# SCH_Scope_1014D_2023-01-06.net
KiCad netlist of a schematic drawn in EasyEDA
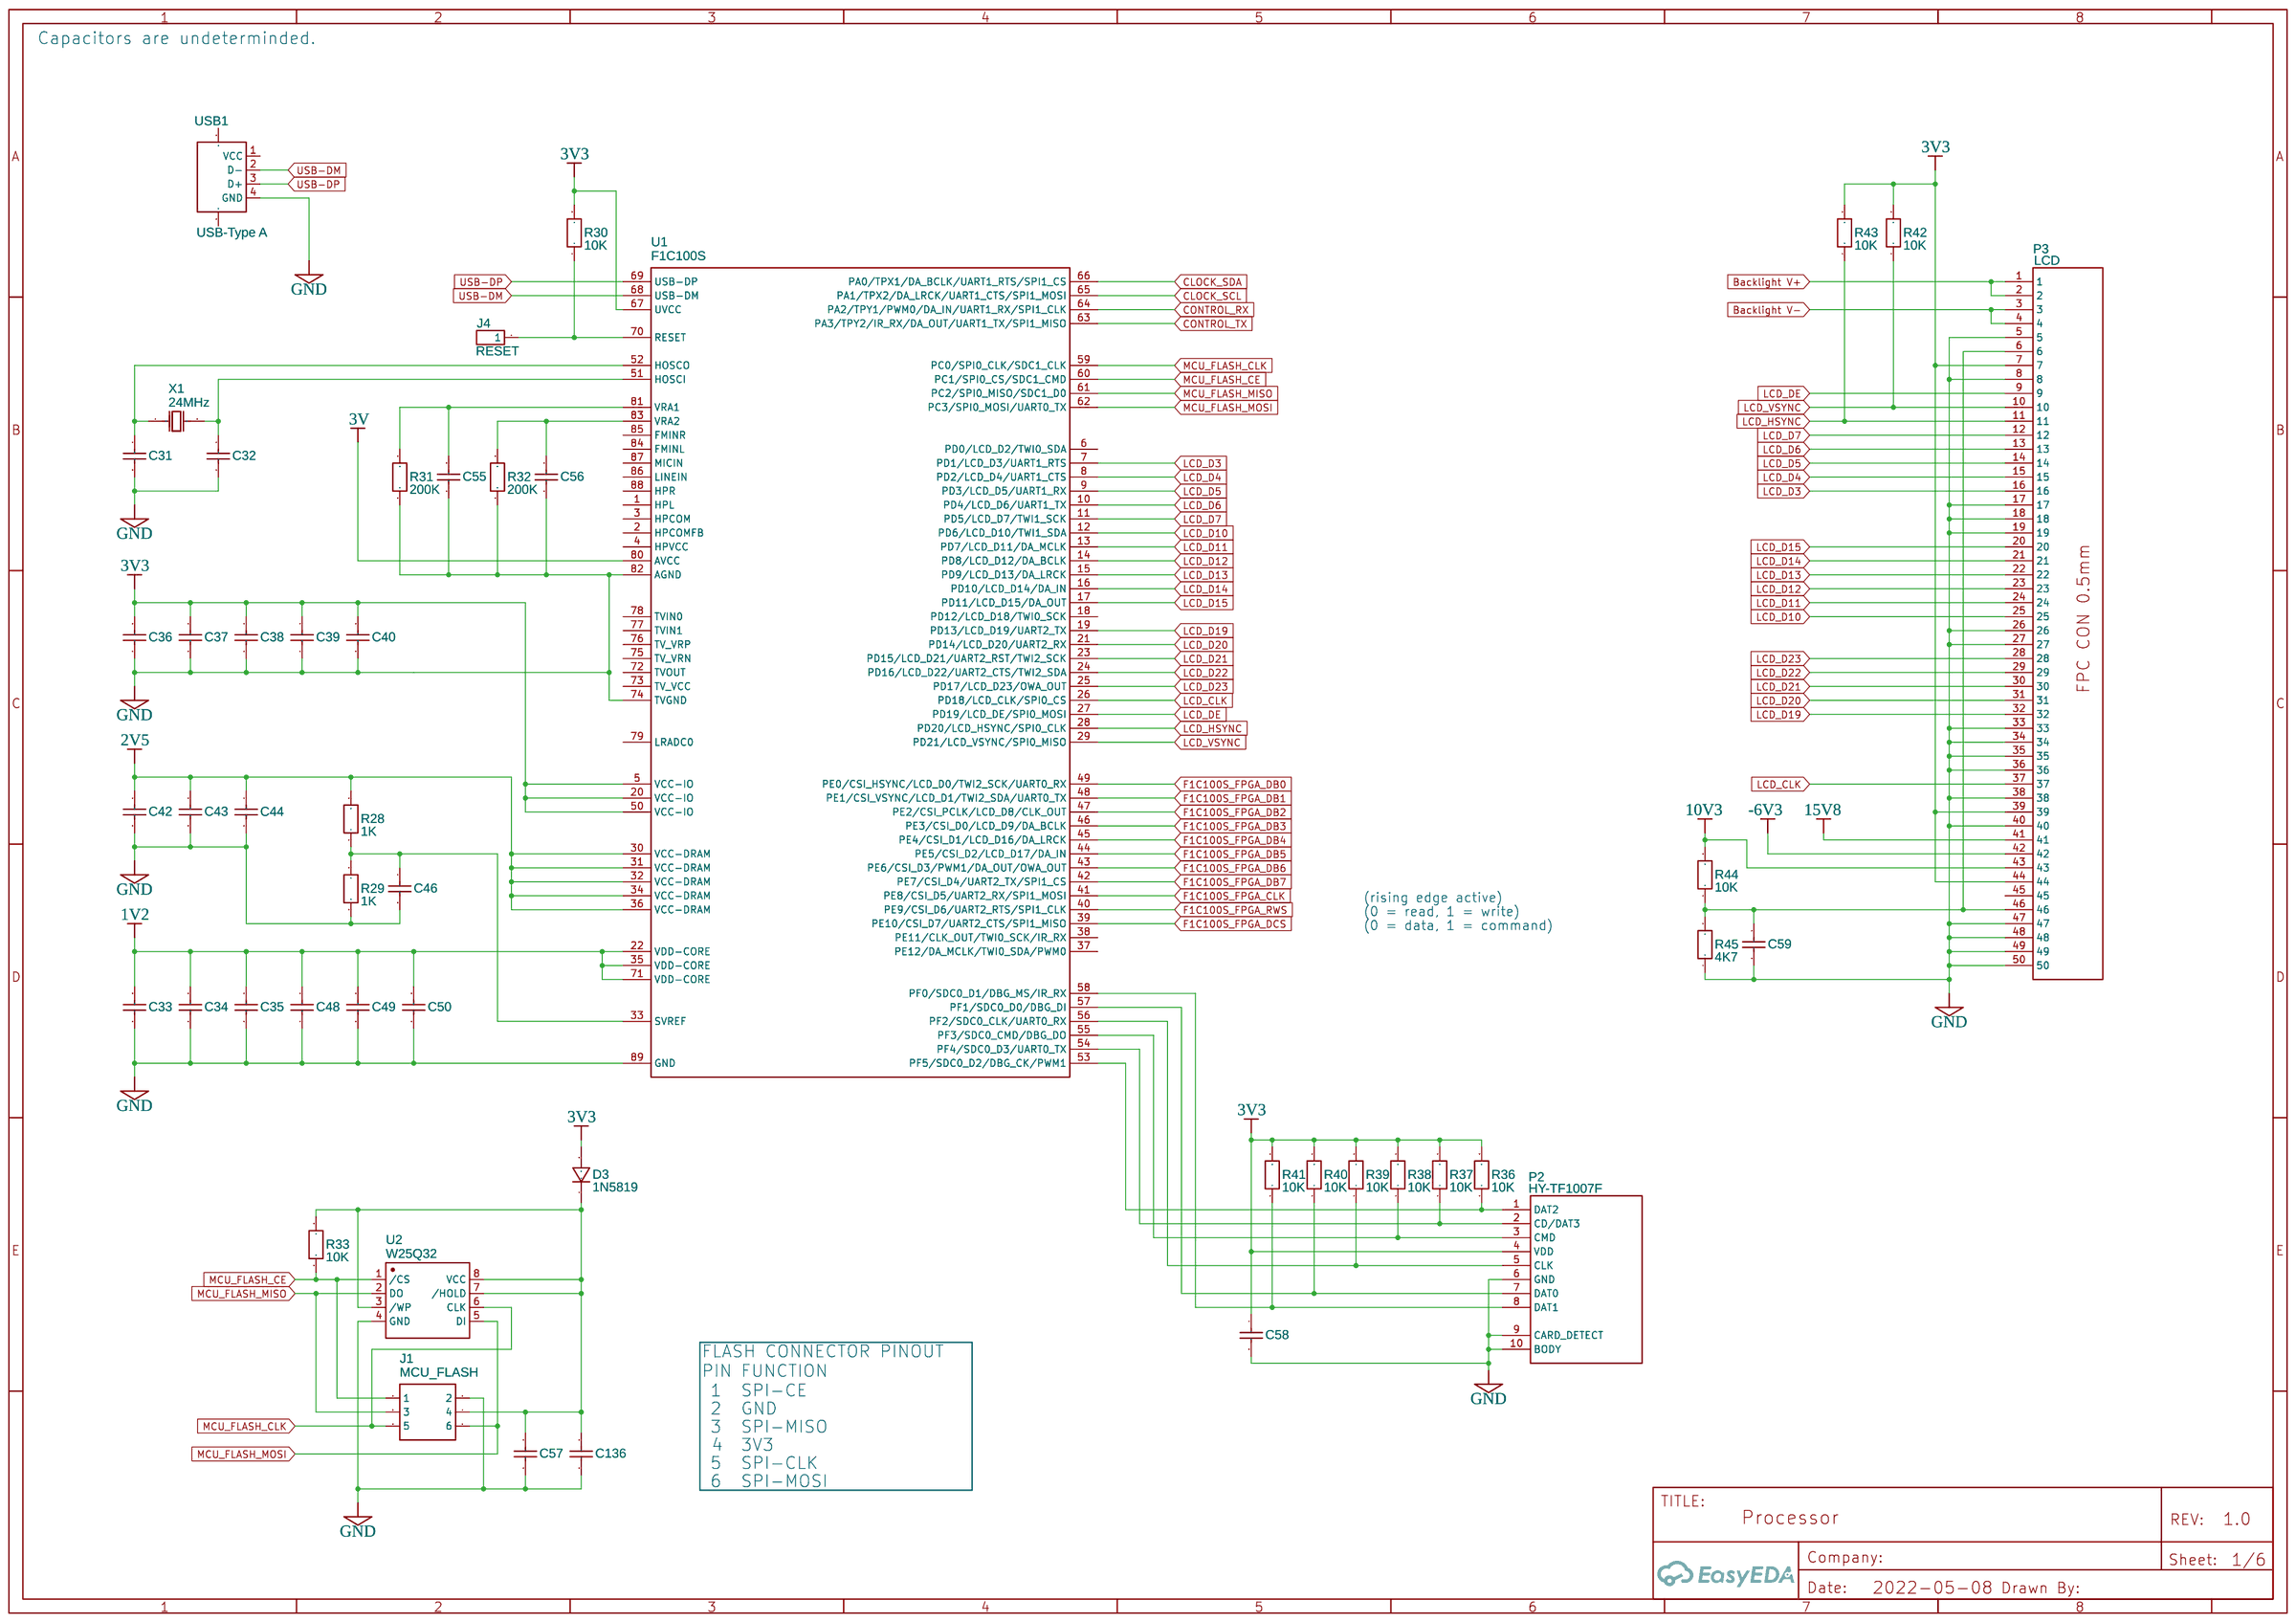
[diagram p0: Scope_1014D_Processor]
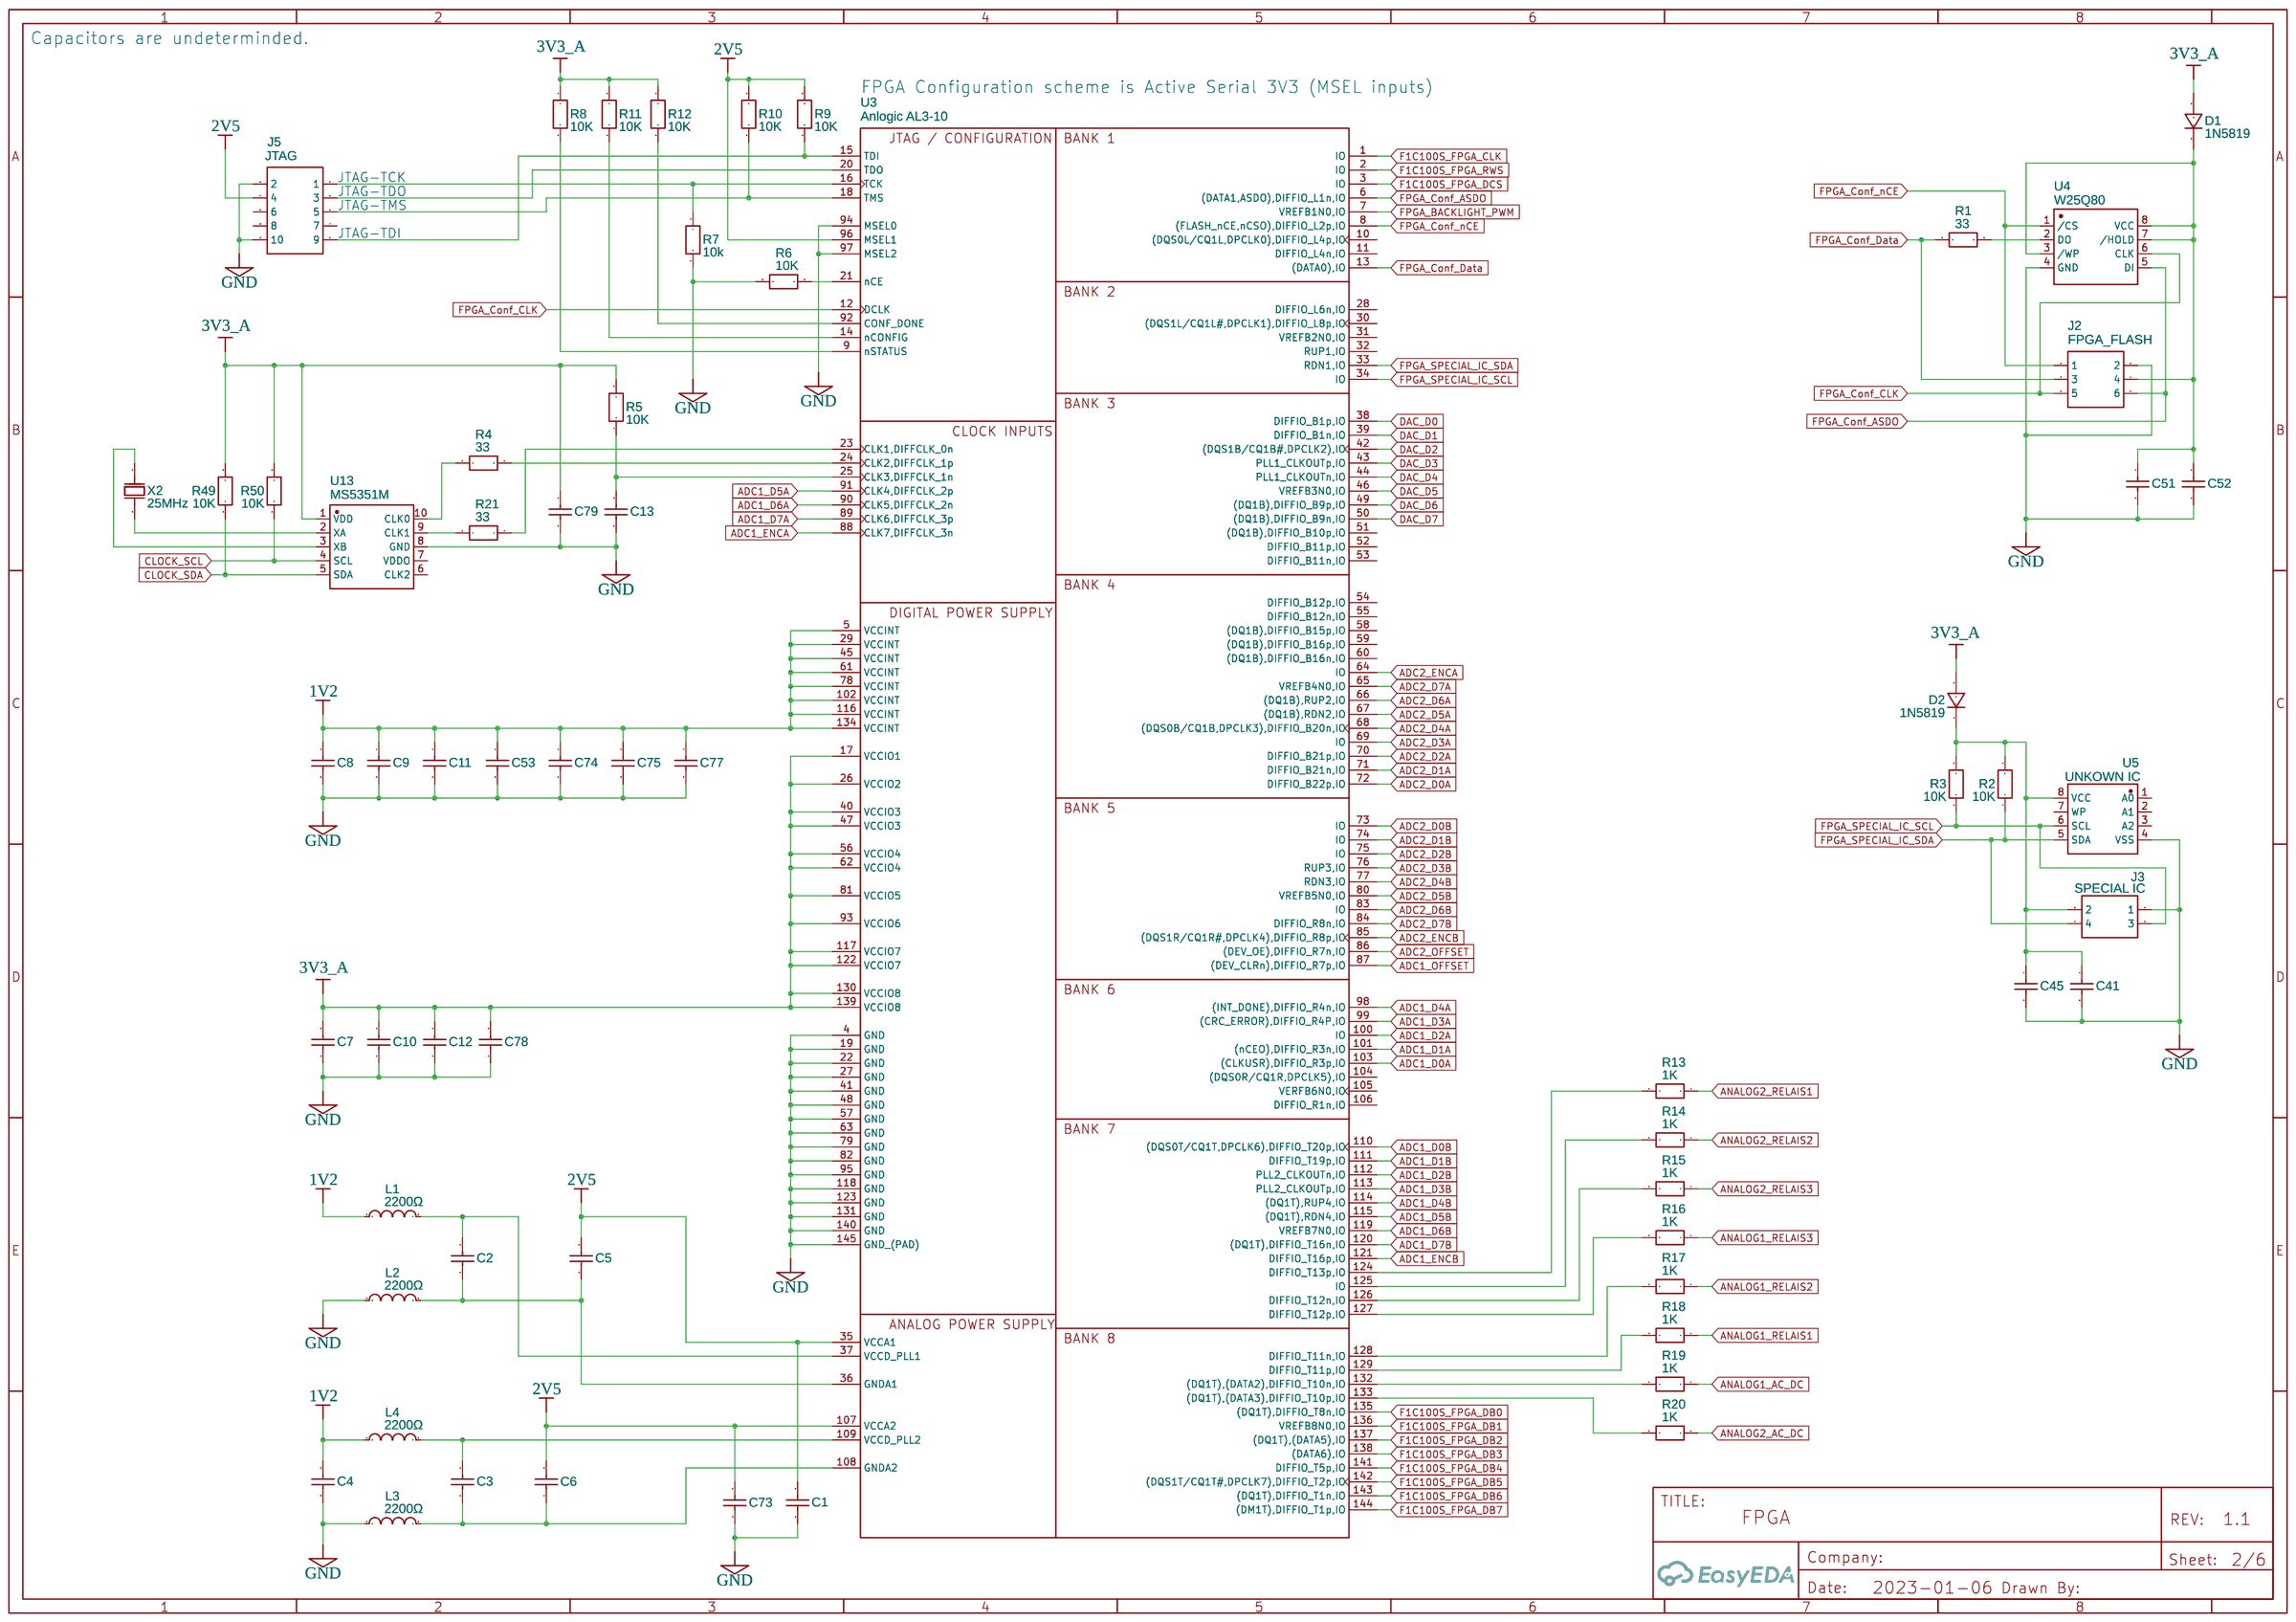
[diagram p1: Scope_1014D_Data_Acquisition]
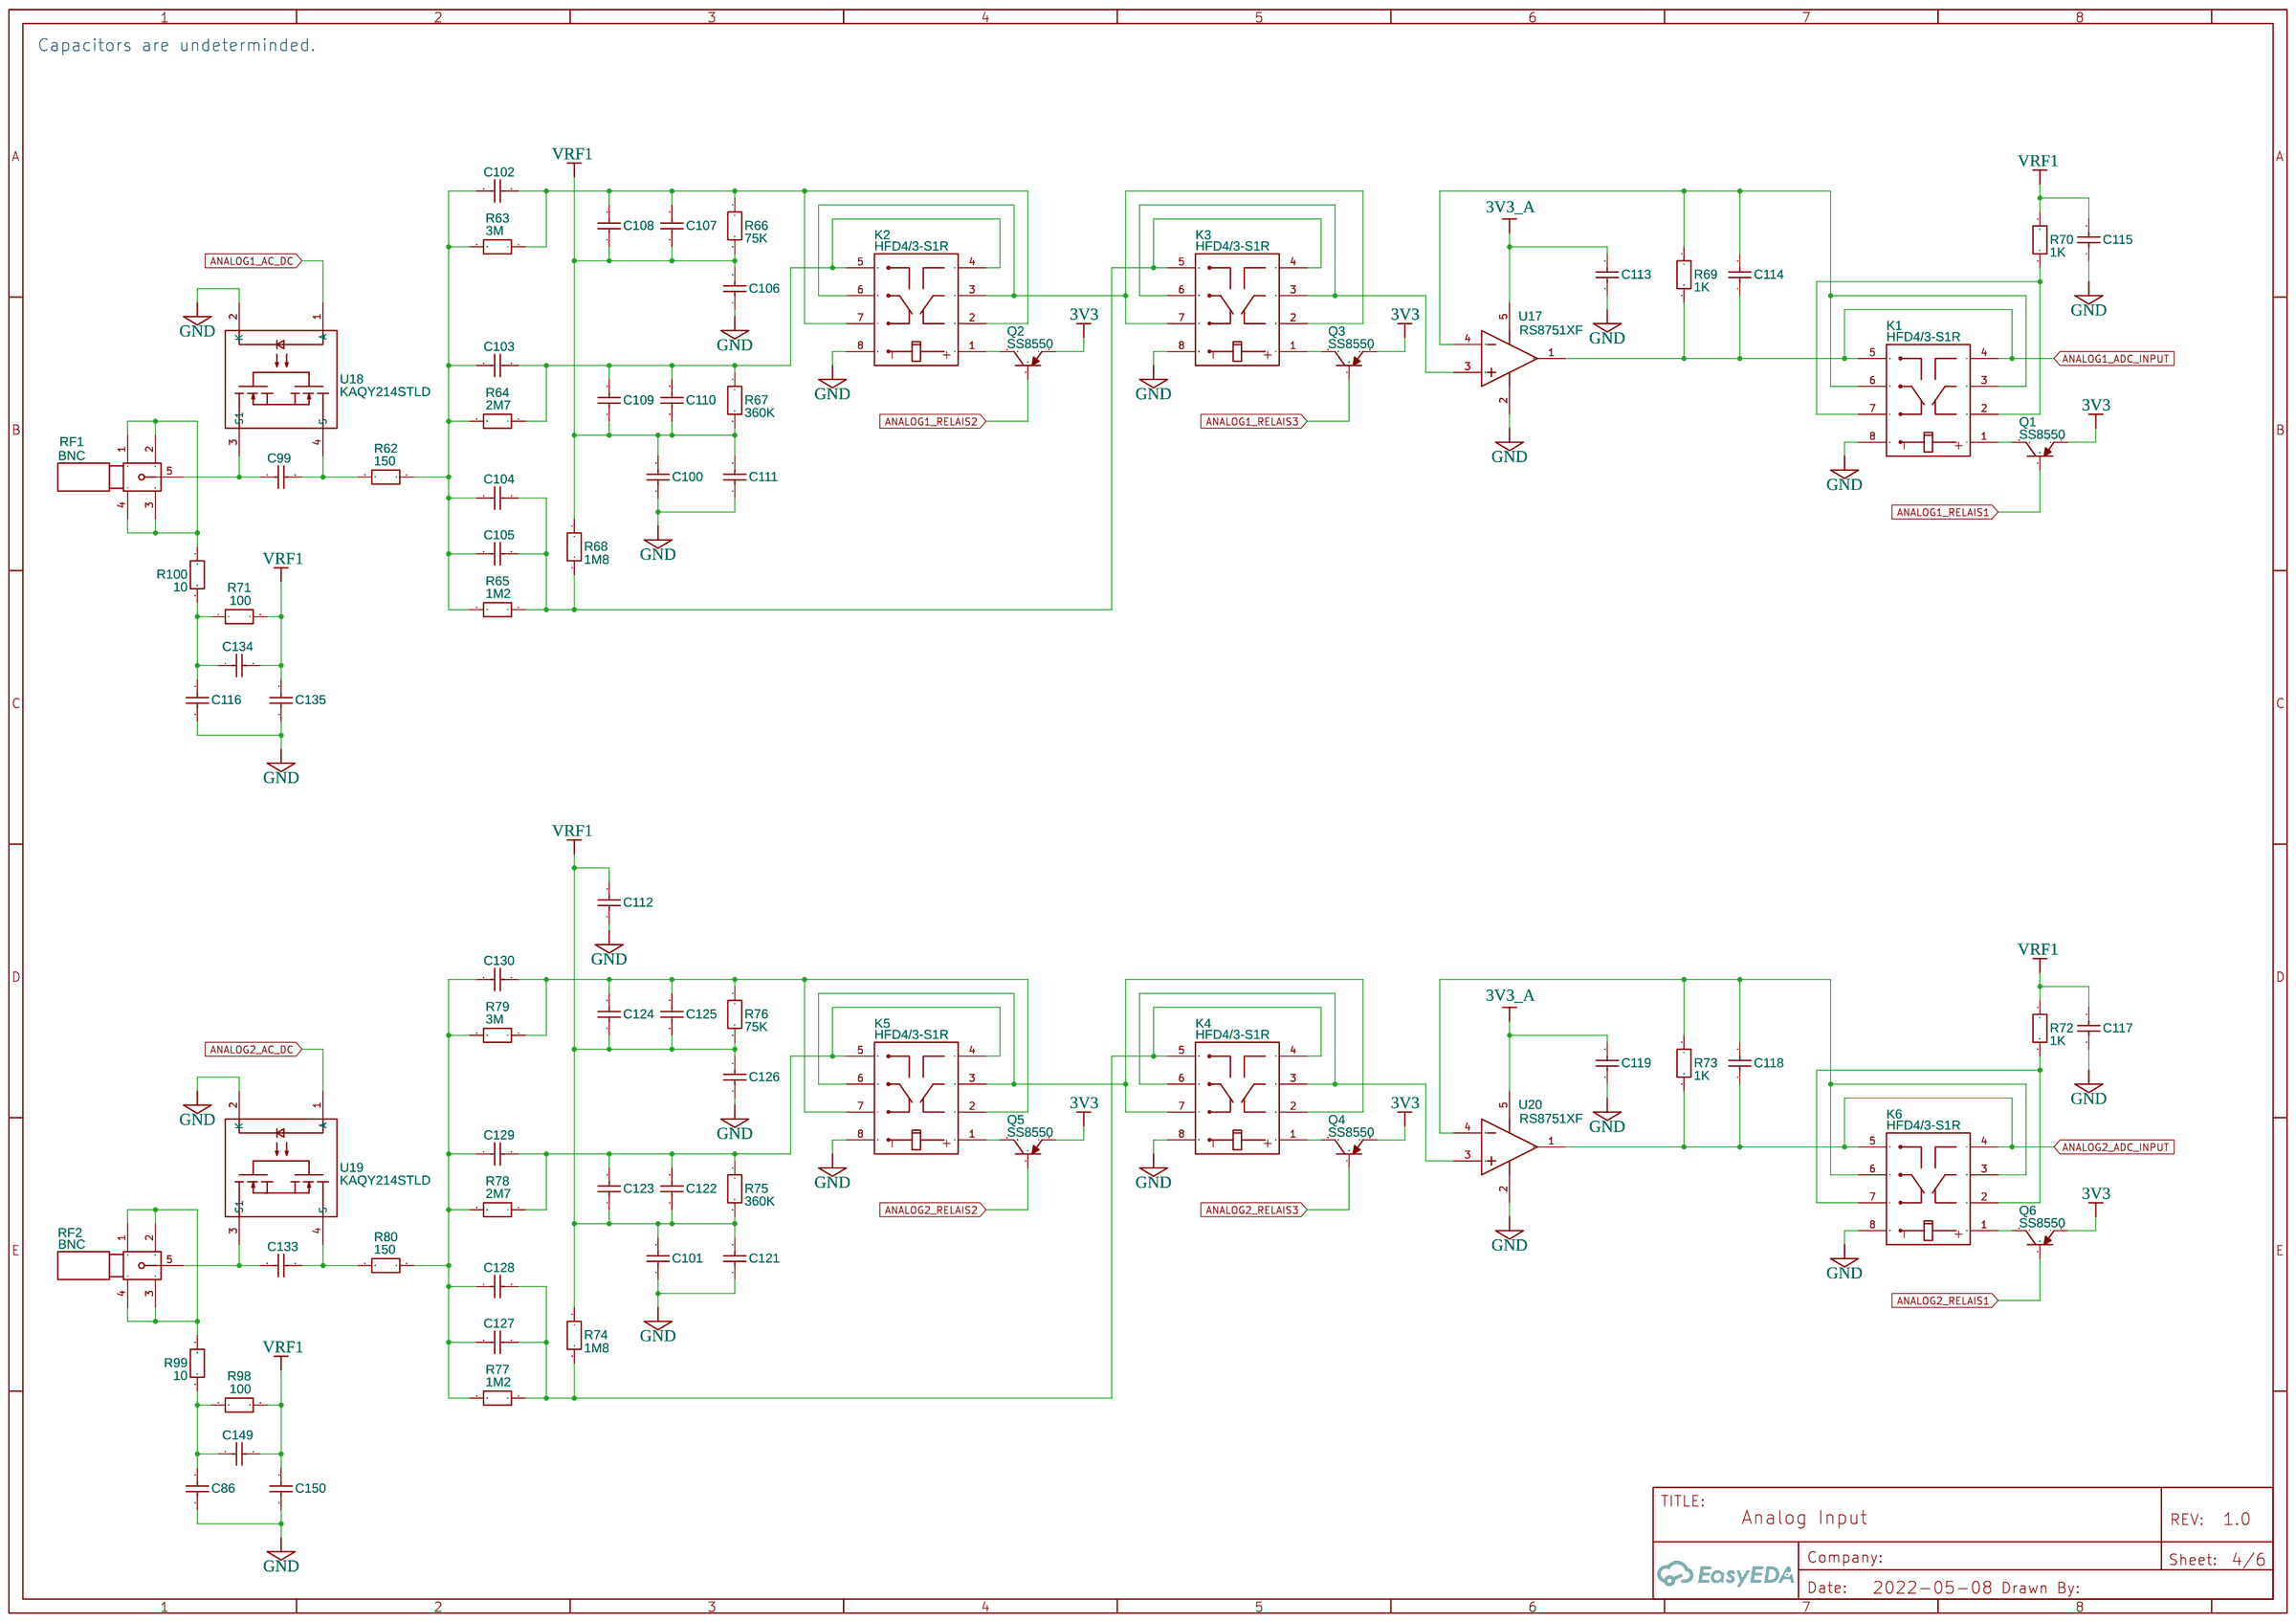
[diagram p2: Scope_1014D_Analog_Input]
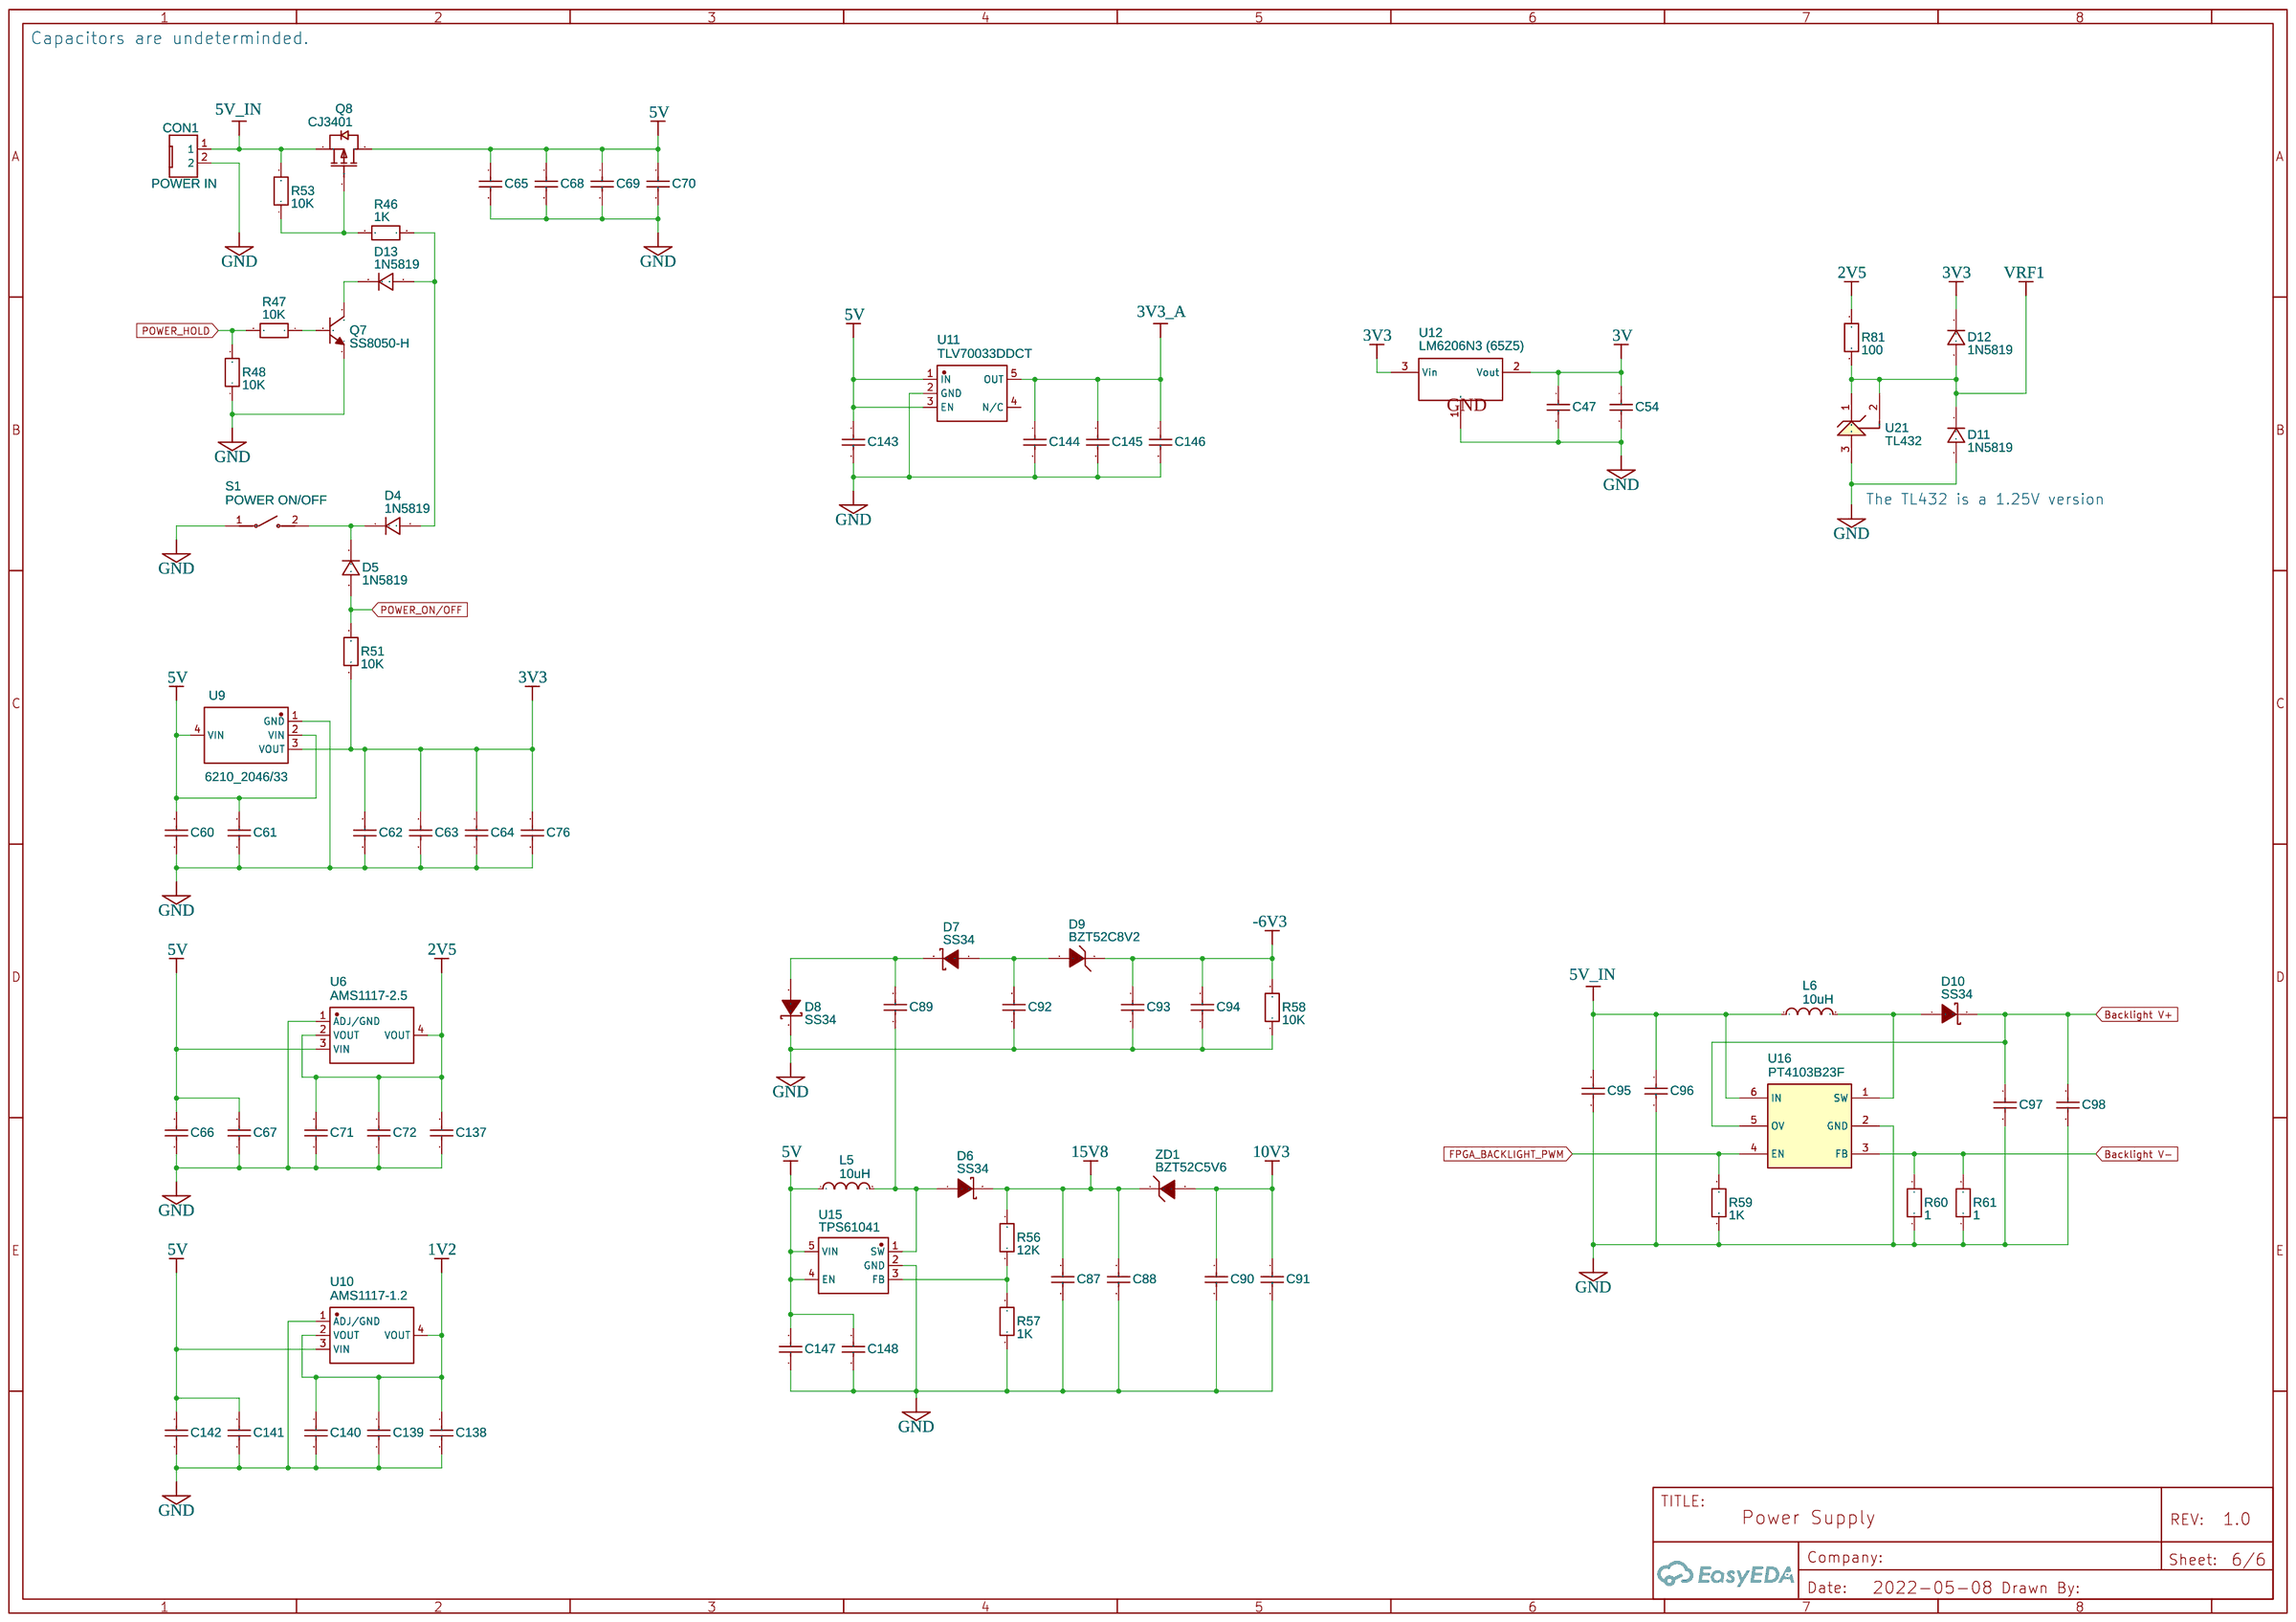
[diagram p3: Scope_1014D_Power_Supply]
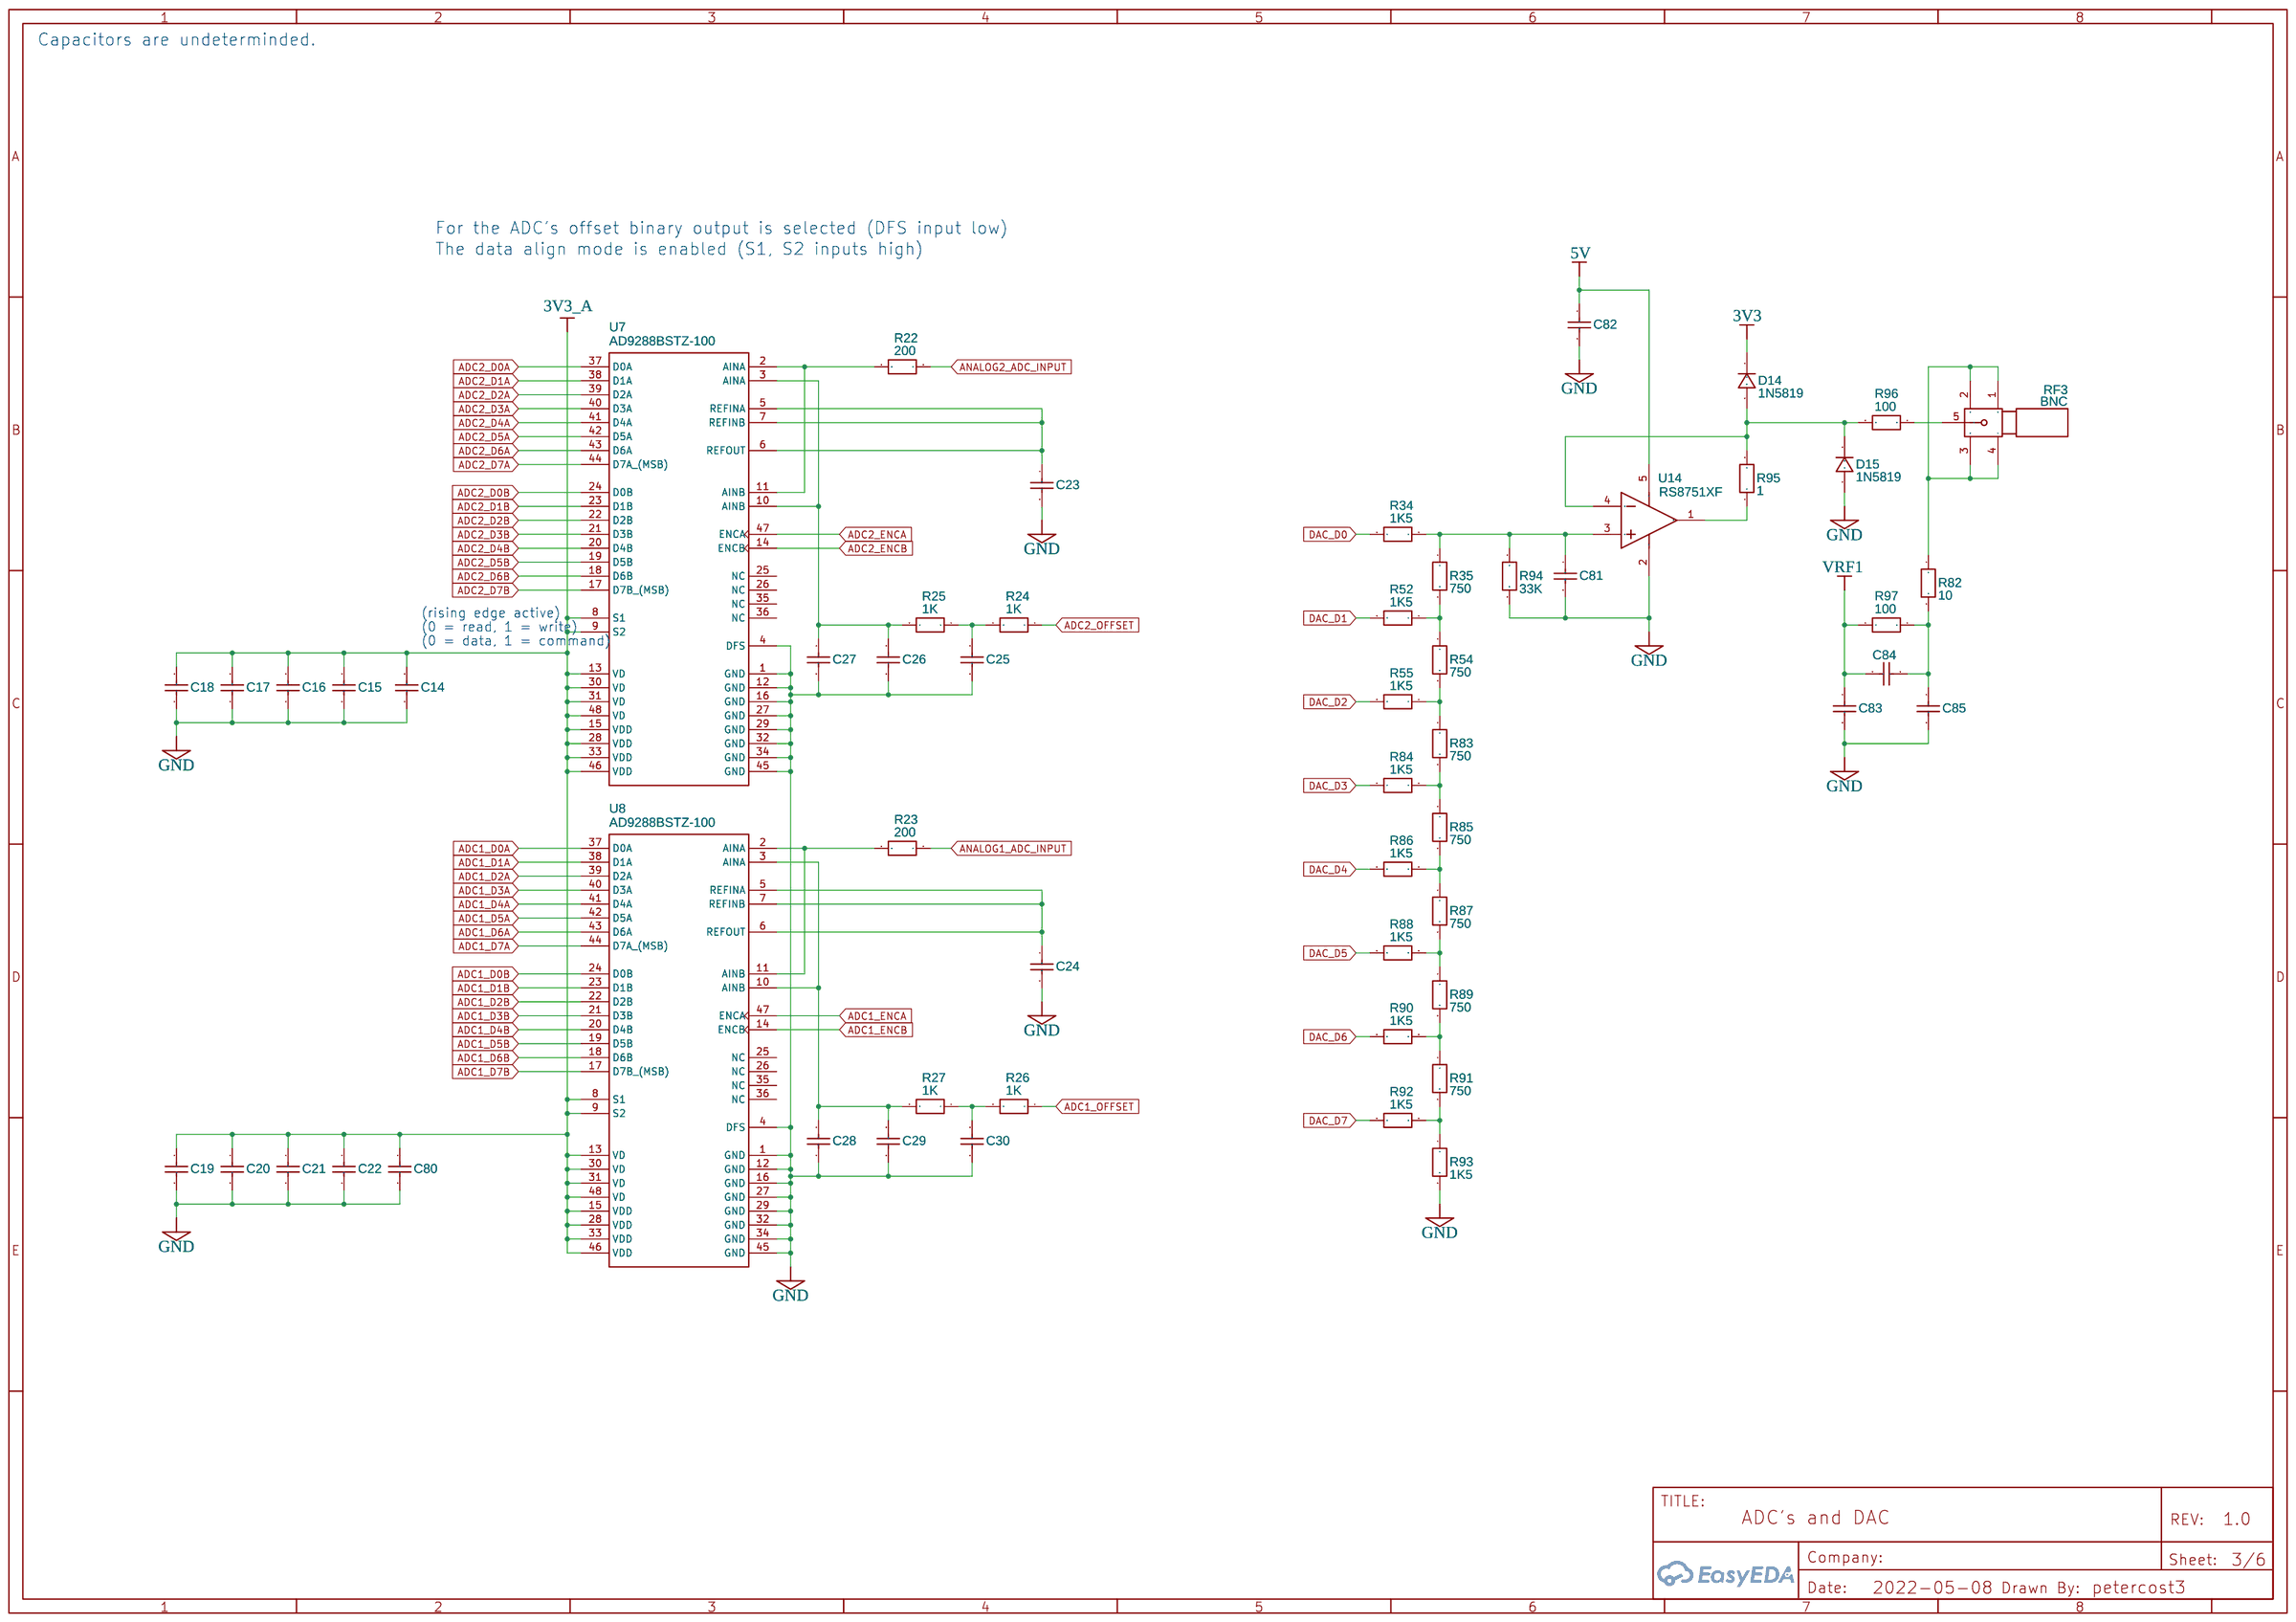
[diagram p4: Scope_1014D_ADC_DAC]
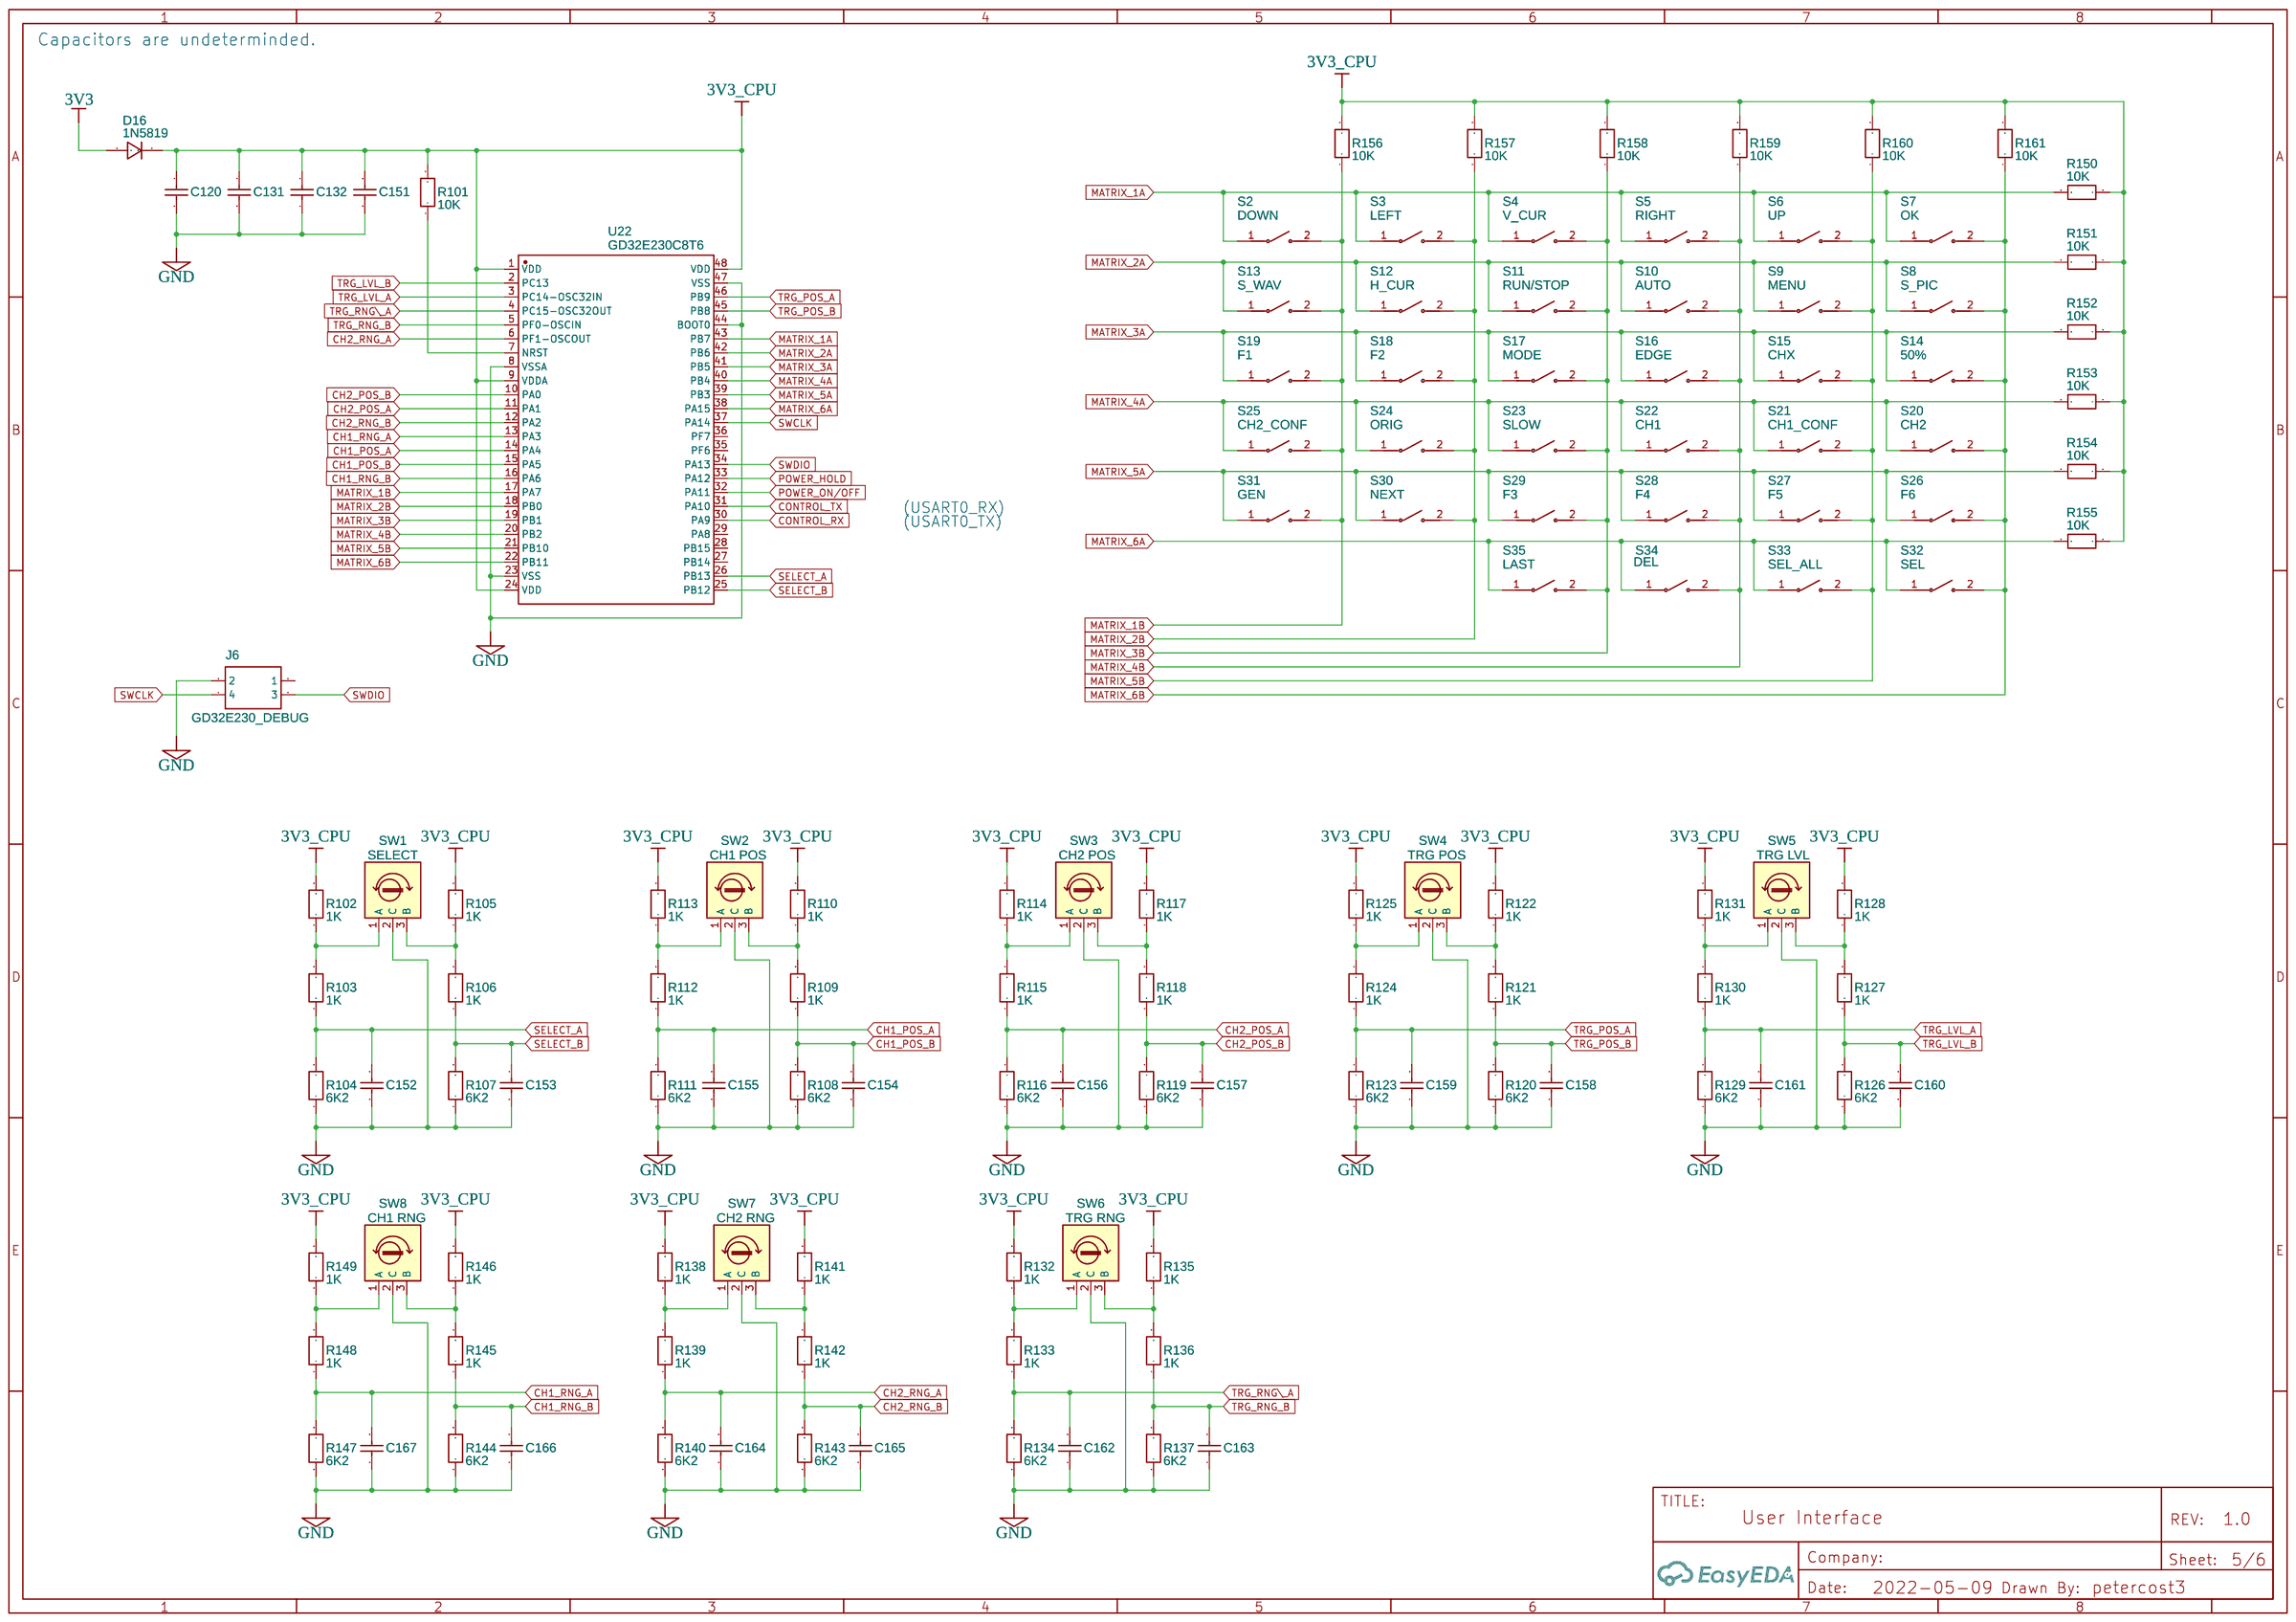
[diagram p5: Scope_1014D_User_Interface]

(export (version "E")
  (design (tool "Eeschema 10.0.6"))
  (components
    (comp (ref "C31")
      (value "1nF")
      (fields
        (field (name "BOM_Manufacturer Part") "GRM31B7U3A471JW31L")
        (field (name "BOM_Supplier Part") "C97936")
      )
      (libsource (lib "") (part "GRM31B7U3A471JW31L"))
    )
    (comp (ref "C32")
      (value "1nF")
      (fields
        (field (name "BOM_Manufacturer Part") "GRM31B7U3A471JW31L")
        (field (name "BOM_Supplier Part") "C97936")
      )
      (libsource (lib "") (part "GRM31B7U3A471JW31L"))
    )
    (comp (ref "C33")
      (value "1nF")
      (fields
        (field (name "BOM_Manufacturer Part") "GRM31B7U3A471JW31L")
        (field (name "BOM_Supplier Part") "C97936")
      )
      (libsource (lib "") (part "GRM31B7U3A471JW31L"))
    )
    (comp (ref "C34")
      (value "1nF")
      (fields
        (field (name "BOM_Manufacturer Part") "GRM31B7U3A471JW31L")
        (field (name "BOM_Supplier Part") "C97936")
      )
      (libsource (lib "") (part "GRM31B7U3A471JW31L"))
    )
    (comp (ref "C35")
      (value "1nF")
      (fields
        (field (name "BOM_Manufacturer Part") "GRM31B7U3A471JW31L")
        (field (name "BOM_Supplier Part") "C97936")
      )
      (libsource (lib "") (part "GRM31B7U3A471JW31L"))
    )
    (comp (ref "C36")
      (value "1nF")
      (fields
        (field (name "BOM_Manufacturer Part") "GRM31B7U3A471JW31L")
        (field (name "BOM_Supplier Part") "C97936")
      )
      (libsource (lib "") (part "GRM31B7U3A471JW31L"))
    )
    (comp (ref "C37")
      (value "1nF")
      (fields
        (field (name "BOM_Manufacturer Part") "GRM31B7U3A471JW31L")
        (field (name "BOM_Supplier Part") "C97936")
      )
      (libsource (lib "") (part "GRM31B7U3A471JW31L"))
    )
    (comp (ref "C38")
      (value "1nF")
      (fields
        (field (name "BOM_Manufacturer Part") "GRM31B7U3A471JW31L")
        (field (name "BOM_Supplier Part") "C97936")
      )
      (libsource (lib "") (part "GRM31B7U3A471JW31L"))
    )
    (comp (ref "C39")
      (value "1nF")
      (fields
        (field (name "BOM_Manufacturer Part") "GRM31B7U3A471JW31L")
        (field (name "BOM_Supplier Part") "C97936")
      )
      (libsource (lib "") (part "GRM31B7U3A471JW31L"))
    )
    (comp (ref "C40")
      (value "1nF")
      (fields
        (field (name "BOM_Manufacturer Part") "GRM31B7U3A471JW31L")
        (field (name "BOM_Supplier Part") "C97936")
      )
      (libsource (lib "") (part "GRM31B7U3A471JW31L"))
    )
    (comp (ref "C42")
      (value "1nF")
      (fields
        (field (name "BOM_Manufacturer Part") "GRM31B7U3A471JW31L")
        (field (name "BOM_Supplier Part") "C97936")
      )
      (libsource (lib "") (part "GRM31B7U3A471JW31L"))
    )
    (comp (ref "C43")
      (value "1nF")
      (fields
        (field (name "BOM_Manufacturer Part") "GRM31B7U3A471JW31L")
        (field (name "BOM_Supplier Part") "C97936")
      )
      (libsource (lib "") (part "GRM31B7U3A471JW31L"))
    )
    (comp (ref "C44")
      (value "1nF")
      (fields
        (field (name "BOM_Manufacturer Part") "GRM31B7U3A471JW31L")
        (field (name "BOM_Supplier Part") "C97936")
      )
      (libsource (lib "") (part "GRM31B7U3A471JW31L"))
    )
    (comp (ref "C46")
      (value "1nF")
      (fields
        (field (name "BOM_Manufacturer Part") "GRM31B7U3A471JW31L")
        (field (name "BOM_Supplier Part") "C97936")
      )
      (libsource (lib "") (part "GRM31B7U3A471JW31L"))
    )
    (comp (ref "C48")
      (value "1nF")
      (fields
        (field (name "BOM_Manufacturer Part") "GRM31B7U3A471JW31L")
        (field (name "BOM_Supplier Part") "C97936")
      )
      (libsource (lib "") (part "GRM31B7U3A471JW31L"))
    )
    (comp (ref "C49")
      (value "1nF")
      (fields
        (field (name "BOM_Manufacturer Part") "GRM31B7U3A471JW31L")
        (field (name "BOM_Supplier Part") "C97936")
      )
      (libsource (lib "") (part "GRM31B7U3A471JW31L"))
    )
    (comp (ref "C50")
      (value "1nF")
      (fields
        (field (name "BOM_Manufacturer Part") "GRM31B7U3A471JW31L")
        (field (name "BOM_Supplier Part") "C97936")
      )
      (libsource (lib "") (part "GRM31B7U3A471JW31L"))
    )
    (comp (ref "C55")
      (value "1nF")
      (fields
        (field (name "BOM_Manufacturer Part") "GRM31B7U3A471JW31L")
        (field (name "BOM_Supplier Part") "C97936")
      )
      (libsource (lib "") (part "GRM31B7U3A471JW31L"))
    )
    (comp (ref "C56")
      (value "1nF")
      (fields
        (field (name "BOM_Manufacturer Part") "GRM31B7U3A471JW31L")
        (field (name "BOM_Supplier Part") "C97936")
      )
      (libsource (lib "") (part "GRM31B7U3A471JW31L"))
    )
    (comp (ref "C57")
      (value "1nF")
      (fields
        (field (name "BOM_Manufacturer Part") "GRM31B7U3A471JW31L")
        (field (name "BOM_Supplier Part") "C97936")
      )
      (libsource (lib "") (part "GRM31B7U3A471JW31L"))
    )
    (comp (ref "C58")
      (value "1nF")
      (fields
        (field (name "BOM_Manufacturer Part") "GRM31B7U3A471JW31L")
        (field (name "BOM_Supplier Part") "C97936")
      )
      (libsource (lib "") (part "GRM31B7U3A471JW31L"))
    )
    (comp (ref "C59")
      (value "1nF")
      (fields
        (field (name "BOM_Manufacturer Part") "GRM31B7U3A471JW31L")
        (field (name "BOM_Supplier Part") "C97936")
      )
      (libsource (lib "") (part "GRM31B7U3A471JW31L"))
    )
    (comp (ref "C136")
      (value "1nF")
      (fields
        (field (name "BOM_Manufacturer Part") "GRM31B7U3A471JW31L")
        (field (name "BOM_Supplier Part") "C97936")
      )
      (libsource (lib "") (part "GRM31B7U3A471JW31L"))
    )
    (comp (ref "D3")
      (value "1N5819")
      (fields (field (name "BOM_Manufacturer Part") "1N4007") (field (name "BOM_Supplier Part") "C106903"))
      (libsource (lib "") (part "1N4007"))
    )
    (comp (ref "J1")
      (value "MCU_FLASH")
      (fields (field (name "BOM_Supplier Part") "C65114"))
      (libsource (lib "") (part "HDR-M-2.54_2x3"))
    )
    (comp (ref "J4")
      (value "RESET")
      (fields (field (name "BOM_Supplier Part") "C81276"))
      (libsource (lib "") (part "HDR-M-2.54_1x1"))
    )
    (comp (ref "P2")
      (value "HY-TF1007F")
      (fields (field (name "BOM_Supplier Part") "undefined"))
      (libsource (lib "") (part "HY-TF1007F"))
    )
    (comp (ref "P3") (value "LCD") (libsource (lib "") (part "FPC CONNECTOR 50P 0.5mm")))
    (comp (ref "R28") (value "1K") (libsource (lib "") (part "R_0805_EU")))
    (comp (ref "R29") (value "1K") (libsource (lib "") (part "R_0805_EU")))
    (comp (ref "R30") (value "10K") (libsource (lib "") (part "R_0805_EU")))
    (comp (ref "R31") (value "200K") (libsource (lib "") (part "R_0805_EU")))
    (comp (ref "R32") (value "200K") (libsource (lib "") (part "R_0805_EU")))
    (comp (ref "R33") (value "10K") (libsource (lib "") (part "R_0805_EU")))
    (comp (ref "R36") (value "10K") (libsource (lib "") (part "R_0805_EU")))
    (comp (ref "R37") (value "10K") (libsource (lib "") (part "R_0805_EU")))
    (comp (ref "R38") (value "10K") (libsource (lib "") (part "R_0805_EU")))
    (comp (ref "R39") (value "10K") (libsource (lib "") (part "R_0805_EU")))
    (comp (ref "R40") (value "10K") (libsource (lib "") (part "R_0805_EU")))
    (comp (ref "R41") (value "10K") (libsource (lib "") (part "R_0805_EU")))
    (comp (ref "R42") (value "10K") (libsource (lib "") (part "R_0805_EU")))
    (comp (ref "R43") (value "10K") (libsource (lib "") (part "R_0805_EU")))
    (comp (ref "R44") (value "10K") (libsource (lib "") (part "R_0805_EU")))
    (comp (ref "R45") (value "4K7") (libsource (lib "") (part "R_0805_EU")))
    (comp (ref "U1") (value "F1C100S") (libsource (lib "") (part "F1C100S")))
    (comp (ref "U2")
      (value "W25Q32")
      (fields
        (field (name "BOM_Manufacturer Part") "W25Q32FVSSIGTR")
        (field (name "BOM_Supplier Part") "C108057")
      )
      (libsource (lib "") (part "W25Q32FVSSIGTR"))
    )
    (comp (ref "USB1")
      (value "USB-Type A")
      (fields (field (name "BOM_Manufacturer Part") "USB-05") (field (name "BOM_Supplier Part") "C112454"))
      (libsource (lib "") (part "USB-Type A_Male"))
    )
    (comp (ref "X1")
      (value "24MHz")
      (fields
        (field (name "BOM_Manufacturer Part") "X503224MSD2GC")
        (field (name "BOM_Supplier Part") "C48304")
      )
      (libsource (lib "") (part "X503224MSD2GC"))
    )
    (comp (ref "C1")
      (value "1nF")
      (fields
        (field (name "BOM_Manufacturer Part") "GRM31B7U3A471JW31L")
        (field (name "BOM_Supplier Part") "C97936")
      )
      (libsource (lib "") (part "GRM31B7U3A471JW31L_1"))
    )
    (comp (ref "C2")
      (value "1nF")
      (fields
        (field (name "BOM_Manufacturer Part") "GRM31B7U3A471JW31L")
        (field (name "BOM_Supplier Part") "C97936")
      )
      (libsource (lib "") (part "GRM31B7U3A471JW31L_1"))
    )
    (comp (ref "C3")
      (value "1nF")
      (fields
        (field (name "BOM_Manufacturer Part") "GRM31B7U3A471JW31L")
        (field (name "BOM_Supplier Part") "C97936")
      )
      (libsource (lib "") (part "GRM31B7U3A471JW31L_1"))
    )
    (comp (ref "C4")
      (value "1nF")
      (fields
        (field (name "BOM_Manufacturer Part") "GRM31B7U3A471JW31L")
        (field (name "BOM_Supplier Part") "C97936")
      )
      (libsource (lib "") (part "GRM31B7U3A471JW31L_1"))
    )
    (comp (ref "C5")
      (value "1nF")
      (fields
        (field (name "BOM_Manufacturer Part") "GRM31B7U3A471JW31L")
        (field (name "BOM_Supplier Part") "C97936")
      )
      (libsource (lib "") (part "GRM31B7U3A471JW31L_1"))
    )
    (comp (ref "C6")
      (value "1nF")
      (fields
        (field (name "BOM_Manufacturer Part") "GRM31B7U3A471JW31L")
        (field (name "BOM_Supplier Part") "C97936")
      )
      (libsource (lib "") (part "GRM31B7U3A471JW31L"))
    )
    (comp (ref "C7")
      (value "1nF")
      (fields
        (field (name "BOM_Manufacturer Part") "GRM31B7U3A471JW31L")
        (field (name "BOM_Supplier Part") "C97936")
      )
      (libsource (lib "") (part "GRM31B7U3A471JW31L_1"))
    )
    (comp (ref "C8")
      (value "1nF")
      (fields
        (field (name "BOM_Manufacturer Part") "GRM31B7U3A471JW31L")
        (field (name "BOM_Supplier Part") "C97936")
      )
      (libsource (lib "") (part "GRM31B7U3A471JW31L_1"))
    )
    (comp (ref "C9")
      (value "1nF")
      (fields
        (field (name "BOM_Manufacturer Part") "GRM31B7U3A471JW31L")
        (field (name "BOM_Supplier Part") "C97936")
      )
      (libsource (lib "") (part "GRM31B7U3A471JW31L_1"))
    )
    (comp (ref "C10")
      (value "1nF")
      (fields
        (field (name "BOM_Manufacturer Part") "GRM31B7U3A471JW31L")
        (field (name "BOM_Supplier Part") "C97936")
      )
      (libsource (lib "") (part "GRM31B7U3A471JW31L_1"))
    )
    (comp (ref "C11")
      (value "1nF")
      (fields
        (field (name "BOM_Manufacturer Part") "GRM31B7U3A471JW31L")
        (field (name "BOM_Supplier Part") "C97936")
      )
      (libsource (lib "") (part "GRM31B7U3A471JW31L_1"))
    )
    (comp (ref "C12")
      (value "1nF")
      (fields
        (field (name "BOM_Manufacturer Part") "GRM31B7U3A471JW31L")
        (field (name "BOM_Supplier Part") "C97936")
      )
      (libsource (lib "") (part "GRM31B7U3A471JW31L_1"))
    )
    (comp (ref "C13")
      (value "1nF")
      (fields
        (field (name "BOM_Manufacturer Part") "GRM31B7U3A471JW31L")
        (field (name "BOM_Supplier Part") "C97936")
      )
      (libsource (lib "") (part "GRM31B7U3A471JW31L_1"))
    )
    (comp (ref "C41")
      (value "1nF")
      (fields
        (field (name "BOM_Manufacturer Part") "GRM31B7U3A471JW31L")
        (field (name "BOM_Supplier Part") "C97936")
      )
      (libsource (lib "") (part "GRM31B7U3A471JW31L_1"))
    )
    (comp (ref "C45")
      (value "1nF")
      (fields
        (field (name "BOM_Manufacturer Part") "GRM31B7U3A471JW31L")
        (field (name "BOM_Supplier Part") "C97936")
      )
      (libsource (lib "") (part "GRM31B7U3A471JW31L_1"))
    )
    (comp (ref "C51")
      (value "1nF")
      (fields
        (field (name "BOM_Manufacturer Part") "GRM31B7U3A471JW31L")
        (field (name "BOM_Supplier Part") "C97936")
      )
      (libsource (lib "") (part "GRM31B7U3A471JW31L_1"))
    )
    (comp (ref "C52")
      (value "1nF")
      (fields
        (field (name "BOM_Manufacturer Part") "GRM31B7U3A471JW31L")
        (field (name "BOM_Supplier Part") "C97936")
      )
      (libsource (lib "") (part "GRM31B7U3A471JW31L_1"))
    )
    (comp (ref "C53")
      (value "1nF")
      (fields
        (field (name "BOM_Manufacturer Part") "GRM31B7U3A471JW31L")
        (field (name "BOM_Supplier Part") "C97936")
      )
      (libsource (lib "") (part "GRM31B7U3A471JW31L_1"))
    )
    (comp (ref "C73")
      (value "1nF")
      (fields
        (field (name "BOM_Manufacturer Part") "GRM31B7U3A471JW31L")
        (field (name "BOM_Supplier Part") "C97936")
      )
      (libsource (lib "") (part "GRM31B7U3A471JW31L"))
    )
    (comp (ref "C74")
      (value "1nF")
      (fields
        (field (name "BOM_Manufacturer Part") "GRM31B7U3A471JW31L")
        (field (name "BOM_Supplier Part") "C97936")
      )
      (libsource (lib "") (part "GRM31B7U3A471JW31L_1"))
    )
    (comp (ref "C75")
      (value "1nF")
      (fields
        (field (name "BOM_Manufacturer Part") "GRM31B7U3A471JW31L")
        (field (name "BOM_Supplier Part") "C97936")
      )
      (libsource (lib "") (part "GRM31B7U3A471JW31L_1"))
    )
    (comp (ref "C77")
      (value "1nF")
      (fields
        (field (name "BOM_Manufacturer Part") "GRM31B7U3A471JW31L")
        (field (name "BOM_Supplier Part") "C97936")
      )
      (libsource (lib "") (part "GRM31B7U3A471JW31L_1"))
    )
    (comp (ref "C78")
      (value "1nF")
      (fields
        (field (name "BOM_Manufacturer Part") "GRM31B7U3A471JW31L")
        (field (name "BOM_Supplier Part") "C97936")
      )
      (libsource (lib "") (part "GRM31B7U3A471JW31L_1"))
    )
    (comp (ref "C79")
      (value "1nF")
      (fields
        (field (name "BOM_Manufacturer Part") "GRM31B7U3A471JW31L")
        (field (name "BOM_Supplier Part") "C97936")
      )
      (libsource (lib "") (part "GRM31B7U3A471JW31L_1"))
    )
    (comp (ref "D1")
      (value "1N5819")
      (fields (field (name "BOM_Manufacturer Part") "1N4007") (field (name "BOM_Supplier Part") "C106903"))
      (libsource (lib "") (part "1N4007_1"))
    )
    (comp (ref "D2")
      (value "1N5819")
      (fields (field (name "BOM_Manufacturer Part") "1N4007") (field (name "BOM_Supplier Part") "C106903"))
      (libsource (lib "") (part "1N4007"))
    )
    (comp (ref "J2")
      (value "FPGA_FLASH")
      (fields (field (name "BOM_Supplier Part") "C65114"))
      (libsource (lib "") (part "HDR-M-2.54_2x3"))
    )
    (comp (ref "J3")
      (value "SPECIAL IC")
      (fields (field (name "BOM_Supplier Part") "C66690"))
      (libsource (lib "") (part "HDR-M-2.54_2x2"))
    )
    (comp (ref "J5")
      (value "JTAG")
      (fields (field (name "BOM_Supplier Part") "C178292"))
      (libsource (lib "") (part "HDR-M-2.54_2x5"))
    )
    (comp (ref "L1")
      (value "2200Ω")
      (fields
        (field (name "BOM_Manufacturer Part") "BLM21PG221SN1D")
        (field (name "BOM_Supplier Part") "C85840")
      )
      (libsource (lib "") (part "BLM21PG221SN1D"))
    )
    (comp (ref "L2")
      (value "2200Ω")
      (fields
        (field (name "BOM_Manufacturer Part") "BLM21PG221SN1D")
        (field (name "BOM_Supplier Part") "C85840")
      )
      (libsource (lib "") (part "BLM21PG221SN1D"))
    )
    (comp (ref "L3")
      (value "2200Ω")
      (fields
        (field (name "BOM_Manufacturer Part") "BLM21PG221SN1D")
        (field (name "BOM_Supplier Part") "C85840")
      )
      (libsource (lib "") (part "BLM21PG221SN1D"))
    )
    (comp (ref "L4")
      (value "2200Ω")
      (fields
        (field (name "BOM_Manufacturer Part") "BLM21PG221SN1D")
        (field (name "BOM_Supplier Part") "C85840")
      )
      (libsource (lib "") (part "BLM21PG221SN1D"))
    )
    (comp (ref "R1") (value "33") (libsource (lib "") (part "R_0805_EU_3")))
    (comp (ref "R2") (value "10K") (libsource (lib "") (part "R_0805_EU_1")))
    (comp (ref "R3") (value "10K") (libsource (lib "") (part "R_0805_EU_1")))
    (comp (ref "R4") (value "33") (libsource (lib "") (part "R_0805_EU")))
    (comp (ref "R5") (value "10K") (libsource (lib "") (part "R_0805_EU_1")))
    (comp (ref "R6") (value "10K") (libsource (lib "") (part "R_0805_EU")))
    (comp (ref "R7") (value "10k") (libsource (lib "") (part "R_0805_EU_2")))
    (comp (ref "R8") (value "10K") (libsource (lib "") (part "R_0805_EU_2")))
    (comp (ref "R9") (value "10K") (libsource (lib "") (part "R_0805_EU_2")))
    (comp (ref "R10") (value "10K") (libsource (lib "") (part "R_0805_EU_2")))
    (comp (ref "R11") (value "10K") (libsource (lib "") (part "R_0805_EU_2")))
    (comp (ref "R12") (value "10K") (libsource (lib "") (part "R_0805_EU_2")))
    (comp (ref "R13") (value "1K") (libsource (lib "") (part "R_0805_EU")))
    (comp (ref "R14") (value "1K") (libsource (lib "") (part "R_0805_EU")))
    (comp (ref "R15") (value "1K") (libsource (lib "") (part "R_0805_EU")))
    (comp (ref "R16") (value "1K") (libsource (lib "") (part "R_0805_EU")))
    (comp (ref "R17") (value "1K") (libsource (lib "") (part "R_0805_EU")))
    (comp (ref "R18") (value "1K") (libsource (lib "") (part "R_0805_EU")))
    (comp (ref "R19") (value "1K") (libsource (lib "") (part "R_0805_EU")))
    (comp (ref "R20") (value "1K") (libsource (lib "") (part "R_0805_EU")))
    (comp (ref "R21") (value "33") (libsource (lib "") (part "R_0805_EU")))
    (comp (ref "R49") (value "10K") (libsource (lib "") (part "R_0805_EU_1")))
    (comp (ref "R50") (value "10K") (libsource (lib "") (part "R_0805_EU_1")))
    (comp (ref "U3") (value "Anlogic AL3-10") (libsource (lib "") (part "EP4CE6E22C8N")))
    (comp (ref "U4")
      (value "W25Q80")
      (fields
        (field (name "BOM_Manufacturer Part") "W25Q32FVSSIGTR")
        (field (name "BOM_Supplier Part") "C108057")
      )
      (libsource (lib "") (part "W25Q32FVSSIGTR"))
    )
    (comp (ref "U5")
      (value "UNKOWN IC")
      (fields
        (field (name "BOM_Manufacturer Part") "24LC04BT-I/SN")
        (field (name "BOM_Supplier Part") "C511263")
      )
      (libsource (lib "") (part "24LC04BT-I/SN"))
    )
    (comp (ref "U13")
      (value "MS5351M")
      (fields (field (name "BOM_Supplier Part") "C1509083"))
      (libsource (lib "") (part "MS5351M"))
    )
    (comp (ref "X2")
      (value "25MHz")
      (fields
        (field (name "BOM_Manufacturer Part") "X503224MSD2GC")
        (field (name "BOM_Supplier Part") "C48304")
      )
      (libsource (lib "") (part "X503224MSD2GC"))
    )
    (comp (ref "C86")
      (value "1nF")
      (fields
        (field (name "BOM_Manufacturer Part") "GRM31B7U3A471JW31L")
        (field (name "BOM_Supplier Part") "C97936")
      )
      (libsource (lib "") (part "GRM31B7U3A471JW31L_1"))
    )
    (comp (ref "C99")
      (value "1nF")
      (fields
        (field (name "BOM_Manufacturer Part") "GRM31B7U3A471JW31L")
        (field (name "BOM_Supplier Part") "C97936")
      )
      (libsource (lib "") (part "GRM31B7U3A471JW31L"))
    )
    (comp (ref "C100")
      (value "1nF")
      (fields
        (field (name "BOM_Manufacturer Part") "GRM31B7U3A471JW31L")
        (field (name "BOM_Supplier Part") "C97936")
      )
      (libsource (lib "") (part "GRM31B7U3A471JW31L_2"))
    )
    (comp (ref "C101")
      (value "1nF")
      (fields
        (field (name "BOM_Manufacturer Part") "GRM31B7U3A471JW31L")
        (field (name "BOM_Supplier Part") "C97936")
      )
      (libsource (lib "") (part "GRM31B7U3A471JW31L_2"))
    )
    (comp (ref "C102")
      (value "1nF")
      (fields
        (field (name "BOM_Manufacturer Part") "GRM31B7U3A471JW31L")
        (field (name "BOM_Supplier Part") "C97936")
      )
      (libsource (lib "") (part "GRM31B7U3A471JW31L"))
    )
    (comp (ref "C103")
      (value "1nF")
      (fields
        (field (name "BOM_Manufacturer Part") "GRM31B7U3A471JW31L")
        (field (name "BOM_Supplier Part") "C97936")
      )
      (libsource (lib "") (part "GRM31B7U3A471JW31L"))
    )
    (comp (ref "C104")
      (value "1nF")
      (fields
        (field (name "BOM_Manufacturer Part") "GRM31B7U3A471JW31L")
        (field (name "BOM_Supplier Part") "C97936")
      )
      (libsource (lib "") (part "GRM31B7U3A471JW31L"))
    )
    (comp (ref "C105")
      (value "1nF")
      (fields
        (field (name "BOM_Manufacturer Part") "GRM31B7U3A471JW31L")
        (field (name "BOM_Supplier Part") "C97936")
      )
      (libsource (lib "") (part "GRM31B7U3A471JW31L"))
    )
    (comp (ref "C106")
      (value "1nF")
      (fields
        (field (name "BOM_Manufacturer Part") "GRM31B7U3A471JW31L")
        (field (name "BOM_Supplier Part") "C97936")
      )
      (libsource (lib "") (part "GRM31B7U3A471JW31L_2"))
    )
    (comp (ref "C107")
      (value "1nF")
      (fields
        (field (name "BOM_Manufacturer Part") "GRM31B7U3A471JW31L")
        (field (name "BOM_Supplier Part") "C97936")
      )
      (libsource (lib "") (part "GRM31B7U3A471JW31L_2"))
    )
    (comp (ref "C108")
      (value "1nF")
      (fields
        (field (name "BOM_Manufacturer Part") "GRM31B7U3A471JW31L")
        (field (name "BOM_Supplier Part") "C97936")
      )
      (libsource (lib "") (part "GRM31B7U3A471JW31L_2"))
    )
    (comp (ref "C109")
      (value "1nF")
      (fields
        (field (name "BOM_Manufacturer Part") "GRM31B7U3A471JW31L")
        (field (name "BOM_Supplier Part") "C97936")
      )
      (libsource (lib "") (part "GRM31B7U3A471JW31L_2"))
    )
    (comp (ref "C110")
      (value "1nF")
      (fields
        (field (name "BOM_Manufacturer Part") "GRM31B7U3A471JW31L")
        (field (name "BOM_Supplier Part") "C97936")
      )
      (libsource (lib "") (part "GRM31B7U3A471JW31L_2"))
    )
    (comp (ref "C111")
      (value "1nF")
      (fields
        (field (name "BOM_Manufacturer Part") "GRM31B7U3A471JW31L")
        (field (name "BOM_Supplier Part") "C97936")
      )
      (libsource (lib "") (part "GRM31B7U3A471JW31L_2"))
    )
    (comp (ref "C112")
      (value "1nF")
      (fields
        (field (name "BOM_Manufacturer Part") "GRM31B7U3A471JW31L")
        (field (name "BOM_Supplier Part") "C97936")
      )
      (libsource (lib "") (part "GRM31B7U3A471JW31L_2"))
    )
    (comp (ref "C113")
      (value "1nF")
      (fields
        (field (name "BOM_Manufacturer Part") "GRM31B7U3A471JW31L")
        (field (name "BOM_Supplier Part") "C97936")
      )
      (libsource (lib "") (part "GRM31B7U3A471JW31L_2"))
    )
    (comp (ref "C114")
      (value "1nF")
      (fields
        (field (name "BOM_Manufacturer Part") "GRM31B7U3A471JW31L")
        (field (name "BOM_Supplier Part") "C97936")
      )
      (libsource (lib "") (part "GRM31B7U3A471JW31L_2"))
    )
    (comp (ref "C115")
      (value "1nF")
      (fields
        (field (name "BOM_Manufacturer Part") "GRM31B7U3A471JW31L")
        (field (name "BOM_Supplier Part") "C97936")
      )
      (libsource (lib "") (part "GRM31B7U3A471JW31L_2"))
    )
    (comp (ref "C116")
      (value "1nF")
      (fields
        (field (name "BOM_Manufacturer Part") "GRM31B7U3A471JW31L")
        (field (name "BOM_Supplier Part") "C97936")
      )
      (libsource (lib "") (part "GRM31B7U3A471JW31L_1"))
    )
    (comp (ref "C117")
      (value "1nF")
      (fields
        (field (name "BOM_Manufacturer Part") "GRM31B7U3A471JW31L")
        (field (name "BOM_Supplier Part") "C97936")
      )
      (libsource (lib "") (part "GRM31B7U3A471JW31L_2"))
    )
    (comp (ref "C118")
      (value "1nF")
      (fields
        (field (name "BOM_Manufacturer Part") "GRM31B7U3A471JW31L")
        (field (name "BOM_Supplier Part") "C97936")
      )
      (libsource (lib "") (part "GRM31B7U3A471JW31L_2"))
    )
    (comp (ref "C119")
      (value "1nF")
      (fields
        (field (name "BOM_Manufacturer Part") "GRM31B7U3A471JW31L")
        (field (name "BOM_Supplier Part") "C97936")
      )
      (libsource (lib "") (part "GRM31B7U3A471JW31L_2"))
    )
    (comp (ref "C121")
      (value "1nF")
      (fields
        (field (name "BOM_Manufacturer Part") "GRM31B7U3A471JW31L")
        (field (name "BOM_Supplier Part") "C97936")
      )
      (libsource (lib "") (part "GRM31B7U3A471JW31L_2"))
    )
    (comp (ref "C122")
      (value "1nF")
      (fields
        (field (name "BOM_Manufacturer Part") "GRM31B7U3A471JW31L")
        (field (name "BOM_Supplier Part") "C97936")
      )
      (libsource (lib "") (part "GRM31B7U3A471JW31L_2"))
    )
    (comp (ref "C123")
      (value "1nF")
      (fields
        (field (name "BOM_Manufacturer Part") "GRM31B7U3A471JW31L")
        (field (name "BOM_Supplier Part") "C97936")
      )
      (libsource (lib "") (part "GRM31B7U3A471JW31L_2"))
    )
    (comp (ref "C124")
      (value "1nF")
      (fields
        (field (name "BOM_Manufacturer Part") "GRM31B7U3A471JW31L")
        (field (name "BOM_Supplier Part") "C97936")
      )
      (libsource (lib "") (part "GRM31B7U3A471JW31L_2"))
    )
    (comp (ref "C125")
      (value "1nF")
      (fields
        (field (name "BOM_Manufacturer Part") "GRM31B7U3A471JW31L")
        (field (name "BOM_Supplier Part") "C97936")
      )
      (libsource (lib "") (part "GRM31B7U3A471JW31L_2"))
    )
    (comp (ref "C126")
      (value "1nF")
      (fields
        (field (name "BOM_Manufacturer Part") "GRM31B7U3A471JW31L")
        (field (name "BOM_Supplier Part") "C97936")
      )
      (libsource (lib "") (part "GRM31B7U3A471JW31L_2"))
    )
    (comp (ref "C127")
      (value "1nF")
      (fields
        (field (name "BOM_Manufacturer Part") "GRM31B7U3A471JW31L")
        (field (name "BOM_Supplier Part") "C97936")
      )
      (libsource (lib "") (part "GRM31B7U3A471JW31L"))
    )
    (comp (ref "C128")
      (value "1nF")
      (fields
        (field (name "BOM_Manufacturer Part") "GRM31B7U3A471JW31L")
        (field (name "BOM_Supplier Part") "C97936")
      )
      (libsource (lib "") (part "GRM31B7U3A471JW31L"))
    )
    (comp (ref "C129")
      (value "1nF")
      (fields
        (field (name "BOM_Manufacturer Part") "GRM31B7U3A471JW31L")
        (field (name "BOM_Supplier Part") "C97936")
      )
      (libsource (lib "") (part "GRM31B7U3A471JW31L"))
    )
    (comp (ref "C130")
      (value "1nF")
      (fields
        (field (name "BOM_Manufacturer Part") "GRM31B7U3A471JW31L")
        (field (name "BOM_Supplier Part") "C97936")
      )
      (libsource (lib "") (part "GRM31B7U3A471JW31L"))
    )
    (comp (ref "C133")
      (value "1nF")
      (fields
        (field (name "BOM_Manufacturer Part") "GRM31B7U3A471JW31L")
        (field (name "BOM_Supplier Part") "C97936")
      )
      (libsource (lib "") (part "GRM31B7U3A471JW31L"))
    )
    (comp (ref "C134")
      (value "1nF")
      (fields
        (field (name "BOM_Manufacturer Part") "GRM31B7U3A471JW31L")
        (field (name "BOM_Supplier Part") "C97936")
      )
      (libsource (lib "") (part "GRM31B7U3A471JW31L_3"))
    )
    (comp (ref "C135")
      (value "1nF")
      (fields
        (field (name "BOM_Manufacturer Part") "GRM31B7U3A471JW31L")
        (field (name "BOM_Supplier Part") "C97936")
      )
      (libsource (lib "") (part "GRM31B7U3A471JW31L_1"))
    )
    (comp (ref "C149")
      (value "1nF")
      (fields
        (field (name "BOM_Manufacturer Part") "GRM31B7U3A471JW31L")
        (field (name "BOM_Supplier Part") "C97936")
      )
      (libsource (lib "") (part "GRM31B7U3A471JW31L_3"))
    )
    (comp (ref "C150")
      (value "1nF")
      (fields
        (field (name "BOM_Manufacturer Part") "GRM31B7U3A471JW31L")
        (field (name "BOM_Supplier Part") "C97936")
      )
      (libsource (lib "") (part "GRM31B7U3A471JW31L_1"))
    )
    (comp (ref "K1")
      (value "HFD4/3-S1R")
      (fields (field (name "BOM_Supplier Part") "C143232"))
      (libsource (lib "") (part "HFD4/3-S1R"))
    )
    (comp (ref "K2")
      (value "HFD4/3-S1R")
      (fields (field (name "BOM_Supplier Part") "C143232"))
      (libsource (lib "") (part "HFD4/3-S1R"))
    )
    (comp (ref "K3")
      (value "HFD4/3-S1R")
      (fields (field (name "BOM_Supplier Part") "C143232"))
      (libsource (lib "") (part "HFD4/3-S1R"))
    )
    (comp (ref "K4")
      (value "HFD4/3-S1R")
      (fields (field (name "BOM_Supplier Part") "C143232"))
      (libsource (lib "") (part "HFD4/3-S1R"))
    )
    (comp (ref "K5")
      (value "HFD4/3-S1R")
      (fields (field (name "BOM_Supplier Part") "C143232"))
      (libsource (lib "") (part "HFD4/3-S1R"))
    )
    (comp (ref "K6")
      (value "HFD4/3-S1R")
      (fields (field (name "BOM_Supplier Part") "C143232"))
      (libsource (lib "") (part "HFD4/3-S1R"))
    )
    (comp (ref "Q1")
      (value "SS8550")
      (fields (field (name "BOM_Supplier Part") "C909745"))
      (libsource (lib "") (part "SS8550"))
    )
    (comp (ref "Q2")
      (value "SS8550")
      (fields (field (name "BOM_Supplier Part") "C909745"))
      (libsource (lib "") (part "SS8550"))
    )
    (comp (ref "Q3")
      (value "SS8550")
      (fields (field (name "BOM_Supplier Part") "C909745"))
      (libsource (lib "") (part "SS8550"))
    )
    (comp (ref "Q4")
      (value "SS8550")
      (fields (field (name "BOM_Supplier Part") "C909745"))
      (libsource (lib "") (part "SS8550"))
    )
    (comp (ref "Q5")
      (value "SS8550")
      (fields (field (name "BOM_Supplier Part") "C909745"))
      (libsource (lib "") (part "SS8550"))
    )
    (comp (ref "Q6")
      (value "SS8550")
      (fields (field (name "BOM_Supplier Part") "C909745"))
      (libsource (lib "") (part "SS8550"))
    )
    (comp (ref "R62") (value "150") (libsource (lib "") (part "R_0805_EU_1")))
    (comp (ref "R63") (value "3M") (libsource (lib "") (part "R_0805_EU_1")))
    (comp (ref "R64") (value "2M7") (libsource (lib "") (part "R_0805_EU_1")))
    (comp (ref "R65") (value "1M2") (libsource (lib "") (part "R_0805_EU_1")))
    (comp (ref "R66") (value "75K") (libsource (lib "") (part "R_0805_EU")))
    (comp (ref "R67") (value "360K") (libsource (lib "") (part "R_0805_EU")))
    (comp (ref "R68") (value "1M8") (libsource (lib "") (part "R_0805_EU")))
    (comp (ref "R69") (value "1K") (libsource (lib "") (part "R_0805_EU")))
    (comp (ref "R70") (value "1K") (libsource (lib "") (part "R_0805_EU")))
    (comp (ref "R71") (value "100") (libsource (lib "") (part "R_0805_EU_2")))
    (comp (ref "R72") (value "1K") (libsource (lib "") (part "R_0805_EU")))
    (comp (ref "R73") (value "1K") (libsource (lib "") (part "R_0805_EU")))
    (comp (ref "R74") (value "1M8") (libsource (lib "") (part "R_0805_EU")))
    (comp (ref "R75") (value "360K") (libsource (lib "") (part "R_0805_EU")))
    (comp (ref "R76") (value "75K") (libsource (lib "") (part "R_0805_EU")))
    (comp (ref "R77") (value "1M2") (libsource (lib "") (part "R_0805_EU_1")))
    (comp (ref "R78") (value "2M7") (libsource (lib "") (part "R_0805_EU_1")))
    (comp (ref "R79") (value "3M") (libsource (lib "") (part "R_0805_EU_1")))
    (comp (ref "R80") (value "150") (libsource (lib "") (part "R_0805_EU_1")))
    (comp (ref "R98") (value "100") (libsource (lib "") (part "R_0805_EU_2")))
    (comp (ref "R99") (value "10") (libsource (lib "") (part "R_0805_EU")))
    (comp (ref "R100") (value "10") (libsource (lib "") (part "R_0805_EU")))
    (comp (ref "RF1")
      (value "BNC")
      (fields
        (field (name "BOM_Manufacturer Part") "DOSIN-801-0080")
        (field (name "BOM_Supplier Part") "C521219")
      )
      (libsource (lib "") (part "DOSIN-801-0080"))
    )
    (comp (ref "RF2")
      (value "BNC")
      (fields
        (field (name "BOM_Manufacturer Part") "DOSIN-801-0080")
        (field (name "BOM_Supplier Part") "C521219")
      )
      (libsource (lib "") (part "DOSIN-801-0080"))
    )
    (comp (ref "U17")
      (value "RS8751XF")
      (fields (field (name "BOM_Supplier Part") "C236995"))
      (libsource (lib "") (part "RS8751XF"))
    )
    (comp (ref "U18")
      (value "KAQY214STLD")
      (fields (field (name "BOM_Supplier Part") "C113331"))
      (libsource (lib "") (part "KAQY214STLD"))
    )
    (comp (ref "U19")
      (value "KAQY214STLD")
      (fields (field (name "BOM_Supplier Part") "C113331"))
      (libsource (lib "") (part "KAQY214STLD"))
    )
    (comp (ref "U20")
      (value "RS8751XF")
      (fields (field (name "BOM_Supplier Part") "C236995"))
      (libsource (lib "") (part "RS8751XF"))
    )
    (comp (ref "C47")
      (value "1nF")
      (fields
        (field (name "BOM_Manufacturer Part") "GRM31B7U3A471JW31L")
        (field (name "BOM_Supplier Part") "C97936")
      )
      (libsource (lib "") (part "GRM31B7U3A471JW31L"))
    )
    (comp (ref "C54")
      (value "1nF")
      (fields
        (field (name "BOM_Manufacturer Part") "GRM31B7U3A471JW31L")
        (field (name "BOM_Supplier Part") "C97936")
      )
      (libsource (lib "") (part "GRM31B7U3A471JW31L"))
    )
    (comp (ref "C60")
      (value "1nF")
      (fields
        (field (name "BOM_Manufacturer Part") "GRM31B7U3A471JW31L")
        (field (name "BOM_Supplier Part") "C97936")
      )
      (libsource (lib "") (part "GRM31B7U3A471JW31L"))
    )
    (comp (ref "C61")
      (value "1nF")
      (fields
        (field (name "BOM_Manufacturer Part") "GRM31B7U3A471JW31L")
        (field (name "BOM_Supplier Part") "C97936")
      )
      (libsource (lib "") (part "GRM31B7U3A471JW31L"))
    )
    (comp (ref "C62")
      (value "1nF")
      (fields
        (field (name "BOM_Manufacturer Part") "GRM31B7U3A471JW31L")
        (field (name "BOM_Supplier Part") "C97936")
      )
      (libsource (lib "") (part "GRM31B7U3A471JW31L"))
    )
    (comp (ref "C63")
      (value "1nF")
      (fields
        (field (name "BOM_Manufacturer Part") "GRM31B7U3A471JW31L")
        (field (name "BOM_Supplier Part") "C97936")
      )
      (libsource (lib "") (part "GRM31B7U3A471JW31L"))
    )
    (comp (ref "C64")
      (value "1nF")
      (fields
        (field (name "BOM_Manufacturer Part") "GRM31B7U3A471JW31L")
        (field (name "BOM_Supplier Part") "C97936")
      )
      (libsource (lib "") (part "GRM31B7U3A471JW31L"))
    )
    (comp (ref "C65")
      (value "1nF")
      (fields
        (field (name "BOM_Manufacturer Part") "GRM31B7U3A471JW31L")
        (field (name "BOM_Supplier Part") "C97936")
      )
      (libsource (lib "") (part "GRM31B7U3A471JW31L"))
    )
    (comp (ref "C66")
      (value "1nF")
      (fields
        (field (name "BOM_Manufacturer Part") "GRM31B7U3A471JW31L")
        (field (name "BOM_Supplier Part") "C97936")
      )
      (libsource (lib "") (part "GRM31B7U3A471JW31L"))
    )
    (comp (ref "C67")
      (value "1nF")
      (fields
        (field (name "BOM_Manufacturer Part") "GRM31B7U3A471JW31L")
        (field (name "BOM_Supplier Part") "C97936")
      )
      (libsource (lib "") (part "GRM31B7U3A471JW31L"))
    )
    (comp (ref "C68")
      (value "1nF")
      (fields
        (field (name "BOM_Manufacturer Part") "GRM31B7U3A471JW31L")
        (field (name "BOM_Supplier Part") "C97936")
      )
      (libsource (lib "") (part "GRM31B7U3A471JW31L"))
    )
    (comp (ref "C69")
      (value "1nF")
      (fields
        (field (name "BOM_Manufacturer Part") "GRM31B7U3A471JW31L")
        (field (name "BOM_Supplier Part") "C97936")
      )
      (libsource (lib "") (part "GRM31B7U3A471JW31L"))
    )
    (comp (ref "C70")
      (value "1nF")
      (fields
        (field (name "BOM_Manufacturer Part") "GRM31B7U3A471JW31L")
        (field (name "BOM_Supplier Part") "C97936")
      )
      (libsource (lib "") (part "GRM31B7U3A471JW31L"))
    )
    (comp (ref "C71")
      (value "1nF")
      (fields
        (field (name "BOM_Manufacturer Part") "GRM31B7U3A471JW31L")
        (field (name "BOM_Supplier Part") "C97936")
      )
      (libsource (lib "") (part "GRM31B7U3A471JW31L"))
    )
    (comp (ref "C72")
      (value "1nF")
      (fields
        (field (name "BOM_Manufacturer Part") "GRM31B7U3A471JW31L")
        (field (name "BOM_Supplier Part") "C97936")
      )
      (libsource (lib "") (part "GRM31B7U3A471JW31L"))
    )
    (comp (ref "C76")
      (value "1nF")
      (fields
        (field (name "BOM_Manufacturer Part") "GRM31B7U3A471JW31L")
        (field (name "BOM_Supplier Part") "C97936")
      )
      (libsource (lib "") (part "GRM31B7U3A471JW31L"))
    )
    (comp (ref "C87")
      (value "1nF")
      (fields
        (field (name "BOM_Manufacturer Part") "GRM31B7U3A471JW31L")
        (field (name "BOM_Supplier Part") "C97936")
      )
      (libsource (lib "") (part "GRM31B7U3A471JW31L"))
    )
    (comp (ref "C88")
      (value "1nF")
      (fields
        (field (name "BOM_Manufacturer Part") "GRM31B7U3A471JW31L")
        (field (name "BOM_Supplier Part") "C97936")
      )
      (libsource (lib "") (part "GRM31B7U3A471JW31L"))
    )
    (comp (ref "C89")
      (value "1nF")
      (fields
        (field (name "BOM_Manufacturer Part") "GRM31B7U3A471JW31L")
        (field (name "BOM_Supplier Part") "C97936")
      )
      (libsource (lib "") (part "GRM31B7U3A471JW31L"))
    )
    (comp (ref "C90")
      (value "1nF")
      (fields
        (field (name "BOM_Manufacturer Part") "GRM31B7U3A471JW31L")
        (field (name "BOM_Supplier Part") "C97936")
      )
      (libsource (lib "") (part "GRM31B7U3A471JW31L"))
    )
    (comp (ref "C91")
      (value "1nF")
      (fields
        (field (name "BOM_Manufacturer Part") "GRM31B7U3A471JW31L")
        (field (name "BOM_Supplier Part") "C97936")
      )
      (libsource (lib "") (part "GRM31B7U3A471JW31L"))
    )
    (comp (ref "C92")
      (value "1nF")
      (fields
        (field (name "BOM_Manufacturer Part") "GRM31B7U3A471JW31L")
        (field (name "BOM_Supplier Part") "C97936")
      )
      (libsource (lib "") (part "GRM31B7U3A471JW31L"))
    )
    (comp (ref "C93")
      (value "1nF")
      (fields
        (field (name "BOM_Manufacturer Part") "GRM31B7U3A471JW31L")
        (field (name "BOM_Supplier Part") "C97936")
      )
      (libsource (lib "") (part "GRM31B7U3A471JW31L"))
    )
    (comp (ref "C94")
      (value "1nF")
      (fields
        (field (name "BOM_Manufacturer Part") "GRM31B7U3A471JW31L")
        (field (name "BOM_Supplier Part") "C97936")
      )
      (libsource (lib "") (part "GRM31B7U3A471JW31L"))
    )
    (comp (ref "C95")
      (value "1nF")
      (fields
        (field (name "BOM_Manufacturer Part") "GRM31B7U3A471JW31L")
        (field (name "BOM_Supplier Part") "C97936")
      )
      (libsource (lib "") (part "GRM31B7U3A471JW31L"))
    )
    (comp (ref "C96")
      (value "1nF")
      (fields
        (field (name "BOM_Manufacturer Part") "GRM31B7U3A471JW31L")
        (field (name "BOM_Supplier Part") "C97936")
      )
      (libsource (lib "") (part "GRM31B7U3A471JW31L"))
    )
    (comp (ref "C97")
      (value "1nF")
      (fields
        (field (name "BOM_Manufacturer Part") "GRM31B7U3A471JW31L")
        (field (name "BOM_Supplier Part") "C97936")
      )
      (libsource (lib "") (part "GRM31B7U3A471JW31L"))
    )
    (comp (ref "C98")
      (value "1nF")
      (fields
        (field (name "BOM_Manufacturer Part") "GRM31B7U3A471JW31L")
        (field (name "BOM_Supplier Part") "C97936")
      )
      (libsource (lib "") (part "GRM31B7U3A471JW31L"))
    )
    (comp (ref "C137")
      (value "1nF")
      (fields
        (field (name "BOM_Manufacturer Part") "GRM31B7U3A471JW31L")
        (field (name "BOM_Supplier Part") "C97936")
      )
      (libsource (lib "") (part "GRM31B7U3A471JW31L"))
    )
    (comp (ref "C138")
      (value "1nF")
      (fields
        (field (name "BOM_Manufacturer Part") "GRM31B7U3A471JW31L")
        (field (name "BOM_Supplier Part") "C97936")
      )
      (libsource (lib "") (part "GRM31B7U3A471JW31L"))
    )
    (comp (ref "C139")
      (value "1nF")
      (fields
        (field (name "BOM_Manufacturer Part") "GRM31B7U3A471JW31L")
        (field (name "BOM_Supplier Part") "C97936")
      )
      (libsource (lib "") (part "GRM31B7U3A471JW31L"))
    )
    (comp (ref "C140")
      (value "1nF")
      (fields
        (field (name "BOM_Manufacturer Part") "GRM31B7U3A471JW31L")
        (field (name "BOM_Supplier Part") "C97936")
      )
      (libsource (lib "") (part "GRM31B7U3A471JW31L"))
    )
    (comp (ref "C141")
      (value "1nF")
      (fields
        (field (name "BOM_Manufacturer Part") "GRM31B7U3A471JW31L")
        (field (name "BOM_Supplier Part") "C97936")
      )
      (libsource (lib "") (part "GRM31B7U3A471JW31L"))
    )
    (comp (ref "C142")
      (value "1nF")
      (fields
        (field (name "BOM_Manufacturer Part") "GRM31B7U3A471JW31L")
        (field (name "BOM_Supplier Part") "C97936")
      )
      (libsource (lib "") (part "GRM31B7U3A471JW31L"))
    )
    (comp (ref "C143")
      (value "1nF")
      (fields
        (field (name "BOM_Manufacturer Part") "GRM31B7U3A471JW31L")
        (field (name "BOM_Supplier Part") "C97936")
      )
      (libsource (lib "") (part "GRM31B7U3A471JW31L"))
    )
    (comp (ref "C144")
      (value "1nF")
      (fields
        (field (name "BOM_Manufacturer Part") "GRM31B7U3A471JW31L")
        (field (name "BOM_Supplier Part") "C97936")
      )
      (libsource (lib "") (part "GRM31B7U3A471JW31L"))
    )
    (comp (ref "C145")
      (value "1nF")
      (fields
        (field (name "BOM_Manufacturer Part") "GRM31B7U3A471JW31L")
        (field (name "BOM_Supplier Part") "C97936")
      )
      (libsource (lib "") (part "GRM31B7U3A471JW31L"))
    )
    (comp (ref "C146")
      (value "1nF")
      (fields
        (field (name "BOM_Manufacturer Part") "GRM31B7U3A471JW31L")
        (field (name "BOM_Supplier Part") "C97936")
      )
      (libsource (lib "") (part "GRM31B7U3A471JW31L"))
    )
    (comp (ref "C147")
      (value "1nF")
      (fields
        (field (name "BOM_Manufacturer Part") "GRM31B7U3A471JW31L")
        (field (name "BOM_Supplier Part") "C97936")
      )
      (libsource (lib "") (part "GRM31B7U3A471JW31L"))
    )
    (comp (ref "C148")
      (value "1nF")
      (fields
        (field (name "BOM_Manufacturer Part") "GRM31B7U3A471JW31L")
        (field (name "BOM_Supplier Part") "C97936")
      )
      (libsource (lib "") (part "GRM31B7U3A471JW31L"))
    )
    (comp (ref "CON1") (value "POWER IN") (libsource (lib "") (part "XH2.54-2P")))
    (comp (ref "D4")
      (value "1N5819")
      (fields (field (name "BOM_Manufacturer Part") "1N4007") (field (name "BOM_Supplier Part") "C106903"))
      (libsource (lib "") (part "1N4007_1"))
    )
    (comp (ref "D5")
      (value "1N5819")
      (fields (field (name "BOM_Manufacturer Part") "1N4007") (field (name "BOM_Supplier Part") "C106903"))
      (libsource (lib "") (part "1N4007"))
    )
    (comp (ref "D6")
      (value "SS34")
      (fields (field (name "BOM_Supplier Part") "C13763"))
      (libsource (lib "") (part "SS34_1"))
    )
    (comp (ref "D7")
      (value "SS34")
      (fields (field (name "BOM_Supplier Part") "C13763"))
      (libsource (lib "") (part "SS34"))
    )
    (comp (ref "D8")
      (value "SS34")
      (fields (field (name "BOM_Supplier Part") "C13763"))
      (libsource (lib "") (part "SS34_2"))
    )
    (comp (ref "D9")
      (value "BZT52C8V2")
      (fields (field (name "BOM_Supplier Part") "C2122"))
      (libsource (lib "") (part "BZT52C8V2"))
    )
    (comp (ref "D10")
      (value "SS34")
      (fields (field (name "BOM_Supplier Part") "C13763"))
      (libsource (lib "") (part "SS34_1"))
    )
    (comp (ref "D11")
      (value "1N5819")
      (fields (field (name "BOM_Manufacturer Part") "1N4007") (field (name "BOM_Supplier Part") "C106903"))
      (libsource (lib "") (part "1N4007"))
    )
    (comp (ref "D12")
      (value "1N5819")
      (fields (field (name "BOM_Manufacturer Part") "1N4007") (field (name "BOM_Supplier Part") "C106903"))
      (libsource (lib "") (part "1N4007"))
    )
    (comp (ref "D13")
      (value "1N5819")
      (fields (field (name "BOM_Manufacturer Part") "1N4007") (field (name "BOM_Supplier Part") "C106903"))
      (libsource (lib "") (part "1N4007_1"))
    )
    (comp (ref "L5")
      (value "10uH")
      (fields
        (field (name "BOM_Manufacturer Part") "SMDRI74-101MT")
        (field (name "BOM_Supplier Part") "C36970")
      )
      (libsource (lib "") (part "SMDRI74-101MT"))
    )
    (comp (ref "L6")
      (value "10uH")
      (fields
        (field (name "BOM_Manufacturer Part") "SMDRI74-101MT")
        (field (name "BOM_Supplier Part") "C36970")
      )
      (libsource (lib "") (part "SMDRI74-101MT_1"))
    )
    (comp (ref "Q7")
      (value "SS8050-H")
      (fields (field (name "BOM_Supplier Part") "C699255"))
      (libsource (lib "") (part "SS8050-H"))
    )
    (comp (ref "Q8")
      (value "CJ3401")
      (fields (field (name "BOM_Supplier Part") "C13799"))
      (libsource (lib "") (part "CJ3401"))
    )
    (comp (ref "R46") (value "1K") (libsource (lib "") (part "R_0805_EU_3")))
    (comp (ref "R47") (value "10K") (libsource (lib "") (part "R_0805_EU_1")))
    (comp (ref "R48") (value "10K") (libsource (lib "") (part "R_0805_EU")))
    (comp (ref "R51") (value "10K") (libsource (lib "") (part "R_0805_EU")))
    (comp (ref "R53") (value "10K") (libsource (lib "") (part "R_0805_EU")))
    (comp (ref "R56") (value "12K") (libsource (lib "") (part "R_0805_EU")))
    (comp (ref "R57") (value "1K") (libsource (lib "") (part "R_0805_EU")))
    (comp (ref "R58") (value "10K") (libsource (lib "") (part "R_0805_EU")))
    (comp (ref "R59") (value "1K") (libsource (lib "") (part "R_0805_EU")))
    (comp (ref "R60") (value "1") (libsource (lib "") (part "R_0805_EU")))
    (comp (ref "R61") (value "1") (libsource (lib "") (part "R_0805_EU")))
    (comp (ref "R81") (value "100") (libsource (lib "") (part "R_0805_EU_2")))
    (comp (ref "S1")
      (value "POWER ON/OFF")
      (fields
        (field (name "BOM_Manufacturer Part") "BUTTON")
        (field (name "BOM_Supplier Part") "C9900015607")
      )
      (libsource (lib "") (part "BUTTON"))
    )
    (comp (ref "U6")
      (value "AMS1117-2.5")
      (fields (field (name "BOM_Supplier Part") "C963405"))
      (libsource (lib "") (part "AMS1117-2.5_C963405"))
    )
    (comp (ref "U9")
      (value "6210_2046/33")
      (fields
        (field (name "BOM_Manufacturer Part") "TC1108-3.3VDBTR")
        (field (name "BOM_Supplier Part") "C622711")
      )
      (libsource (lib "") (part "6210_2046/33"))
    )
    (comp (ref "U10")
      (value "AMS1117-1.2")
      (fields
        (field (name "BOM_Manufacturer Part") "AMS1117-2.5")
        (field (name "BOM_Supplier Part") "C963405")
      )
      (libsource (lib "") (part "AMS1117-2.5_C963405"))
    )
    (comp (ref "U11")
      (value "TLV70033DDCT")
      (fields (field (name "BOM_Supplier Part") "C2877582"))
      (libsource (lib "") (part "TLV70033DDCT"))
    )
    (comp (ref "U12")
      (value "LM6206N3 (65Z5)")
      (fields
        (field (name "BOM_Manufacturer Part") "LM6206N3")
        (field (name "BOM_Supplier Part") "LM6206N3 (662K)")
      )
      (libsource (lib "") (part "LM6206N3"))
    )
    (comp (ref "U15")
      (value "TPS61041")
      (fields
        (field (name "BOM_Manufacturer Part") "TPS61040DBVR")
        (field (name "BOM_Supplier Part") "C7722")
      )
      (libsource (lib "") (part "TPS61040DBVR"))
    )
    (comp (ref "U16")
      (value "PT4103B23F")
      (fields (field (name "BOM_Supplier Part") "C19861"))
      (libsource (lib "") (part "PT4103B23F"))
    )
    (comp (ref "U21") (value "TL432") (libsource (lib "") (part "TL431AIDBZTG4")))
    (comp (ref "ZD1")
      (value "BZT52C5V6")
      (fields (field (name "BOM_Supplier Part") "C2119"))
      (libsource (lib "") (part "BZT52C5V6"))
    )
    (comp (ref "C14")
      (value "1nF")
      (fields
        (field (name "BOM_Manufacturer Part") "GRM31B7U3A471JW31L")
        (field (name "BOM_Supplier Part") "C97936")
      )
      (libsource (lib "") (part "GRM31B7U3A471JW31L"))
    )
    (comp (ref "C15")
      (value "1nF")
      (fields
        (field (name "BOM_Manufacturer Part") "GRM31B7U3A471JW31L")
        (field (name "BOM_Supplier Part") "C97936")
      )
      (libsource (lib "") (part "GRM31B7U3A471JW31L"))
    )
    (comp (ref "C16")
      (value "1nF")
      (fields
        (field (name "BOM_Manufacturer Part") "GRM31B7U3A471JW31L")
        (field (name "BOM_Supplier Part") "C97936")
      )
      (libsource (lib "") (part "GRM31B7U3A471JW31L"))
    )
    (comp (ref "C17")
      (value "1nF")
      (fields
        (field (name "BOM_Manufacturer Part") "GRM31B7U3A471JW31L")
        (field (name "BOM_Supplier Part") "C97936")
      )
      (libsource (lib "") (part "GRM31B7U3A471JW31L"))
    )
    (comp (ref "C18")
      (value "1nF")
      (fields
        (field (name "BOM_Manufacturer Part") "GRM31B7U3A471JW31L")
        (field (name "BOM_Supplier Part") "C97936")
      )
      (libsource (lib "") (part "GRM31B7U3A471JW31L"))
    )
    (comp (ref "C19")
      (value "1nF")
      (fields
        (field (name "BOM_Manufacturer Part") "GRM31B7U3A471JW31L")
        (field (name "BOM_Supplier Part") "C97936")
      )
      (libsource (lib "") (part "GRM31B7U3A471JW31L"))
    )
    (comp (ref "C20")
      (value "1nF")
      (fields
        (field (name "BOM_Manufacturer Part") "GRM31B7U3A471JW31L")
        (field (name "BOM_Supplier Part") "C97936")
      )
      (libsource (lib "") (part "GRM31B7U3A471JW31L"))
    )
    (comp (ref "C21")
      (value "1nF")
      (fields
        (field (name "BOM_Manufacturer Part") "GRM31B7U3A471JW31L")
        (field (name "BOM_Supplier Part") "C97936")
      )
      (libsource (lib "") (part "GRM31B7U3A471JW31L"))
    )
    (comp (ref "C22")
      (value "1nF")
      (fields
        (field (name "BOM_Manufacturer Part") "GRM31B7U3A471JW31L")
        (field (name "BOM_Supplier Part") "C97936")
      )
      (libsource (lib "") (part "GRM31B7U3A471JW31L"))
    )
    (comp (ref "C23")
      (value "1nF")
      (fields
        (field (name "BOM_Manufacturer Part") "GRM31B7U3A471JW31L")
        (field (name "BOM_Supplier Part") "C97936")
      )
      (libsource (lib "") (part "GRM31B7U3A471JW31L"))
    )
    (comp (ref "C24")
      (value "1nF")
      (fields
        (field (name "BOM_Manufacturer Part") "GRM31B7U3A471JW31L")
        (field (name "BOM_Supplier Part") "C97936")
      )
      (libsource (lib "") (part "GRM31B7U3A471JW31L"))
    )
    (comp (ref "C25")
      (value "1nF")
      (fields
        (field (name "BOM_Manufacturer Part") "GRM31B7U3A471JW31L")
        (field (name "BOM_Supplier Part") "C97936")
      )
      (libsource (lib "") (part "GRM31B7U3A471JW31L"))
    )
    (comp (ref "C26")
      (value "1nF")
      (fields
        (field (name "BOM_Manufacturer Part") "GRM31B7U3A471JW31L")
        (field (name "BOM_Supplier Part") "C97936")
      )
      (libsource (lib "") (part "GRM31B7U3A471JW31L"))
    )
    (comp (ref "C27")
      (value "1nF")
      (fields
        (field (name "BOM_Manufacturer Part") "GRM31B7U3A471JW31L")
        (field (name "BOM_Supplier Part") "C97936")
      )
      (libsource (lib "") (part "GRM31B7U3A471JW31L"))
    )
    (comp (ref "C28")
      (value "1nF")
      (fields
        (field (name "BOM_Manufacturer Part") "GRM31B7U3A471JW31L")
        (field (name "BOM_Supplier Part") "C97936")
      )
      (libsource (lib "") (part "GRM31B7U3A471JW31L"))
    )
    (comp (ref "C29")
      (value "1nF")
      (fields
        (field (name "BOM_Manufacturer Part") "GRM31B7U3A471JW31L")
        (field (name "BOM_Supplier Part") "C97936")
      )
      (libsource (lib "") (part "GRM31B7U3A471JW31L"))
    )
    (comp (ref "C30")
      (value "1nF")
      (fields
        (field (name "BOM_Manufacturer Part") "GRM31B7U3A471JW31L")
        (field (name "BOM_Supplier Part") "C97936")
      )
      (libsource (lib "") (part "GRM31B7U3A471JW31L"))
    )
    (comp (ref "C80")
      (value "1nF")
      (fields
        (field (name "BOM_Manufacturer Part") "GRM31B7U3A471JW31L")
        (field (name "BOM_Supplier Part") "C97936")
      )
      (libsource (lib "") (part "GRM31B7U3A471JW31L"))
    )
    (comp (ref "C81")
      (value "1nF")
      (fields
        (field (name "BOM_Manufacturer Part") "GRM31B7U3A471JW31L")
        (field (name "BOM_Supplier Part") "C97936")
      )
      (libsource (lib "") (part "GRM31B7U3A471JW31L"))
    )
    (comp (ref "C82")
      (value "1nF")
      (fields
        (field (name "BOM_Manufacturer Part") "GRM31B7U3A471JW31L")
        (field (name "BOM_Supplier Part") "C97936")
      )
      (libsource (lib "") (part "GRM31B7U3A471JW31L"))
    )
    (comp (ref "C83")
      (value "1nF")
      (fields
        (field (name "BOM_Manufacturer Part") "GRM31B7U3A471JW31L")
        (field (name "BOM_Supplier Part") "C97936")
      )
      (libsource (lib "") (part "GRM31B7U3A471JW31L"))
    )
    (comp (ref "C84")
      (value "1nF")
      (fields
        (field (name "BOM_Manufacturer Part") "GRM31B7U3A471JW31L")
        (field (name "BOM_Supplier Part") "C97936")
      )
      (libsource (lib "") (part "GRM31B7U3A471JW31L_1"))
    )
    (comp (ref "C85")
      (value "1nF")
      (fields
        (field (name "BOM_Manufacturer Part") "GRM31B7U3A471JW31L")
        (field (name "BOM_Supplier Part") "C97936")
      )
      (libsource (lib "") (part "GRM31B7U3A471JW31L"))
    )
    (comp (ref "D14")
      (value "1N5819")
      (fields (field (name "BOM_Manufacturer Part") "1N4007") (field (name "BOM_Supplier Part") "C106903"))
      (libsource (lib "") (part "1N4007"))
    )
    (comp (ref "D15")
      (value "1N5819")
      (fields (field (name "BOM_Manufacturer Part") "1N4007") (field (name "BOM_Supplier Part") "C106903"))
      (libsource (lib "") (part "1N4007"))
    )
    (comp (ref "R22") (value "200") (libsource (lib "") (part "R_0805_EU_1")))
    (comp (ref "R23") (value "200") (libsource (lib "") (part "R_0805_EU_1")))
    (comp (ref "R24") (value "1K") (libsource (lib "") (part "R_0805_EU_1")))
    (comp (ref "R25") (value "1K") (libsource (lib "") (part "R_0805_EU_1")))
    (comp (ref "R26") (value "1K") (libsource (lib "") (part "R_0805_EU_1")))
    (comp (ref "R27") (value "1K") (libsource (lib "") (part "R_0805_EU_1")))
    (comp (ref "R34") (value "1K5") (libsource (lib "") (part "R_0805_EU_1")))
    (comp (ref "R35") (value "750") (libsource (lib "") (part "R_0805_EU")))
    (comp (ref "R52") (value "1K5") (libsource (lib "") (part "R_0805_EU_1")))
    (comp (ref "R54") (value "750") (libsource (lib "") (part "R_0805_EU")))
    (comp (ref "R55") (value "1K5") (libsource (lib "") (part "R_0805_EU_1")))
    (comp (ref "R82") (value "10") (libsource (lib "") (part "R_0805_EU")))
    (comp (ref "R83") (value "750") (libsource (lib "") (part "R_0805_EU")))
    (comp (ref "R84") (value "1K5") (libsource (lib "") (part "R_0805_EU_1")))
    (comp (ref "R85") (value "750") (libsource (lib "") (part "R_0805_EU")))
    (comp (ref "R86") (value "1K5") (libsource (lib "") (part "R_0805_EU_1")))
    (comp (ref "R87") (value "750") (libsource (lib "") (part "R_0805_EU")))
    (comp (ref "R88") (value "1K5") (libsource (lib "") (part "R_0805_EU_1")))
    (comp (ref "R89") (value "750") (libsource (lib "") (part "R_0805_EU")))
    (comp (ref "R90") (value "1K5") (libsource (lib "") (part "R_0805_EU_1")))
    (comp (ref "R91") (value "750") (libsource (lib "") (part "R_0805_EU")))
    (comp (ref "R92") (value "1K5") (libsource (lib "") (part "R_0805_EU_1")))
    (comp (ref "R93") (value "1K5") (libsource (lib "") (part "R_0805_EU")))
    (comp (ref "R94") (value "33K") (libsource (lib "") (part "R_0805_EU")))
    (comp (ref "R95") (value "1") (libsource (lib "") (part "R_0805_EU_2")))
    (comp (ref "R96") (value "100") (libsource (lib "") (part "R_0805_EU_1")))
    (comp (ref "R97") (value "100") (libsource (lib "") (part "R_0805_EU_1")))
    (comp (ref "RF3")
      (value "BNC")
      (fields
        (field (name "BOM_Manufacturer Part") "DOSIN-801-0080")
        (field (name "BOM_Supplier Part") "C521219")
      )
      (libsource (lib "") (part "DOSIN-801-0080"))
    )
    (comp (ref "U7") (value "AD9288BSTZ-100") (libsource (lib "") (part "AD9288BSTZ-100")))
    (comp (ref "U8") (value "AD9288BSTZ-100") (libsource (lib "") (part "AD9288BSTZ-100")))
    (comp (ref "U14")
      (value "RS8751XF")
      (fields (field (name "BOM_Supplier Part") "C236995"))
      (libsource (lib "") (part "RS8751XF"))
    )
    (comp (ref "C120")
      (value "1nF")
      (fields
        (field (name "BOM_Manufacturer Part") "GRM31B7U3A471JW31L")
        (field (name "BOM_Supplier Part") "C97936")
      )
      (libsource (lib "") (part "GRM31B7U3A471JW31L"))
    )
    (comp (ref "C131")
      (value "1nF")
      (fields
        (field (name "BOM_Manufacturer Part") "GRM31B7U3A471JW31L")
        (field (name "BOM_Supplier Part") "C97936")
      )
      (libsource (lib "") (part "GRM31B7U3A471JW31L"))
    )
    (comp (ref "C132")
      (value "1nF")
      (fields
        (field (name "BOM_Manufacturer Part") "GRM31B7U3A471JW31L")
        (field (name "BOM_Supplier Part") "C97936")
      )
      (libsource (lib "") (part "GRM31B7U3A471JW31L"))
    )
    (comp (ref "C151")
      (value "1nF")
      (fields
        (field (name "BOM_Manufacturer Part") "GRM31B7U3A471JW31L")
        (field (name "BOM_Supplier Part") "C97936")
      )
      (libsource (lib "") (part "GRM31B7U3A471JW31L"))
    )
    (comp (ref "C152")
      (value "1nF")
      (fields
        (field (name "BOM_Manufacturer Part") "GRM31B7U3A471JW31L")
        (field (name "BOM_Supplier Part") "C97936")
      )
      (libsource (lib "") (part "GRM31B7U3A471JW31L"))
    )
    (comp (ref "C153")
      (value "1nF")
      (fields
        (field (name "BOM_Manufacturer Part") "GRM31B7U3A471JW31L")
        (field (name "BOM_Supplier Part") "C97936")
      )
      (libsource (lib "") (part "GRM31B7U3A471JW31L"))
    )
    (comp (ref "C154")
      (value "1nF")
      (fields
        (field (name "BOM_Manufacturer Part") "GRM31B7U3A471JW31L")
        (field (name "BOM_Supplier Part") "C97936")
      )
      (libsource (lib "") (part "GRM31B7U3A471JW31L"))
    )
    (comp (ref "C155")
      (value "1nF")
      (fields
        (field (name "BOM_Manufacturer Part") "GRM31B7U3A471JW31L")
        (field (name "BOM_Supplier Part") "C97936")
      )
      (libsource (lib "") (part "GRM31B7U3A471JW31L"))
    )
    (comp (ref "C156")
      (value "1nF")
      (fields
        (field (name "BOM_Manufacturer Part") "GRM31B7U3A471JW31L")
        (field (name "BOM_Supplier Part") "C97936")
      )
      (libsource (lib "") (part "GRM31B7U3A471JW31L"))
    )
    (comp (ref "C157")
      (value "1nF")
      (fields
        (field (name "BOM_Manufacturer Part") "GRM31B7U3A471JW31L")
        (field (name "BOM_Supplier Part") "C97936")
      )
      (libsource (lib "") (part "GRM31B7U3A471JW31L"))
    )
    (comp (ref "C158")
      (value "1nF")
      (fields
        (field (name "BOM_Manufacturer Part") "GRM31B7U3A471JW31L")
        (field (name "BOM_Supplier Part") "C97936")
      )
      (libsource (lib "") (part "GRM31B7U3A471JW31L"))
    )
    (comp (ref "C159")
      (value "1nF")
      (fields
        (field (name "BOM_Manufacturer Part") "GRM31B7U3A471JW31L")
        (field (name "BOM_Supplier Part") "C97936")
      )
      (libsource (lib "") (part "GRM31B7U3A471JW31L"))
    )
    (comp (ref "C160")
      (value "1nF")
      (fields
        (field (name "BOM_Manufacturer Part") "GRM31B7U3A471JW31L")
        (field (name "BOM_Supplier Part") "C97936")
      )
      (libsource (lib "") (part "GRM31B7U3A471JW31L"))
    )
    (comp (ref "C161")
      (value "1nF")
      (fields
        (field (name "BOM_Manufacturer Part") "GRM31B7U3A471JW31L")
        (field (name "BOM_Supplier Part") "C97936")
      )
      (libsource (lib "") (part "GRM31B7U3A471JW31L"))
    )
    (comp (ref "C162")
      (value "1nF")
      (fields
        (field (name "BOM_Manufacturer Part") "GRM31B7U3A471JW31L")
        (field (name "BOM_Supplier Part") "C97936")
      )
      (libsource (lib "") (part "GRM31B7U3A471JW31L"))
    )
    (comp (ref "C163")
      (value "1nF")
      (fields
        (field (name "BOM_Manufacturer Part") "GRM31B7U3A471JW31L")
        (field (name "BOM_Supplier Part") "C97936")
      )
      (libsource (lib "") (part "GRM31B7U3A471JW31L"))
    )
    (comp (ref "C164")
      (value "1nF")
      (fields
        (field (name "BOM_Manufacturer Part") "GRM31B7U3A471JW31L")
        (field (name "BOM_Supplier Part") "C97936")
      )
      (libsource (lib "") (part "GRM31B7U3A471JW31L"))
    )
    (comp (ref "C165")
      (value "1nF")
      (fields
        (field (name "BOM_Manufacturer Part") "GRM31B7U3A471JW31L")
        (field (name "BOM_Supplier Part") "C97936")
      )
      (libsource (lib "") (part "GRM31B7U3A471JW31L"))
    )
    (comp (ref "C166")
      (value "1nF")
      (fields
        (field (name "BOM_Manufacturer Part") "GRM31B7U3A471JW31L")
        (field (name "BOM_Supplier Part") "C97936")
      )
      (libsource (lib "") (part "GRM31B7U3A471JW31L"))
    )
    (comp (ref "C167")
      (value "1nF")
      (fields
        (field (name "BOM_Manufacturer Part") "GRM31B7U3A471JW31L")
        (field (name "BOM_Supplier Part") "C97936")
      )
      (libsource (lib "") (part "GRM31B7U3A471JW31L"))
    )
    (comp (ref "D16")
      (value "1N5819")
      (fields (field (name "BOM_Manufacturer Part") "1N4007") (field (name "BOM_Supplier Part") "C106903"))
      (libsource (lib "") (part "1N4007"))
    )
    (comp (ref "J6")
      (value "GD32E230_DEBUG")
      (fields (field (name "BOM_Supplier Part") "C66690"))
      (libsource (lib "") (part "HDR-M-2.54_2x2"))
    )
    (comp (ref "R101") (value "10K") (libsource (lib "") (part "R_0805_EU")))
    (comp (ref "R102") (value "1K") (libsource (lib "") (part "R_0805_EU")))
    (comp (ref "R103") (value "1K") (libsource (lib "") (part "R_0805_EU")))
    (comp (ref "R104") (value "6K2") (libsource (lib "") (part "R_0805_EU")))
    (comp (ref "R105") (value "1K") (libsource (lib "") (part "R_0805_EU")))
    (comp (ref "R106") (value "1K") (libsource (lib "") (part "R_0805_EU")))
    (comp (ref "R107") (value "6K2") (libsource (lib "") (part "R_0805_EU")))
    (comp (ref "R108") (value "6K2") (libsource (lib "") (part "R_0805_EU")))
    (comp (ref "R109") (value "1K") (libsource (lib "") (part "R_0805_EU")))
    (comp (ref "R110") (value "1K") (libsource (lib "") (part "R_0805_EU")))
    (comp (ref "R111") (value "6K2") (libsource (lib "") (part "R_0805_EU")))
    (comp (ref "R112") (value "1K") (libsource (lib "") (part "R_0805_EU")))
    (comp (ref "R113") (value "1K") (libsource (lib "") (part "R_0805_EU")))
    (comp (ref "R114") (value "1K") (libsource (lib "") (part "R_0805_EU")))
    (comp (ref "R115") (value "1K") (libsource (lib "") (part "R_0805_EU")))
    (comp (ref "R116") (value "6K2") (libsource (lib "") (part "R_0805_EU")))
    (comp (ref "R117") (value "1K") (libsource (lib "") (part "R_0805_EU")))
    (comp (ref "R118") (value "1K") (libsource (lib "") (part "R_0805_EU")))
    (comp (ref "R119") (value "6K2") (libsource (lib "") (part "R_0805_EU")))
    (comp (ref "R120") (value "6K2") (libsource (lib "") (part "R_0805_EU")))
    (comp (ref "R121") (value "1K") (libsource (lib "") (part "R_0805_EU")))
    (comp (ref "R122") (value "1K") (libsource (lib "") (part "R_0805_EU")))
    (comp (ref "R123") (value "6K2") (libsource (lib "") (part "R_0805_EU")))
    (comp (ref "R124") (value "1K") (libsource (lib "") (part "R_0805_EU")))
    (comp (ref "R125") (value "1K") (libsource (lib "") (part "R_0805_EU")))
    (comp (ref "R126") (value "6K2") (libsource (lib "") (part "R_0805_EU")))
    (comp (ref "R127") (value "1K") (libsource (lib "") (part "R_0805_EU")))
    (comp (ref "R128") (value "1K") (libsource (lib "") (part "R_0805_EU")))
    (comp (ref "R129") (value "6K2") (libsource (lib "") (part "R_0805_EU")))
    (comp (ref "R130") (value "1K") (libsource (lib "") (part "R_0805_EU")))
    (comp (ref "R131") (value "1K") (libsource (lib "") (part "R_0805_EU")))
    (comp (ref "R132") (value "1K") (libsource (lib "") (part "R_0805_EU")))
    (comp (ref "R133") (value "1K") (libsource (lib "") (part "R_0805_EU")))
    (comp (ref "R134") (value "6K2") (libsource (lib "") (part "R_0805_EU")))
    (comp (ref "R135") (value "1K") (libsource (lib "") (part "R_0805_EU")))
    (comp (ref "R136") (value "1K") (libsource (lib "") (part "R_0805_EU")))
    (comp (ref "R137") (value "6K2") (libsource (lib "") (part "R_0805_EU")))
    (comp (ref "R138") (value "1K") (libsource (lib "") (part "R_0805_EU")))
    (comp (ref "R139") (value "1K") (libsource (lib "") (part "R_0805_EU")))
    (comp (ref "R140") (value "6K2") (libsource (lib "") (part "R_0805_EU")))
    (comp (ref "R141") (value "1K") (libsource (lib "") (part "R_0805_EU")))
    (comp (ref "R142") (value "1K") (libsource (lib "") (part "R_0805_EU")))
    (comp (ref "R143") (value "6K2") (libsource (lib "") (part "R_0805_EU")))
    (comp (ref "R144") (value "6K2") (libsource (lib "") (part "R_0805_EU")))
    (comp (ref "R145") (value "1K") (libsource (lib "") (part "R_0805_EU")))
    (comp (ref "R146") (value "1K") (libsource (lib "") (part "R_0805_EU")))
    (comp (ref "R147") (value "6K2") (libsource (lib "") (part "R_0805_EU")))
    (comp (ref "R148") (value "1K") (libsource (lib "") (part "R_0805_EU")))
    (comp (ref "R149") (value "1K") (libsource (lib "") (part "R_0805_EU")))
    (comp (ref "R150") (value "10K") (libsource (lib "") (part "R_0805_EU_1")))
    (comp (ref "R151") (value "10K") (libsource (lib "") (part "R_0805_EU_1")))
    (comp (ref "R152") (value "10K") (libsource (lib "") (part "R_0805_EU_1")))
    (comp (ref "R153") (value "10K") (libsource (lib "") (part "R_0805_EU_1")))
    (comp (ref "R154") (value "10K") (libsource (lib "") (part "R_0805_EU_1")))
    (comp (ref "R155") (value "10K") (libsource (lib "") (part "R_0805_EU_1")))
    (comp (ref "R156") (value "10K") (libsource (lib "") (part "R_0805_EU")))
    (comp (ref "R157") (value "10K") (libsource (lib "") (part "R_0805_EU")))
    (comp (ref "R158") (value "10K") (libsource (lib "") (part "R_0805_EU")))
    (comp (ref "R159") (value "10K") (libsource (lib "") (part "R_0805_EU")))
    (comp (ref "R160") (value "10K") (libsource (lib "") (part "R_0805_EU")))
    (comp (ref "R161") (value "10K") (libsource (lib "") (part "R_0805_EU")))
    (comp (ref "S2")
      (value "DOWN")
      (fields
        (field (name "BOM_Manufacturer Part") "BUTTON")
        (field (name "BOM_Supplier Part") "C9900015607")
      )
      (libsource (lib "") (part "BUTTON"))
    )
    (comp (ref "S3")
      (value "LEFT")
      (fields
        (field (name "BOM_Manufacturer Part") "BUTTON")
        (field (name "BOM_Supplier Part") "C9900015607")
      )
      (libsource (lib "") (part "BUTTON"))
    )
    (comp (ref "S4")
      (value "V_CUR")
      (fields
        (field (name "BOM_Manufacturer Part") "BUTTON")
        (field (name "BOM_Supplier Part") "C9900015607")
      )
      (libsource (lib "") (part "BUTTON"))
    )
    (comp (ref "S5")
      (value "RIGHT")
      (fields
        (field (name "BOM_Manufacturer Part") "BUTTON")
        (field (name "BOM_Supplier Part") "C9900015607")
      )
      (libsource (lib "") (part "BUTTON"))
    )
    (comp (ref "S6")
      (value "UP")
      (fields
        (field (name "BOM_Manufacturer Part") "BUTTON")
        (field (name "BOM_Supplier Part") "C9900015607")
      )
      (libsource (lib "") (part "BUTTON"))
    )
    (comp (ref "S7")
      (value "OK")
      (fields
        (field (name "BOM_Manufacturer Part") "BUTTON")
        (field (name "BOM_Supplier Part") "C9900015607")
      )
      (libsource (lib "") (part "BUTTON"))
    )
    (comp (ref "S8")
      (value "S_PIC")
      (fields
        (field (name "BOM_Manufacturer Part") "BUTTON")
        (field (name "BOM_Supplier Part") "C9900015607")
      )
      (libsource (lib "") (part "BUTTON"))
    )
    (comp (ref "S9")
      (value "MENU")
      (fields
        (field (name "BOM_Manufacturer Part") "BUTTON")
        (field (name "BOM_Supplier Part") "C9900015607")
      )
      (libsource (lib "") (part "BUTTON"))
    )
    (comp (ref "S10")
      (value "AUTO")
      (fields
        (field (name "BOM_Manufacturer Part") "BUTTON")
        (field (name "BOM_Supplier Part") "C9900015607")
      )
      (libsource (lib "") (part "BUTTON"))
    )
    (comp (ref "S11")
      (value "RUN/STOP")
      (fields
        (field (name "BOM_Manufacturer Part") "BUTTON")
        (field (name "BOM_Supplier Part") "C9900015607")
      )
      (libsource (lib "") (part "BUTTON"))
    )
    (comp (ref "S12")
      (value "H_CUR")
      (fields
        (field (name "BOM_Manufacturer Part") "BUTTON")
        (field (name "BOM_Supplier Part") "C9900015607")
      )
      (libsource (lib "") (part "BUTTON"))
    )
    (comp (ref "S13")
      (value "S_WAV")
      (fields
        (field (name "BOM_Manufacturer Part") "BUTTON")
        (field (name "BOM_Supplier Part") "C9900015607")
      )
      (libsource (lib "") (part "BUTTON"))
    )
    (comp (ref "S14")
      (value "50%")
      (fields
        (field (name "BOM_Manufacturer Part") "BUTTON")
        (field (name "BOM_Supplier Part") "C9900015607")
      )
      (libsource (lib "") (part "BUTTON"))
    )
    (comp (ref "S15")
      (value "CHX")
      (fields
        (field (name "BOM_Manufacturer Part") "BUTTON")
        (field (name "BOM_Supplier Part") "C9900015607")
      )
      (libsource (lib "") (part "BUTTON"))
    )
    (comp (ref "S16")
      (value "EDGE")
      (fields
        (field (name "BOM_Manufacturer Part") "BUTTON")
        (field (name "BOM_Supplier Part") "C9900015607")
      )
      (libsource (lib "") (part "BUTTON"))
    )
    (comp (ref "S17")
      (value "MODE")
      (fields
        (field (name "BOM_Manufacturer Part") "BUTTON")
        (field (name "BOM_Supplier Part") "C9900015607")
      )
      (libsource (lib "") (part "BUTTON"))
    )
    (comp (ref "S18")
      (value "F2")
      (fields
        (field (name "BOM_Manufacturer Part") "BUTTON")
        (field (name "BOM_Supplier Part") "C9900015607")
      )
      (libsource (lib "") (part "BUTTON"))
    )
    (comp (ref "S19")
      (value "F1")
      (fields
        (field (name "BOM_Manufacturer Part") "BUTTON")
        (field (name "BOM_Supplier Part") "C9900015607")
      )
      (libsource (lib "") (part "BUTTON"))
    )
    (comp (ref "S20")
      (value "CH2")
      (fields
        (field (name "BOM_Manufacturer Part") "BUTTON")
        (field (name "BOM_Supplier Part") "C9900015607")
      )
      (libsource (lib "") (part "BUTTON"))
    )
    (comp (ref "S21")
      (value "CH1_CONF")
      (fields
        (field (name "BOM_Manufacturer Part") "BUTTON")
        (field (name "BOM_Supplier Part") "C9900015607")
      )
      (libsource (lib "") (part "BUTTON"))
    )
    (comp (ref "S22")
      (value "CH1")
      (fields
        (field (name "BOM_Manufacturer Part") "BUTTON")
        (field (name "BOM_Supplier Part") "C9900015607")
      )
      (libsource (lib "") (part "BUTTON"))
    )
    (comp (ref "S23")
      (value "SLOW")
      (fields
        (field (name "BOM_Manufacturer Part") "BUTTON")
        (field (name "BOM_Supplier Part") "C9900015607")
      )
      (libsource (lib "") (part "BUTTON"))
    )
    (comp (ref "S24")
      (value "ORIG")
      (fields
        (field (name "BOM_Manufacturer Part") "BUTTON")
        (field (name "BOM_Supplier Part") "C9900015607")
      )
      (libsource (lib "") (part "BUTTON"))
    )
    (comp (ref "S25")
      (value "CH2_CONF")
      (fields
        (field (name "BOM_Manufacturer Part") "BUTTON")
        (field (name "BOM_Supplier Part") "C9900015607")
      )
      (libsource (lib "") (part "BUTTON"))
    )
    (comp (ref "S26")
      (value "F6")
      (fields
        (field (name "BOM_Manufacturer Part") "BUTTON")
        (field (name "BOM_Supplier Part") "C9900015607")
      )
      (libsource (lib "") (part "BUTTON"))
    )
    (comp (ref "S27")
      (value "F5")
      (fields
        (field (name "BOM_Manufacturer Part") "BUTTON")
        (field (name "BOM_Supplier Part") "C9900015607")
      )
      (libsource (lib "") (part "BUTTON"))
    )
    (comp (ref "S28")
      (value "F4")
      (fields
        (field (name "BOM_Manufacturer Part") "BUTTON")
        (field (name "BOM_Supplier Part") "C9900015607")
      )
      (libsource (lib "") (part "BUTTON"))
    )
    (comp (ref "S29")
      (value "F3")
      (fields
        (field (name "BOM_Manufacturer Part") "BUTTON")
        (field (name "BOM_Supplier Part") "C9900015607")
      )
      (libsource (lib "") (part "BUTTON"))
    )
    (comp (ref "S30")
      (value "NEXT")
      (fields
        (field (name "BOM_Manufacturer Part") "BUTTON")
        (field (name "BOM_Supplier Part") "C9900015607")
      )
      (libsource (lib "") (part "BUTTON"))
    )
    (comp (ref "S31")
      (value "GEN")
      (fields
        (field (name "BOM_Manufacturer Part") "BUTTON")
        (field (name "BOM_Supplier Part") "C9900015607")
      )
      (libsource (lib "") (part "BUTTON"))
    )
    (comp (ref "S32")
      (value "SEL")
      (fields
        (field (name "BOM_Manufacturer Part") "BUTTON")
        (field (name "BOM_Supplier Part") "C9900015607")
      )
      (libsource (lib "") (part "BUTTON"))
    )
    (comp (ref "S33")
      (value "SEL_ALL")
      (fields
        (field (name "BOM_Manufacturer Part") "BUTTON")
        (field (name "BOM_Supplier Part") "C9900015607")
      )
      (libsource (lib "") (part "BUTTON"))
    )
    (comp (ref "S34")
      (value "DEL")
      (fields
        (field (name "BOM_Manufacturer Part") "BUTTON")
        (field (name "BOM_Supplier Part") "C9900015607")
      )
      (libsource (lib "") (part "BUTTON"))
    )
    (comp (ref "S35")
      (value "LAST")
      (fields
        (field (name "BOM_Manufacturer Part") "BUTTON")
        (field (name "BOM_Supplier Part") "C9900015607")
      )
      (libsource (lib "") (part "BUTTON"))
    )
    (comp (ref "SW1") (value "SELECT") (libsource (lib "") (part "Rotary_Encoder")))
    (comp (ref "SW2") (value "CH1 POS") (libsource (lib "") (part "Rotary_Encoder")))
    (comp (ref "SW3") (value "CH2 POS") (libsource (lib "") (part "Rotary_Encoder")))
    (comp (ref "SW4") (value "TRG POS") (libsource (lib "") (part "Rotary_Encoder")))
    (comp (ref "SW5") (value "TRG LVL") (libsource (lib "") (part "Rotary_Encoder")))
    (comp (ref "SW6") (value "TRG RNG") (libsource (lib "") (part "Rotary_Encoder")))
    (comp (ref "SW7") (value "CH2 RNG") (libsource (lib "") (part "Rotary_Encoder")))
    (comp (ref "SW8") (value "CH1 RNG") (libsource (lib "") (part "Rotary_Encoder")))
    (comp (ref "U22")
      (value "GD32E230C8T6")
      (fields (field (name "BOM_Supplier Part") "C380535"))
      (libsource (lib "") (part "GD32E230C8T6"))
    )
  )
  (nets
    (net (code "1") (name "-6V3") (class "Default")
      (node (ref "C93") (pin "1") (pinfunction "1_1") (pintype "input"))
      (node (ref "C94") (pin "1") (pinfunction "1_1") (pintype "input"))
      (node (ref "D9") (pin "1") (pinfunction "K_1") (pintype "unspecified"))
      (node (ref "P3") (pin "42") (pinfunction "42_42") (pintype "unspecified"))
      (node (ref "R58") (pin "2") (pinfunction "2_2") (pintype "unspecified"))
    )
    (net (code "2") (name "1V2") (class "Default")
      (node (ref "C11") (pin "1") (pinfunction "1_1") (pintype "input"))
      (node (ref "C138") (pin "1") (pinfunction "1_1") (pintype "input"))
      (node (ref "C139") (pin "1") (pinfunction "1_1") (pintype "input"))
      (node (ref "C140") (pin "1") (pinfunction "1_1") (pintype "input"))
      (node (ref "C33") (pin "1") (pinfunction "1_1") (pintype "input"))
      (node (ref "C34") (pin "1") (pinfunction "1_1") (pintype "input"))
      (node (ref "C35") (pin "1") (pinfunction "1_1") (pintype "input"))
      (node (ref "C4") (pin "1") (pinfunction "1_1") (pintype "input"))
      (node (ref "C48") (pin "1") (pinfunction "1_1") (pintype "input"))
      (node (ref "C49") (pin "1") (pinfunction "1_1") (pintype "input"))
      (node (ref "C50") (pin "1") (pinfunction "1_1") (pintype "input"))
      (node (ref "C53") (pin "1") (pinfunction "1_1") (pintype "input"))
      (node (ref "C74") (pin "1") (pinfunction "1_1") (pintype "input"))
      (node (ref "C75") (pin "1") (pinfunction "1_1") (pintype "input"))
      (node (ref "C77") (pin "1") (pinfunction "1_1") (pintype "input"))
      (node (ref "C8") (pin "1") (pinfunction "1_1") (pintype "input"))
      (node (ref "C9") (pin "1") (pinfunction "1_1") (pintype "input"))
      (node (ref "L1") (pin "1") (pinfunction "1_1") (pintype "unspecified"))
      (node (ref "L4") (pin "1") (pinfunction "1_1") (pintype "unspecified"))
      (node (ref "U1") (pin "22") (pinfunction "VDD-CORE_22") (pintype "unspecified"))
      (node (ref "U1") (pin "35") (pinfunction "VDD-CORE_35") (pintype "unspecified"))
      (node (ref "U1") (pin "71") (pinfunction "VDD-CORE_71") (pintype "unspecified"))
      (node (ref "U10") (pin "2") (pinfunction "VOUT_2") (pintype "unspecified"))
      (node (ref "U10") (pin "4") (pinfunction "VOUT_4") (pintype "unspecified"))
      (node (ref "U3") (pin "102") (pinfunction "VCCINT_102") (pintype "input"))
      (node (ref "U3") (pin "116") (pinfunction "VCCINT_116") (pintype "input"))
      (node (ref "U3") (pin "134") (pinfunction "VCCINT_134") (pintype "input"))
      (node (ref "U3") (pin "29") (pinfunction "VCCINT_29") (pintype "input"))
      (node (ref "U3") (pin "45") (pinfunction "VCCINT_45") (pintype "input"))
      (node (ref "U3") (pin "5") (pinfunction "VCCINT_5") (pintype "input"))
      (node (ref "U3") (pin "61") (pinfunction "VCCINT_61") (pintype "input"))
      (node (ref "U3") (pin "78") (pinfunction "VCCINT_78") (pintype "input"))
    )
    (net (code "3") (name "2V5") (class "Default")
      (node (ref "C1") (pin "1") (pinfunction "1_1") (pintype "input"))
      (node (ref "C137") (pin "1") (pinfunction "1_1") (pintype "input"))
      (node (ref "C42") (pin "1") (pinfunction "1_1") (pintype "input"))
      (node (ref "C43") (pin "1") (pinfunction "1_1") (pintype "input"))
      (node (ref "C44") (pin "1") (pinfunction "1_1") (pintype "input"))
      (node (ref "C5") (pin "1") (pinfunction "1_1") (pintype "input"))
      (node (ref "C6") (pin "2") (pinfunction "2_2") (pintype "input"))
      (node (ref "C71") (pin "1") (pinfunction "1_1") (pintype "input"))
      (node (ref "C72") (pin "1") (pinfunction "1_1") (pintype "input"))
      (node (ref "C73") (pin "2") (pinfunction "2_2") (pintype "input"))
      (node (ref "J5") (pin "4") (pinfunction "4_4") (pintype "unspecified"))
      (node (ref "R10") (pin "1") (pinfunction "1_1") (pintype "unspecified"))
      (node (ref "R28") (pin "2") (pinfunction "2_2") (pintype "unspecified"))
      (node (ref "R81") (pin "1") (pinfunction "1_1") (pintype "unspecified"))
      (node (ref "R9") (pin "1") (pinfunction "1_1") (pintype "unspecified"))
      (node (ref "U1") (pin "30") (pinfunction "VCC-DRAM_30") (pintype "unspecified"))
      (node (ref "U1") (pin "31") (pinfunction "VCC-DRAM_31") (pintype "unspecified"))
      (node (ref "U1") (pin "32") (pinfunction "VCC-DRAM_32") (pintype "unspecified"))
      (node (ref "U1") (pin "34") (pinfunction "VCC-DRAM_34") (pintype "unspecified"))
      (node (ref "U1") (pin "36") (pinfunction "VCC-DRAM_36") (pintype "unspecified"))
      (node (ref "U3") (pin "107") (pinfunction "VCCA2_107") (pintype "input"))
      (node (ref "U3") (pin "35") (pinfunction "VCCA1_35") (pintype "input"))
      (node (ref "U3") (pin "96") (pinfunction "MSEL1_96") (pintype "input"))
      (node (ref "U6") (pin "2") (pinfunction "VOUT_2") (pintype "unspecified"))
      (node (ref "U6") (pin "4") (pinfunction "VOUT_4") (pintype "unspecified"))
    )
    (net (code "4") (name "3V") (class "Default")
      (node (ref "C47") (pin "1") (pinfunction "1_1") (pintype "input"))
      (node (ref "C54") (pin "1") (pinfunction "1_1") (pintype "input"))
      (node (ref "U1") (pin "80") (pinfunction "AVCC_80") (pintype "unspecified"))
      (node (ref "U12") (pin "2") (pinfunction "Vout_2") (pintype "output"))
    )
    (net (code "5") (name "3V3") (class "Default")
      (node (ref "C36") (pin "1") (pinfunction "1_1") (pintype "input"))
      (node (ref "C37") (pin "1") (pinfunction "1_1") (pintype "input"))
      (node (ref "C38") (pin "1") (pinfunction "1_1") (pintype "input"))
      (node (ref "C39") (pin "1") (pinfunction "1_1") (pintype "input"))
      (node (ref "C40") (pin "1") (pinfunction "1_1") (pintype "input"))
      (node (ref "C58") (pin "1") (pinfunction "1_1") (pintype "input"))
      (node (ref "C62") (pin "1") (pinfunction "1_1") (pintype "input"))
      (node (ref "C63") (pin "1") (pinfunction "1_1") (pintype "input"))
      (node (ref "C64") (pin "1") (pinfunction "1_1") (pintype "input"))
      (node (ref "C76") (pin "1") (pinfunction "1_1") (pintype "input"))
      (node (ref "D12") (pin "1") (pinfunction "1_1") (pintype "unspecified"))
      (node (ref "D14") (pin "1") (pinfunction "1_1") (pintype "unspecified"))
      (node (ref "D16") (pin "2") (pinfunction "2_2") (pintype "unspecified"))
      (node (ref "D3") (pin "2") (pinfunction "2_2") (pintype "unspecified"))
      (node (ref "P2") (pin "4") (pinfunction "VDD_4") (pintype "unspecified"))
      (node (ref "P3") (pin "39") (pinfunction "39_39") (pintype "unspecified"))
      (node (ref "P3") (pin "44") (pinfunction "44_44") (pintype "unspecified"))
      (node (ref "P3") (pin "7") (pinfunction "7_7") (pintype "unspecified"))
      (node (ref "Q1") (pin "2") (pinfunction "E_2") (pintype "input"))
      (node (ref "Q2") (pin "2") (pinfunction "E_2") (pintype "input"))
      (node (ref "Q3") (pin "2") (pinfunction "E_2") (pintype "input"))
      (node (ref "Q4") (pin "2") (pinfunction "E_2") (pintype "input"))
      (node (ref "Q5") (pin "2") (pinfunction "E_2") (pintype "input"))
      (node (ref "Q6") (pin "2") (pinfunction "E_2") (pintype "input"))
      (node (ref "R30") (pin "2") (pinfunction "2_2") (pintype "unspecified"))
      (node (ref "R36") (pin "2") (pinfunction "2_2") (pintype "unspecified"))
      (node (ref "R37") (pin "2") (pinfunction "2_2") (pintype "unspecified"))
      (node (ref "R38") (pin "2") (pinfunction "2_2") (pintype "unspecified"))
      (node (ref "R39") (pin "2") (pinfunction "2_2") (pintype "unspecified"))
      (node (ref "R40") (pin "2") (pinfunction "2_2") (pintype "unspecified"))
      (node (ref "R41") (pin "2") (pinfunction "2_2") (pintype "unspecified"))
      (node (ref "R42") (pin "2") (pinfunction "2_2") (pintype "unspecified"))
      (node (ref "R43") (pin "2") (pinfunction "2_2") (pintype "unspecified"))
      (node (ref "R51") (pin "1") (pinfunction "1_1") (pintype "unspecified"))
      (node (ref "U1") (pin "20") (pinfunction "VCC-IO_20") (pintype "unspecified"))
      (node (ref "U1") (pin "5") (pinfunction "VCC-IO_5") (pintype "unspecified"))
      (node (ref "U1") (pin "50") (pinfunction "VCC-IO_50") (pintype "unspecified"))
      (node (ref "U1") (pin "67") (pinfunction "UVCC_67") (pintype "unspecified"))
      (node (ref "U12") (pin "3") (pinfunction "Vin_3") (pintype "unspecified"))
      (node (ref "U9") (pin "3") (pinfunction "VOUT_3") (pintype "unspecified"))
    )
    (net (code "6") (name "3V3_A") (class "Default")
      (node (ref "C10") (pin "1") (pinfunction "1_1") (pintype "input"))
      (node (ref "C113") (pin "2") (pinfunction "2_2") (pintype "input"))
      (node (ref "C119") (pin "2") (pinfunction "2_2") (pintype "input"))
      (node (ref "C12") (pin "1") (pinfunction "1_1") (pintype "input"))
      (node (ref "C14") (pin "1") (pinfunction "1_1") (pintype "input"))
      (node (ref "C144") (pin "1") (pinfunction "1_1") (pintype "input"))
      (node (ref "C145") (pin "1") (pinfunction "1_1") (pintype "input"))
      (node (ref "C146") (pin "1") (pinfunction "1_1") (pintype "input"))
      (node (ref "C15") (pin "1") (pinfunction "1_1") (pintype "input"))
      (node (ref "C16") (pin "1") (pinfunction "1_1") (pintype "input"))
      (node (ref "C17") (pin "1") (pinfunction "1_1") (pintype "input"))
      (node (ref "C18") (pin "1") (pinfunction "1_1") (pintype "input"))
      (node (ref "C19") (pin "1") (pinfunction "1_1") (pintype "input"))
      (node (ref "C20") (pin "1") (pinfunction "1_1") (pintype "input"))
      (node (ref "C21") (pin "1") (pinfunction "1_1") (pintype "input"))
      (node (ref "C22") (pin "1") (pinfunction "1_1") (pintype "input"))
      (node (ref "C7") (pin "1") (pinfunction "1_1") (pintype "input"))
      (node (ref "C78") (pin "1") (pinfunction "1_1") (pintype "input"))
      (node (ref "C79") (pin "1") (pinfunction "1_1") (pintype "input"))
      (node (ref "C80") (pin "1") (pinfunction "1_1") (pintype "input"))
      (node (ref "D1") (pin "2") (pinfunction "2_2") (pintype "unspecified"))
      (node (ref "D2") (pin "2") (pinfunction "2_2") (pintype "unspecified"))
      (node (ref "R11") (pin "1") (pinfunction "1_1") (pintype "unspecified"))
      (node (ref "R12") (pin "1") (pinfunction "1_1") (pintype "unspecified"))
      (node (ref "R49") (pin "2") (pinfunction "2_2") (pintype "unspecified"))
      (node (ref "R5") (pin "2") (pinfunction "2_2") (pintype "unspecified"))
      (node (ref "R50") (pin "2") (pinfunction "2_2") (pintype "unspecified"))
      (node (ref "R8") (pin "1") (pinfunction "1_1") (pintype "unspecified"))
      (node (ref "U11") (pin "5") (pinfunction "OUT_5") (pintype "unspecified"))
      (node (ref "U13") (pin "1") (pinfunction "VDD_1") (pintype "unspecified"))
      (node (ref "U17") (pin "5") (pinfunction "+V_5") (pintype "passive"))
      (node (ref "U20") (pin "5") (pinfunction "+V_5") (pintype "passive"))
      (node (ref "U3") (pin "117") (pinfunction "VCCIO7_117") (pintype "input"))
      (node (ref "U3") (pin "122") (pinfunction "VCCIO7_122") (pintype "input"))
      (node (ref "U3") (pin "130") (pinfunction "VCCIO8_130") (pintype "input"))
      (node (ref "U3") (pin "139") (pinfunction "VCCIO8_139") (pintype "input"))
      (node (ref "U3") (pin "17") (pinfunction "VCCIO1_17") (pintype "input"))
      (node (ref "U3") (pin "26") (pinfunction "VCCIO2_26") (pintype "input"))
      (node (ref "U3") (pin "40") (pinfunction "VCCIO3_40") (pintype "input"))
      (node (ref "U3") (pin "47") (pinfunction "VCCIO3_47") (pintype "input"))
      (node (ref "U3") (pin "56") (pinfunction "VCCIO4_56") (pintype "input"))
      (node (ref "U3") (pin "62") (pinfunction "VCCIO4_62") (pintype "input"))
      (node (ref "U3") (pin "81") (pinfunction "VCCIO5_81") (pintype "input"))
      (node (ref "U3") (pin "93") (pinfunction "VCCIO6_93") (pintype "input"))
      (node (ref "U7") (pin "13") (pinfunction "VD_13") (pintype "passive"))
      (node (ref "U7") (pin "15") (pinfunction "VDD_15") (pintype "passive"))
      (node (ref "U7") (pin "28") (pinfunction "VDD_28") (pintype "passive"))
      (node (ref "U7") (pin "30") (pinfunction "VD_30") (pintype "passive"))
      (node (ref "U7") (pin "31") (pinfunction "VD_31") (pintype "passive"))
      (node (ref "U7") (pin "33") (pinfunction "VDD_33") (pintype "passive"))
      (node (ref "U7") (pin "46") (pinfunction "VDD_46") (pintype "passive"))
      (node (ref "U7") (pin "48") (pinfunction "VD_48") (pintype "passive"))
      (node (ref "U7") (pin "8") (pinfunction "S1_8") (pintype "unspecified"))
      (node (ref "U7") (pin "9") (pinfunction "S2_9") (pintype "unspecified"))
      (node (ref "U8") (pin "13") (pinfunction "VD_13") (pintype "passive"))
      (node (ref "U8") (pin "15") (pinfunction "VDD_15") (pintype "passive"))
      (node (ref "U8") (pin "28") (pinfunction "VDD_28") (pintype "passive"))
      (node (ref "U8") (pin "30") (pinfunction "VD_30") (pintype "passive"))
      (node (ref "U8") (pin "31") (pinfunction "VD_31") (pintype "passive"))
      (node (ref "U8") (pin "33") (pinfunction "VDD_33") (pintype "passive"))
      (node (ref "U8") (pin "46") (pinfunction "VDD_46") (pintype "passive"))
      (node (ref "U8") (pin "48") (pinfunction "VD_48") (pintype "passive"))
      (node (ref "U8") (pin "8") (pinfunction "S1_8") (pintype "unspecified"))
      (node (ref "U8") (pin "9") (pinfunction "S2_9") (pintype "unspecified"))
    )
    (net (code "7") (name "3V3_CPU") (class "Default")
      (node (ref "C120") (pin "1") (pinfunction "1_1") (pintype "input"))
      (node (ref "C131") (pin "1") (pinfunction "1_1") (pintype "input"))
      (node (ref "C132") (pin "1") (pinfunction "1_1") (pintype "input"))
      (node (ref "C151") (pin "1") (pinfunction "1_1") (pintype "input"))
      (node (ref "D16") (pin "1") (pinfunction "1_1") (pintype "unspecified"))
      (node (ref "R101") (pin "2") (pinfunction "2_2") (pintype "unspecified"))
      (node (ref "R102") (pin "2") (pinfunction "2_2") (pintype "unspecified"))
      (node (ref "R105") (pin "2") (pinfunction "2_2") (pintype "unspecified"))
      (node (ref "R110") (pin "2") (pinfunction "2_2") (pintype "unspecified"))
      (node (ref "R113") (pin "2") (pinfunction "2_2") (pintype "unspecified"))
      (node (ref "R114") (pin "2") (pinfunction "2_2") (pintype "unspecified"))
      (node (ref "R117") (pin "2") (pinfunction "2_2") (pintype "unspecified"))
      (node (ref "R122") (pin "2") (pinfunction "2_2") (pintype "unspecified"))
      (node (ref "R125") (pin "2") (pinfunction "2_2") (pintype "unspecified"))
      (node (ref "R128") (pin "2") (pinfunction "2_2") (pintype "unspecified"))
      (node (ref "R131") (pin "2") (pinfunction "2_2") (pintype "unspecified"))
      (node (ref "R132") (pin "2") (pinfunction "2_2") (pintype "unspecified"))
      (node (ref "R135") (pin "2") (pinfunction "2_2") (pintype "unspecified"))
      (node (ref "R138") (pin "2") (pinfunction "2_2") (pintype "unspecified"))
      (node (ref "R141") (pin "2") (pinfunction "2_2") (pintype "unspecified"))
      (node (ref "R146") (pin "2") (pinfunction "2_2") (pintype "unspecified"))
      (node (ref "R149") (pin "2") (pinfunction "2_2") (pintype "unspecified"))
      (node (ref "R150") (pin "1") (pinfunction "1_1") (pintype "unspecified"))
      (node (ref "R151") (pin "1") (pinfunction "1_1") (pintype "unspecified"))
      (node (ref "R152") (pin "1") (pinfunction "1_1") (pintype "unspecified"))
      (node (ref "R153") (pin "1") (pinfunction "1_1") (pintype "unspecified"))
      (node (ref "R154") (pin "1") (pinfunction "1_1") (pintype "unspecified"))
      (node (ref "R155") (pin "1") (pinfunction "1_1") (pintype "unspecified"))
      (node (ref "R156") (pin "2") (pinfunction "2_2") (pintype "unspecified"))
      (node (ref "R157") (pin "2") (pinfunction "2_2") (pintype "unspecified"))
      (node (ref "R158") (pin "2") (pinfunction "2_2") (pintype "unspecified"))
      (node (ref "R159") (pin "2") (pinfunction "2_2") (pintype "unspecified"))
      (node (ref "R160") (pin "2") (pinfunction "2_2") (pintype "unspecified"))
      (node (ref "R161") (pin "2") (pinfunction "2_2") (pintype "unspecified"))
      (node (ref "U22") (pin "1") (pinfunction "VDD_1") (pintype "unspecified"))
      (node (ref "U22") (pin "24") (pinfunction "VDD_24") (pintype "unspecified"))
      (node (ref "U22") (pin "48") (pinfunction "VDD_48") (pintype "unspecified"))
      (node (ref "U22") (pin "9") (pinfunction "VDDA_9") (pintype "unspecified"))
    )
    (net (code "8") (name "5V") (class "Default")
      (node (ref "C141") (pin "1") (pinfunction "1_1") (pintype "input"))
      (node (ref "C142") (pin "1") (pinfunction "1_1") (pintype "input"))
      (node (ref "C143") (pin "1") (pinfunction "1_1") (pintype "input"))
      (node (ref "C147") (pin "1") (pinfunction "1_1") (pintype "input"))
      (node (ref "C148") (pin "1") (pinfunction "1_1") (pintype "input"))
      (node (ref "C60") (pin "1") (pinfunction "1_1") (pintype "input"))
      (node (ref "C61") (pin "1") (pinfunction "1_1") (pintype "input"))
      (node (ref "C65") (pin "1") (pinfunction "1_1") (pintype "input"))
      (node (ref "C66") (pin "1") (pinfunction "1_1") (pintype "input"))
      (node (ref "C67") (pin "1") (pinfunction "1_1") (pintype "input"))
      (node (ref "C68") (pin "1") (pinfunction "1_1") (pintype "input"))
      (node (ref "C69") (pin "1") (pinfunction "1_1") (pintype "input"))
      (node (ref "C70") (pin "1") (pinfunction "1_1") (pintype "input"))
      (node (ref "C82") (pin "1") (pinfunction "1_1") (pintype "input"))
      (node (ref "L5") (pin "1") (pinfunction "1_1") (pintype "unspecified"))
      (node (ref "Q8") (pin "3") (pinfunction "D_3") (pintype "unspecified"))
      (node (ref "U10") (pin "3") (pinfunction "VIN_3") (pintype "unspecified"))
      (node (ref "U11") (pin "1") (pinfunction "IN_1") (pintype "unspecified"))
      (node (ref "U11") (pin "3") (pinfunction "EN_3") (pintype "unspecified"))
      (node (ref "U14") (pin "5") (pinfunction "+V_5") (pintype "passive"))
      (node (ref "U15") (pin "4") (pinfunction "EN_4") (pintype "unspecified"))
      (node (ref "U15") (pin "5") (pinfunction "VIN_5") (pintype "unspecified"))
      (node (ref "U6") (pin "3") (pinfunction "VIN_3") (pintype "unspecified"))
      (node (ref "U9") (pin "2") (pinfunction "VIN_2") (pintype "unspecified"))
      (node (ref "U9") (pin "4") (pinfunction "VIN_4") (pintype "unspecified"))
    )
    (net (code "9") (name "5V_IN") (class "Default")
      (node (ref "C95") (pin "1") (pinfunction "1_1") (pintype "input"))
      (node (ref "C96") (pin "1") (pinfunction "1_1") (pintype "input"))
      (node (ref "CON1") (pin "1") (pinfunction "1_1") (pintype "bidirectional"))
      (node (ref "L6") (pin "1") (pinfunction "1_1") (pintype "unspecified"))
      (node (ref "Q8") (pin "2") (pinfunction "S_2") (pintype "unspecified"))
      (node (ref "R53") (pin "2") (pinfunction "2_2") (pintype "unspecified"))
      (node (ref "U16") (pin "6") (pinfunction "IN_6") (pintype "unspecified"))
    )
    (net (code "10") (name "10V3") (class "Default")
      (node (ref "C90") (pin "1") (pinfunction "1_1") (pintype "input"))
      (node (ref "C91") (pin "1") (pinfunction "1_1") (pintype "input"))
      (node (ref "P3") (pin "43") (pinfunction "43_43") (pintype "unspecified"))
      (node (ref "R44") (pin "2") (pinfunction "2_2") (pintype "unspecified"))
      (node (ref "ZD1") (pin "2") (pinfunction "A_2") (pintype "unspecified"))
    )
    (net (code "11") (name "15V8") (class "Default")
      (node (ref "C87") (pin "1") (pinfunction "1_1") (pintype "input"))
      (node (ref "C88") (pin "1") (pinfunction "1_1") (pintype "input"))
      (node (ref "D6") (pin "2") (pinfunction "K_2") (pintype "unspecified"))
      (node (ref "P3") (pin "41") (pinfunction "41_41") (pintype "unspecified"))
      (node (ref "R56") (pin "2") (pinfunction "2_2") (pintype "unspecified"))
      (node (ref "ZD1") (pin "1") (pinfunction "K_1") (pintype "unspecified"))
    )
    (net (code "12") (name "ADC1_D0A") (class "Default")
      (node (ref "U3") (pin "103") (pinfunction "(CLKUSR),DIFFIO_R3p,IO_103") (pintype "input"))
      (node (ref "U8") (pin "37") (pinfunction "D0A_37") (pintype "unspecified"))
    )
    (net (code "13") (name "ADC1_D0B") (class "Default")
      (node (ref "U3") (pin "110") (pinfunction "(DQS0T/CQ1T,DPCLK6),DIFFIO_T20p,IO_110") (pintype "input"))
      (node (ref "U8") (pin "24") (pinfunction "D0B_24") (pintype "unspecified"))
    )
    (net (code "14") (name "ADC1_D1A") (class "Default")
      (node (ref "U3") (pin "101") (pinfunction "(nCEO),DIFFIO_R3n,IO_101") (pintype "input"))
      (node (ref "U8") (pin "38") (pinfunction "D1A_38") (pintype "unspecified"))
    )
    (net (code "15") (name "ADC1_D1B") (class "Default")
      (node (ref "U3") (pin "111") (pinfunction "DIFFIO_T19p,IO_111") (pintype "input"))
      (node (ref "U8") (pin "23") (pinfunction "D1B_23") (pintype "unspecified"))
    )
    (net (code "16") (name "ADC1_D2A") (class "Default")
      (node (ref "U3") (pin "100") (pinfunction "IO_100") (pintype "input"))
      (node (ref "U8") (pin "39") (pinfunction "D2A_39") (pintype "unspecified"))
    )
    (net (code "17") (name "ADC1_D2B") (class "Default")
      (node (ref "U3") (pin "112") (pinfunction "PLL2_CLKOUTn,IO_112") (pintype "input"))
      (node (ref "U8") (pin "22") (pinfunction "D2B_22") (pintype "unspecified"))
    )
    (net (code "18") (name "ADC1_D3A") (class "Default")
      (node (ref "U3") (pin "99") (pinfunction "(CRC_ERROR),DIFFIO_R4P,IO_99") (pintype "input"))
      (node (ref "U8") (pin "40") (pinfunction "D3A_40") (pintype "unspecified"))
    )
    (net (code "19") (name "ADC1_D3B") (class "Default")
      (node (ref "U3") (pin "113") (pinfunction "PLL2_CLKOUTp,IO_113") (pintype "input"))
      (node (ref "U8") (pin "21") (pinfunction "D3B_21") (pintype "unspecified"))
    )
    (net (code "20") (name "ADC1_D4A") (class "Default")
      (node (ref "U3") (pin "98") (pinfunction "(INT_DONE),DIFFIO_R4n,IO_98") (pintype "input"))
      (node (ref "U8") (pin "41") (pinfunction "D4A_41") (pintype "unspecified"))
    )
    (net (code "21") (name "ADC1_D4B") (class "Default")
      (node (ref "U3") (pin "114") (pinfunction "(DQ1T),RUP4,IO_114") (pintype "input"))
      (node (ref "U8") (pin "20") (pinfunction "D4B_20") (pintype "unspecified"))
    )
    (net (code "22") (name "ADC1_D5A") (class "Default")
      (node (ref "U3") (pin "91") (pinfunction "CLK4,DIFFCLK_2p_91") (pintype "input"))
      (node (ref "U8") (pin "42") (pinfunction "D5A_42") (pintype "unspecified"))
    )
    (net (code "23") (name "ADC1_D5B") (class "Default")
      (node (ref "U3") (pin "115") (pinfunction "(DQ1T),RDN4,IO_115") (pintype "input"))
      (node (ref "U8") (pin "19") (pinfunction "D5B_19") (pintype "unspecified"))
    )
    (net (code "24") (name "ADC1_D6A") (class "Default")
      (node (ref "U3") (pin "90") (pinfunction "CLK5,DIFFCLK_2n_90") (pintype "input"))
      (node (ref "U8") (pin "43") (pinfunction "D6A_43") (pintype "unspecified"))
    )
    (net (code "25") (name "ADC1_D6B") (class "Default")
      (node (ref "U3") (pin "119") (pinfunction "VREFB7N0,IO_119") (pintype "input"))
      (node (ref "U8") (pin "18") (pinfunction "D6B_18") (pintype "unspecified"))
    )
    (net (code "26") (name "ADC1_D7A") (class "Default")
      (node (ref "U3") (pin "89") (pinfunction "CLK6,DIFFCLK_3p_89") (pintype "input"))
      (node (ref "U8") (pin "44") (pinfunction "D7A_(MSB)_44") (pintype "unspecified"))
    )
    (net (code "27") (name "ADC1_D7B") (class "Default")
      (node (ref "U3") (pin "120") (pinfunction "(DQ1T),DIFFIO_T16n,IO_120") (pintype "input"))
      (node (ref "U8") (pin "17") (pinfunction "D7B_(MSB)_17") (pintype "unspecified"))
    )
    (net (code "28") (name "ADC1_ENCA") (class "Default")
      (node (ref "U3") (pin "88") (pinfunction "CLK7,DIFFCLK_3n_88") (pintype "input"))
      (node (ref "U8") (pin "47") (pinfunction "ENCA_47") (pintype "unspecified"))
    )
    (net (code "29") (name "ADC1_ENCB") (class "Default")
      (node (ref "U3") (pin "121") (pinfunction "DIFFIO_T16p,IO_121") (pintype "input"))
      (node (ref "U8") (pin "14") (pinfunction "ENCB_14") (pintype "unspecified"))
    )
    (net (code "30") (name "ADC1_OFFSET") (class "Default")
      (node (ref "R26") (pin "1") (pinfunction "1_1") (pintype "unspecified"))
      (node (ref "U3") (pin "87") (pinfunction "(DEV_CLRn),DIFFIO_R7p,IO_87") (pintype "input"))
    )
    (net (code "31") (name "ADC2_D0A") (class "Default")
      (node (ref "U3") (pin "72") (pinfunction "DIFFIO_B22p,IO_72") (pintype "input"))
      (node (ref "U7") (pin "37") (pinfunction "D0A_37") (pintype "unspecified"))
    )
    (net (code "32") (name "ADC2_D0B") (class "Default")
      (node (ref "U3") (pin "73") (pinfunction "IO_73") (pintype "input"))
      (node (ref "U7") (pin "24") (pinfunction "D0B_24") (pintype "unspecified"))
    )
    (net (code "33") (name "ADC2_D1A") (class "Default")
      (node (ref "U3") (pin "71") (pinfunction "DIFFIO_B21n,IO_71") (pintype "input"))
      (node (ref "U7") (pin "38") (pinfunction "D1A_38") (pintype "unspecified"))
    )
    (net (code "34") (name "ADC2_D1B") (class "Default")
      (node (ref "U3") (pin "74") (pinfunction "IO_74") (pintype "input"))
      (node (ref "U7") (pin "23") (pinfunction "D1B_23") (pintype "unspecified"))
    )
    (net (code "35") (name "ADC2_D2A") (class "Default")
      (node (ref "U3") (pin "70") (pinfunction "DIFFIO_B21p,IO_70") (pintype "input"))
      (node (ref "U7") (pin "39") (pinfunction "D2A_39") (pintype "unspecified"))
    )
    (net (code "36") (name "ADC2_D2B") (class "Default")
      (node (ref "U3") (pin "75") (pinfunction "IO_75") (pintype "input"))
      (node (ref "U7") (pin "22") (pinfunction "D2B_22") (pintype "unspecified"))
    )
    (net (code "37") (name "ADC2_D3A") (class "Default")
      (node (ref "U3") (pin "69") (pinfunction "IO_69") (pintype "input"))
      (node (ref "U7") (pin "40") (pinfunction "D3A_40") (pintype "unspecified"))
    )
    (net (code "38") (name "ADC2_D3B") (class "Default")
      (node (ref "U3") (pin "76") (pinfunction "RUP3,IO_76") (pintype "input"))
      (node (ref "U7") (pin "21") (pinfunction "D3B_21") (pintype "unspecified"))
    )
    (net (code "39") (name "ADC2_D4A") (class "Default")
      (node (ref "U3") (pin "68") (pinfunction "(DQS0B/CQ1B,DPCLK3),DIFFIO_B20n,IO_68") (pintype "input"))
      (node (ref "U7") (pin "41") (pinfunction "D4A_41") (pintype "unspecified"))
    )
    (net (code "40") (name "ADC2_D4B") (class "Default")
      (node (ref "U3") (pin "77") (pinfunction "RDN3,IO_77") (pintype "input"))
      (node (ref "U7") (pin "20") (pinfunction "D4B_20") (pintype "unspecified"))
    )
    (net (code "41") (name "ADC2_D5A") (class "Default")
      (node (ref "U3") (pin "67") (pinfunction "(DQ1B),RDN2,IO_67") (pintype "input"))
      (node (ref "U7") (pin "42") (pinfunction "D5A_42") (pintype "unspecified"))
    )
    (net (code "42") (name "ADC2_D5B") (class "Default")
      (node (ref "U3") (pin "80") (pinfunction "VREFB5N0,IO_80") (pintype "input"))
      (node (ref "U7") (pin "19") (pinfunction "D5B_19") (pintype "unspecified"))
    )
    (net (code "43") (name "ADC2_D6A") (class "Default")
      (node (ref "U3") (pin "66") (pinfunction "(DQ1B),RUP2,IO_66") (pintype "input"))
      (node (ref "U7") (pin "43") (pinfunction "D6A_43") (pintype "unspecified"))
    )
    (net (code "44") (name "ADC2_D6B") (class "Default")
      (node (ref "U3") (pin "83") (pinfunction "IO_83") (pintype "input"))
      (node (ref "U7") (pin "18") (pinfunction "D6B_18") (pintype "unspecified"))
    )
    (net (code "45") (name "ADC2_D7A") (class "Default")
      (node (ref "U3") (pin "65") (pinfunction "VREFB4N0,IO_65") (pintype "input"))
      (node (ref "U7") (pin "44") (pinfunction "D7A_(MSB)_44") (pintype "unspecified"))
    )
    (net (code "46") (name "ADC2_D7B") (class "Default")
      (node (ref "U3") (pin "84") (pinfunction "DIFFIO_R8n,IO_84") (pintype "input"))
      (node (ref "U7") (pin "17") (pinfunction "D7B_(MSB)_17") (pintype "unspecified"))
    )
    (net (code "47") (name "ADC2_ENCA") (class "Default")
      (node (ref "U3") (pin "64") (pinfunction "IO_64") (pintype "input"))
      (node (ref "U7") (pin "47") (pinfunction "ENCA_47") (pintype "unspecified"))
    )
    (net (code "48") (name "ADC2_ENCB") (class "Default")
      (node (ref "U3") (pin "85") (pinfunction "(DQS1R/CQ1R#,DPCLK4),DIFFIO_R8p,IO_85") (pintype "input"))
      (node (ref "U7") (pin "14") (pinfunction "ENCB_14") (pintype "unspecified"))
    )
    (net (code "49") (name "ADC2_OFFSET") (class "Default")
      (node (ref "R24") (pin "1") (pinfunction "1_1") (pintype "unspecified"))
      (node (ref "U3") (pin "86") (pinfunction "(DEV_OE),DIFFIO_R7n,IO_86") (pintype "input"))
    )
    (net (code "50") (name "ANALOG1_AC_DC") (class "Default")
      (node (ref "R19") (pin "1") (pinfunction "1_1") (pintype "unspecified"))
      (node (ref "U18") (pin "1") (pinfunction "A_1") (pintype "unspecified"))
    )
    (net (code "51") (name "ANALOG1_ADC_INPUT") (class "Default")
      (node (ref "C114") (pin "1") (pinfunction "1_1") (pintype "input"))
      (node (ref "K1") (pin "4") (pinfunction "4_4") (pintype "input"))
      (node (ref "K1") (pin "5") (pinfunction "5_5") (pintype "input"))
      (node (ref "R23") (pin "1") (pinfunction "1_1") (pintype "unspecified"))
      (node (ref "R69") (pin "2") (pinfunction "2_2") (pintype "unspecified"))
      (node (ref "U17") (pin "1") (pinfunction "OUT_1") (pintype "output"))
    )
    (net (code "52") (name "ANALOG1_RELAIS1") (class "Default")
      (node (ref "Q1") (pin "1") (pinfunction "B_1") (pintype "input"))
      (node (ref "R18") (pin "1") (pinfunction "1_1") (pintype "unspecified"))
    )
    (net (code "53") (name "ANALOG1_RELAIS2") (class "Default")
      (node (ref "Q2") (pin "1") (pinfunction "B_1") (pintype "input"))
      (node (ref "R17") (pin "1") (pinfunction "1_1") (pintype "unspecified"))
    )
    (net (code "54") (name "ANALOG1_RELAIS3") (class "Default")
      (node (ref "Q3") (pin "1") (pinfunction "B_1") (pintype "input"))
      (node (ref "R16") (pin "1") (pinfunction "1_1") (pintype "unspecified"))
    )
    (net (code "55") (name "ANALOG2_AC_DC") (class "Default")
      (node (ref "R20") (pin "1") (pinfunction "1_1") (pintype "unspecified"))
      (node (ref "U19") (pin "1") (pinfunction "A_1") (pintype "unspecified"))
    )
    (net (code "56") (name "ANALOG2_ADC_INPUT") (class "Default")
      (node (ref "C118") (pin "1") (pinfunction "1_1") (pintype "input"))
      (node (ref "K6") (pin "4") (pinfunction "4_4") (pintype "input"))
      (node (ref "K6") (pin "5") (pinfunction "5_5") (pintype "input"))
      (node (ref "R22") (pin "1") (pinfunction "1_1") (pintype "unspecified"))
      (node (ref "R73") (pin "2") (pinfunction "2_2") (pintype "unspecified"))
      (node (ref "U20") (pin "1") (pinfunction "OUT_1") (pintype "output"))
    )
    (net (code "57") (name "ANALOG2_RELAIS1") (class "Default")
      (node (ref "Q6") (pin "1") (pinfunction "B_1") (pintype "input"))
      (node (ref "R13") (pin "1") (pinfunction "1_1") (pintype "unspecified"))
    )
    (net (code "58") (name "ANALOG2_RELAIS2") (class "Default")
      (node (ref "Q5") (pin "1") (pinfunction "B_1") (pintype "input"))
      (node (ref "R14") (pin "1") (pinfunction "1_1") (pintype "unspecified"))
    )
    (net (code "59") (name "ANALOG2_RELAIS3") (class "Default")
      (node (ref "Q4") (pin "1") (pinfunction "B_1") (pintype "input"))
      (node (ref "R15") (pin "1") (pinfunction "1_1") (pintype "unspecified"))
    )
    (net (code "60") (name "Backlight V+") (class "Default")
      (node (ref "C97") (pin "1") (pinfunction "1_1") (pintype "input"))
      (node (ref "C98") (pin "1") (pinfunction "1_1") (pintype "input"))
      (node (ref "D10") (pin "2") (pinfunction "K_2") (pintype "unspecified"))
      (node (ref "P3") (pin "1") (pinfunction "1_1") (pintype "unspecified"))
      (node (ref "P3") (pin "2") (pinfunction "2_2") (pintype "unspecified"))
      (node (ref "U16") (pin "5") (pinfunction "OV_5") (pintype "unspecified"))
    )
    (net (code "61") (name "Backlight V-") (class "Default")
      (node (ref "P3") (pin "3") (pinfunction "3_3") (pintype "unspecified"))
      (node (ref "P3") (pin "4") (pinfunction "4_4") (pintype "unspecified"))
      (node (ref "R60") (pin "2") (pinfunction "2_2") (pintype "unspecified"))
      (node (ref "R61") (pin "2") (pinfunction "2_2") (pintype "unspecified"))
      (node (ref "U16") (pin "3") (pinfunction "FB_3") (pintype "unspecified"))
    )
    (net (code "62") (name "CH1_POS_A") (class "Default")
      (node (ref "C155") (pin "1") (pinfunction "1_1") (pintype "input"))
      (node (ref "R111") (pin "2") (pinfunction "2_2") (pintype "unspecified"))
      (node (ref "R112") (pin "1") (pinfunction "1_1") (pintype "unspecified"))
      (node (ref "U22") (pin "14") (pinfunction "PA4_14") (pintype "unspecified"))
    )
    (net (code "63") (name "CH1_POS_B") (class "Default")
      (node (ref "C154") (pin "1") (pinfunction "1_1") (pintype "input"))
      (node (ref "R108") (pin "2") (pinfunction "2_2") (pintype "unspecified"))
      (node (ref "R109") (pin "1") (pinfunction "1_1") (pintype "unspecified"))
      (node (ref "U22") (pin "15") (pinfunction "PA5_15") (pintype "unspecified"))
    )
    (net (code "64") (name "CH1_RNG_A") (class "Default")
      (node (ref "C167") (pin "1") (pinfunction "1_1") (pintype "input"))
      (node (ref "R147") (pin "2") (pinfunction "2_2") (pintype "unspecified"))
      (node (ref "R148") (pin "1") (pinfunction "1_1") (pintype "unspecified"))
      (node (ref "U22") (pin "13") (pinfunction "PA3_13") (pintype "unspecified"))
    )
    (net (code "65") (name "CH1_RNG_B") (class "Default")
      (node (ref "C166") (pin "1") (pinfunction "1_1") (pintype "input"))
      (node (ref "R144") (pin "2") (pinfunction "2_2") (pintype "unspecified"))
      (node (ref "R145") (pin "1") (pinfunction "1_1") (pintype "unspecified"))
      (node (ref "U22") (pin "16") (pinfunction "PA6_16") (pintype "unspecified"))
    )
    (net (code "66") (name "CH2_POS_A") (class "Default")
      (node (ref "C156") (pin "1") (pinfunction "1_1") (pintype "input"))
      (node (ref "R115") (pin "1") (pinfunction "1_1") (pintype "unspecified"))
      (node (ref "R116") (pin "2") (pinfunction "2_2") (pintype "unspecified"))
      (node (ref "U22") (pin "11") (pinfunction "PA1_11") (pintype "unspecified"))
    )
    (net (code "67") (name "CH2_POS_B") (class "Default")
      (node (ref "C157") (pin "1") (pinfunction "1_1") (pintype "input"))
      (node (ref "R118") (pin "1") (pinfunction "1_1") (pintype "unspecified"))
      (node (ref "R119") (pin "2") (pinfunction "2_2") (pintype "unspecified"))
      (node (ref "U22") (pin "10") (pinfunction "PA0_10") (pintype "unspecified"))
    )
    (net (code "68") (name "CH2_RNG_A") (class "Default")
      (node (ref "C164") (pin "1") (pinfunction "1_1") (pintype "input"))
      (node (ref "R139") (pin "1") (pinfunction "1_1") (pintype "unspecified"))
      (node (ref "R140") (pin "2") (pinfunction "2_2") (pintype "unspecified"))
      (node (ref "U22") (pin "6") (pinfunction "PF1-OSCOUT_6") (pintype "unspecified"))
    )
    (net (code "69") (name "CH2_RNG_B") (class "Default")
      (node (ref "C165") (pin "1") (pinfunction "1_1") (pintype "input"))
      (node (ref "R142") (pin "1") (pinfunction "1_1") (pintype "unspecified"))
      (node (ref "R143") (pin "2") (pinfunction "2_2") (pintype "unspecified"))
      (node (ref "U22") (pin "12") (pinfunction "PA2_12") (pintype "unspecified"))
    )
    (net (code "70") (name "CLOCK_SCL") (class "Default")
      (node (ref "R50") (pin "1") (pinfunction "1_1") (pintype "unspecified"))
      (node (ref "U1") (pin "65") (pinfunction "PA1/TPX2/DA_LRCK/UART1_CTS/SPI1_MOSI_65") (pintype "unspecified"))
      (node (ref "U13") (pin "4") (pinfunction "SCL_4") (pintype "unspecified"))
    )
    (net (code "71") (name "CLOCK_SDA") (class "Default")
      (node (ref "R49") (pin "1") (pinfunction "1_1") (pintype "unspecified"))
      (node (ref "U1") (pin "66") (pinfunction "PA0/TPX1/DA_BCLK/UART1_RTS/SPI1_CS_66") (pintype "unspecified"))
      (node (ref "U13") (pin "5") (pinfunction "SDA_5") (pintype "unspecified"))
    )
    (net (code "72") (name "CONTROL_RX") (class "Default")
      (node (ref "U1") (pin "64") (pinfunction "PA2/TPY1/PWM0/DA_IN/UART1_RX/SPI1_CLK_64") (pintype "unspecified"))
      (node (ref "U22") (pin "30") (pinfunction "PA9_30") (pintype "unspecified"))
    )
    (net (code "73") (name "CONTROL_TX") (class "Default")
      (node (ref "U1") (pin "63") (pinfunction "PA3/TPY2/IR_RX/DA_OUT/UART1_TX/SPI1_MISO_63") (pintype "unspecified"))
      (node (ref "U22") (pin "31") (pinfunction "PA10_31") (pintype "unspecified"))
    )
    (net (code "74") (name "DAC_D0") (class "Default")
      (node (ref "R34") (pin "2") (pinfunction "2_2") (pintype "unspecified"))
      (node (ref "U3") (pin "38") (pinfunction "DIFFIO_B1p,IO_38") (pintype "input"))
    )
    (net (code "75") (name "DAC_D1") (class "Default")
      (node (ref "R52") (pin "2") (pinfunction "2_2") (pintype "unspecified"))
      (node (ref "U3") (pin "39") (pinfunction "DIFFIO_B1n,IO_39") (pintype "input"))
    )
    (net (code "76") (name "DAC_D2") (class "Default")
      (node (ref "R55") (pin "2") (pinfunction "2_2") (pintype "unspecified"))
      (node (ref "U3") (pin "42") (pinfunction "(DQS1B/CQ1B#,DPCLK2),IO_42") (pintype "input"))
    )
    (net (code "77") (name "DAC_D3") (class "Default")
      (node (ref "R84") (pin "2") (pinfunction "2_2") (pintype "unspecified"))
      (node (ref "U3") (pin "43") (pinfunction "PLL1_CLKOUTp,IO_43") (pintype "input"))
    )
    (net (code "78") (name "DAC_D4") (class "Default")
      (node (ref "R86") (pin "2") (pinfunction "2_2") (pintype "unspecified"))
      (node (ref "U3") (pin "44") (pinfunction "PLL1_CLKOUTn,IO_44") (pintype "input"))
    )
    (net (code "79") (name "DAC_D5") (class "Default")
      (node (ref "R88") (pin "2") (pinfunction "2_2") (pintype "unspecified"))
      (node (ref "U3") (pin "46") (pinfunction "VREFB3N0,IO_46") (pintype "input"))
    )
    (net (code "80") (name "DAC_D6") (class "Default")
      (node (ref "R90") (pin "2") (pinfunction "2_2") (pintype "unspecified"))
      (node (ref "U3") (pin "49") (pinfunction "(DQ1B),DIFFIO_B9p,IO_49") (pintype "input"))
    )
    (net (code "81") (name "DAC_D7") (class "Default")
      (node (ref "R92") (pin "2") (pinfunction "2_2") (pintype "unspecified"))
      (node (ref "U3") (pin "50") (pinfunction "(DQ1B),DIFFIO_B9n,IO_50") (pintype "input"))
    )
    (net (code "82") (name "F1C100S_FPGA_CLK") (class "Default")
      (node (ref "U1") (pin "41") (pinfunction "PE8/CSI_D5/UART2_RX/SPI1_MOSI_41") (pintype "unspecified"))
      (node (ref "U3") (pin "1") (pinfunction "IO_1") (pintype "input"))
    )
    (net (code "83") (name "F1C100S_FPGA_DB0") (class "Default")
      (node (ref "U1") (pin "49") (pinfunction "PE0/CSI_HSYNC/LCD_D0/TWI2_SCK/UART0_RX_49") (pintype "unspecified"))
      (node (ref "U3") (pin "135") (pinfunction "(DQ1T),DIFFIO_T8n,IO_135") (pintype "input"))
    )
    (net (code "84") (name "F1C100S_FPGA_DB1") (class "Default")
      (node (ref "U1") (pin "48") (pinfunction "PE1/CSI_VSYNC/LCD_D1/TWI2_SDA/UART0_TX_48") (pintype "unspecified"))
      (node (ref "U3") (pin "136") (pinfunction "VREFB8N0,IO_136") (pintype "input"))
    )
    (net (code "85") (name "F1C100S_FPGA_DB2") (class "Default")
      (node (ref "U1") (pin "47") (pinfunction "PE2/CSI_PCLK/LCD_D8/CLK_OUT_47") (pintype "unspecified"))
      (node (ref "U3") (pin "137") (pinfunction "(DQ1T),(DATA5),IO_137") (pintype "input"))
    )
    (net (code "86") (name "F1C100S_FPGA_DB3") (class "Default")
      (node (ref "U1") (pin "46") (pinfunction "PE3/CSI_D0/LCD_D9/DA_BCLK_46") (pintype "unspecified"))
      (node (ref "U3") (pin "138") (pinfunction "(DATA6),IO_138") (pintype "input"))
    )
    (net (code "87") (name "F1C100S_FPGA_DB4") (class "Default")
      (node (ref "U1") (pin "45") (pinfunction "PE4/CSI_D1/LCD_D16/DA_LRCK_45") (pintype "unspecified"))
      (node (ref "U3") (pin "141") (pinfunction "DIFFIO_T5p,IO_141") (pintype "input"))
    )
    (net (code "88") (name "F1C100S_FPGA_DB5") (class "Default")
      (node (ref "U1") (pin "44") (pinfunction "PE5/CSI_D2/LCD_D17/DA_IN_44") (pintype "unspecified"))
      (node (ref "U3") (pin "142") (pinfunction "(DQS1T/CQ1T#,DPCLK7),DIFFIO_T2p,IO_142") (pintype "input"))
    )
    (net (code "89") (name "F1C100S_FPGA_DB6") (class "Default")
      (node (ref "U1") (pin "43") (pinfunction "PE6/CSI_D3/PWM1/DA_OUT/OWA_OUT_43") (pintype "unspecified"))
      (node (ref "U3") (pin "143") (pinfunction "(DQ1T),DIFFIO_T1n,IO_143") (pintype "input"))
    )
    (net (code "90") (name "F1C100S_FPGA_DB7") (class "Default")
      (node (ref "U1") (pin "42") (pinfunction "PE7/CSI_D4/UART2_TX/SPI1_CS_42") (pintype "unspecified"))
      (node (ref "U3") (pin "144") (pinfunction "(DM1T),DIFFIO_T1p,IO_144") (pintype "input"))
    )
    (net (code "91") (name "F1C100S_FPGA_DCS") (class "Default")
      (node (ref "U1") (pin "39") (pinfunction "PE10/CSI_D7/UART2_CTS/SPI1_MISO_39") (pintype "unspecified"))
      (node (ref "U3") (pin "3") (pinfunction "IO_3") (pintype "input"))
    )
    (net (code "92") (name "F1C100S_FPGA_RWS") (class "Default")
      (node (ref "U1") (pin "40") (pinfunction "PE9/CSI_D6/UART2_RTS/SPI1_CLK_40") (pintype "unspecified"))
      (node (ref "U3") (pin "2") (pinfunction "IO_2") (pintype "input"))
    )
    (net (code "93") (name "FPGA_BACKLIGHT_PWM") (class "Default")
      (node (ref "R59") (pin "2") (pinfunction "2_2") (pintype "unspecified"))
      (node (ref "U16") (pin "4") (pinfunction "EN_4") (pintype "unspecified"))
      (node (ref "U3") (pin "7") (pinfunction "VREFB1N0,IO_7") (pintype "input"))
    )
    (net (code "94") (name "FPGA_Conf_ASDO") (class "Default")
      (node (ref "J2") (pin "6") (pinfunction "6_6") (pintype "input"))
      (node (ref "U3") (pin "6") (pinfunction "(DATA1,ASDO),DIFFIO_L1n,IO_6") (pintype "input"))
      (node (ref "U4") (pin "5") (pinfunction "DI_5") (pintype "unspecified"))
    )
    (net (code "95") (name "FPGA_Conf_CLK") (class "Default")
      (node (ref "J2") (pin "5") (pinfunction "5_5") (pintype "input"))
      (node (ref "U3") (pin "12") (pinfunction "DCLK_12") (pintype "input"))
      (node (ref "U4") (pin "6") (pinfunction "CLK_6") (pintype "unspecified"))
    )
    (net (code "96") (name "FPGA_Conf_Data") (class "Default")
      (node (ref "J2") (pin "3") (pinfunction "3_3") (pintype "input"))
      (node (ref "R1") (pin "1") (pinfunction "1_1") (pintype "unspecified"))
      (node (ref "U3") (pin "13") (pinfunction "(DATA0),IO_13") (pintype "input"))
    )
    (net (code "97") (name "FPGA_Conf_nCE") (class "Default")
      (node (ref "J2") (pin "1") (pinfunction "1_1") (pintype "input"))
      (node (ref "U3") (pin "8") (pinfunction "(FLASH_nCE,nCSO),DIFFIO_L2p,IO_8") (pintype "input"))
      (node (ref "U4") (pin "1") (pinfunction "/CS_1") (pintype "unspecified"))
    )
    (net (code "98") (name "FPGA_SPECIAL_IC_SCL") (class "Default")
      (node (ref "J3") (pin "3") (pinfunction "3_3") (pintype "input"))
      (node (ref "R3") (pin "1") (pinfunction "1_1") (pintype "unspecified"))
      (node (ref "U3") (pin "34") (pinfunction "IO_34") (pintype "input"))
      (node (ref "U5") (pin "6") (pinfunction "SCL_6") (pintype "unspecified"))
    )
    (net (code "99") (name "FPGA_SPECIAL_IC_SDA") (class "Default")
      (node (ref "J3") (pin "4") (pinfunction "4_4") (pintype "input"))
      (node (ref "R2") (pin "1") (pinfunction "1_1") (pintype "unspecified"))
      (node (ref "U3") (pin "33") (pinfunction "RDN1,IO_33") (pintype "input"))
      (node (ref "U5") (pin "5") (pinfunction "SDA_5") (pintype "unspecified"))
    )
    (net (code "100") (name "GND") (class "Default")
      (node (ref "C1") (pin "2") (pinfunction "2_2") (pintype "input"))
      (node (ref "C10") (pin "2") (pinfunction "2_2") (pintype "input"))
      (node (ref "C100") (pin "1") (pinfunction "1_1") (pintype "input"))
      (node (ref "C101") (pin "1") (pinfunction "1_1") (pintype "input"))
      (node (ref "C106") (pin "1") (pinfunction "1_1") (pintype "input"))
      (node (ref "C11") (pin "2") (pinfunction "2_2") (pintype "input"))
      (node (ref "C111") (pin "1") (pinfunction "1_1") (pintype "input"))
      (node (ref "C112") (pin "1") (pinfunction "1_1") (pintype "input"))
      (node (ref "C113") (pin "1") (pinfunction "1_1") (pintype "input"))
      (node (ref "C115") (pin "1") (pinfunction "1_1") (pintype "input"))
      (node (ref "C116") (pin "2") (pinfunction "2_2") (pintype "input"))
      (node (ref "C117") (pin "1") (pinfunction "1_1") (pintype "input"))
      (node (ref "C119") (pin "1") (pinfunction "1_1") (pintype "input"))
      (node (ref "C12") (pin "2") (pinfunction "2_2") (pintype "input"))
      (node (ref "C120") (pin "2") (pinfunction "2_2") (pintype "input"))
      (node (ref "C121") (pin "1") (pinfunction "1_1") (pintype "input"))
      (node (ref "C126") (pin "1") (pinfunction "1_1") (pintype "input"))
      (node (ref "C13") (pin "2") (pinfunction "2_2") (pintype "input"))
      (node (ref "C131") (pin "2") (pinfunction "2_2") (pintype "input"))
      (node (ref "C132") (pin "2") (pinfunction "2_2") (pintype "input"))
      (node (ref "C135") (pin "2") (pinfunction "2_2") (pintype "input"))
      (node (ref "C136") (pin "2") (pinfunction "2_2") (pintype "input"))
      (node (ref "C137") (pin "2") (pinfunction "2_2") (pintype "input"))
      (node (ref "C138") (pin "2") (pinfunction "2_2") (pintype "input"))
      (node (ref "C139") (pin "2") (pinfunction "2_2") (pintype "input"))
      (node (ref "C14") (pin "2") (pinfunction "2_2") (pintype "input"))
      (node (ref "C140") (pin "2") (pinfunction "2_2") (pintype "input"))
      (node (ref "C141") (pin "2") (pinfunction "2_2") (pintype "input"))
      (node (ref "C142") (pin "2") (pinfunction "2_2") (pintype "input"))
      (node (ref "C143") (pin "2") (pinfunction "2_2") (pintype "input"))
      (node (ref "C144") (pin "2") (pinfunction "2_2") (pintype "input"))
      (node (ref "C145") (pin "2") (pinfunction "2_2") (pintype "input"))
      (node (ref "C146") (pin "2") (pinfunction "2_2") (pintype "input"))
      (node (ref "C147") (pin "2") (pinfunction "2_2") (pintype "input"))
      (node (ref "C148") (pin "2") (pinfunction "2_2") (pintype "input"))
      (node (ref "C15") (pin "2") (pinfunction "2_2") (pintype "input"))
      (node (ref "C150") (pin "2") (pinfunction "2_2") (pintype "input"))
      (node (ref "C151") (pin "2") (pinfunction "2_2") (pintype "input"))
      (node (ref "C152") (pin "2") (pinfunction "2_2") (pintype "input"))
      (node (ref "C153") (pin "2") (pinfunction "2_2") (pintype "input"))
      (node (ref "C154") (pin "2") (pinfunction "2_2") (pintype "input"))
      (node (ref "C155") (pin "2") (pinfunction "2_2") (pintype "input"))
      (node (ref "C156") (pin "2") (pinfunction "2_2") (pintype "input"))
      (node (ref "C157") (pin "2") (pinfunction "2_2") (pintype "input"))
      (node (ref "C158") (pin "2") (pinfunction "2_2") (pintype "input"))
      (node (ref "C159") (pin "2") (pinfunction "2_2") (pintype "input"))
      (node (ref "C16") (pin "2") (pinfunction "2_2") (pintype "input"))
      (node (ref "C160") (pin "2") (pinfunction "2_2") (pintype "input"))
      (node (ref "C161") (pin "2") (pinfunction "2_2") (pintype "input"))
      (node (ref "C162") (pin "2") (pinfunction "2_2") (pintype "input"))
      (node (ref "C163") (pin "2") (pinfunction "2_2") (pintype "input"))
      (node (ref "C164") (pin "2") (pinfunction "2_2") (pintype "input"))
      (node (ref "C165") (pin "2") (pinfunction "2_2") (pintype "input"))
      (node (ref "C166") (pin "2") (pinfunction "2_2") (pintype "input"))
      (node (ref "C167") (pin "2") (pinfunction "2_2") (pintype "input"))
      (node (ref "C17") (pin "2") (pinfunction "2_2") (pintype "input"))
      (node (ref "C18") (pin "2") (pinfunction "2_2") (pintype "input"))
      (node (ref "C19") (pin "2") (pinfunction "2_2") (pintype "input"))
      (node (ref "C20") (pin "2") (pinfunction "2_2") (pintype "input"))
      (node (ref "C21") (pin "2") (pinfunction "2_2") (pintype "input"))
      (node (ref "C22") (pin "2") (pinfunction "2_2") (pintype "input"))
      (node (ref "C23") (pin "2") (pinfunction "2_2") (pintype "input"))
      (node (ref "C24") (pin "2") (pinfunction "2_2") (pintype "input"))
      (node (ref "C25") (pin "2") (pinfunction "2_2") (pintype "input"))
      (node (ref "C26") (pin "2") (pinfunction "2_2") (pintype "input"))
      (node (ref "C27") (pin "2") (pinfunction "2_2") (pintype "input"))
      (node (ref "C28") (pin "2") (pinfunction "2_2") (pintype "input"))
      (node (ref "C29") (pin "2") (pinfunction "2_2") (pintype "input"))
      (node (ref "C30") (pin "2") (pinfunction "2_2") (pintype "input"))
      (node (ref "C31") (pin "2") (pinfunction "2_2") (pintype "input"))
      (node (ref "C32") (pin "2") (pinfunction "2_2") (pintype "input"))
      (node (ref "C33") (pin "2") (pinfunction "2_2") (pintype "input"))
      (node (ref "C34") (pin "2") (pinfunction "2_2") (pintype "input"))
      (node (ref "C35") (pin "2") (pinfunction "2_2") (pintype "input"))
      (node (ref "C36") (pin "2") (pinfunction "2_2") (pintype "input"))
      (node (ref "C37") (pin "2") (pinfunction "2_2") (pintype "input"))
      (node (ref "C38") (pin "2") (pinfunction "2_2") (pintype "input"))
      (node (ref "C39") (pin "2") (pinfunction "2_2") (pintype "input"))
      (node (ref "C4") (pin "2") (pinfunction "2_2") (pintype "input"))
      (node (ref "C40") (pin "2") (pinfunction "2_2") (pintype "input"))
      (node (ref "C41") (pin "2") (pinfunction "2_2") (pintype "input"))
      (node (ref "C42") (pin "2") (pinfunction "2_2") (pintype "input"))
      (node (ref "C43") (pin "2") (pinfunction "2_2") (pintype "input"))
      (node (ref "C44") (pin "2") (pinfunction "2_2") (pintype "input"))
      (node (ref "C45") (pin "2") (pinfunction "2_2") (pintype "input"))
      (node (ref "C46") (pin "2") (pinfunction "2_2") (pintype "input"))
      (node (ref "C47") (pin "2") (pinfunction "2_2") (pintype "input"))
      (node (ref "C48") (pin "2") (pinfunction "2_2") (pintype "input"))
      (node (ref "C49") (pin "2") (pinfunction "2_2") (pintype "input"))
      (node (ref "C50") (pin "2") (pinfunction "2_2") (pintype "input"))
      (node (ref "C51") (pin "2") (pinfunction "2_2") (pintype "input"))
      (node (ref "C52") (pin "2") (pinfunction "2_2") (pintype "input"))
      (node (ref "C53") (pin "2") (pinfunction "2_2") (pintype "input"))
      (node (ref "C54") (pin "2") (pinfunction "2_2") (pintype "input"))
      (node (ref "C55") (pin "2") (pinfunction "2_2") (pintype "input"))
      (node (ref "C56") (pin "2") (pinfunction "2_2") (pintype "input"))
      (node (ref "C57") (pin "2") (pinfunction "2_2") (pintype "input"))
      (node (ref "C58") (pin "2") (pinfunction "2_2") (pintype "input"))
      (node (ref "C59") (pin "2") (pinfunction "2_2") (pintype "input"))
      (node (ref "C60") (pin "2") (pinfunction "2_2") (pintype "input"))
      (node (ref "C61") (pin "2") (pinfunction "2_2") (pintype "input"))
      (node (ref "C62") (pin "2") (pinfunction "2_2") (pintype "input"))
      (node (ref "C63") (pin "2") (pinfunction "2_2") (pintype "input"))
      (node (ref "C64") (pin "2") (pinfunction "2_2") (pintype "input"))
      (node (ref "C65") (pin "2") (pinfunction "2_2") (pintype "input"))
      (node (ref "C66") (pin "2") (pinfunction "2_2") (pintype "input"))
      (node (ref "C67") (pin "2") (pinfunction "2_2") (pintype "input"))
      (node (ref "C68") (pin "2") (pinfunction "2_2") (pintype "input"))
      (node (ref "C69") (pin "2") (pinfunction "2_2") (pintype "input"))
      (node (ref "C7") (pin "2") (pinfunction "2_2") (pintype "input"))
      (node (ref "C70") (pin "2") (pinfunction "2_2") (pintype "input"))
      (node (ref "C71") (pin "2") (pinfunction "2_2") (pintype "input"))
      (node (ref "C72") (pin "2") (pinfunction "2_2") (pintype "input"))
      (node (ref "C73") (pin "1") (pinfunction "1_1") (pintype "input"))
      (node (ref "C74") (pin "2") (pinfunction "2_2") (pintype "input"))
      (node (ref "C75") (pin "2") (pinfunction "2_2") (pintype "input"))
      (node (ref "C76") (pin "2") (pinfunction "2_2") (pintype "input"))
      (node (ref "C77") (pin "2") (pinfunction "2_2") (pintype "input"))
      (node (ref "C78") (pin "2") (pinfunction "2_2") (pintype "input"))
      (node (ref "C79") (pin "2") (pinfunction "2_2") (pintype "input"))
      (node (ref "C8") (pin "2") (pinfunction "2_2") (pintype "input"))
      (node (ref "C80") (pin "2") (pinfunction "2_2") (pintype "input"))
      (node (ref "C81") (pin "2") (pinfunction "2_2") (pintype "input"))
      (node (ref "C82") (pin "2") (pinfunction "2_2") (pintype "input"))
      (node (ref "C83") (pin "2") (pinfunction "2_2") (pintype "input"))
      (node (ref "C85") (pin "2") (pinfunction "2_2") (pintype "input"))
      (node (ref "C86") (pin "2") (pinfunction "2_2") (pintype "input"))
      (node (ref "C87") (pin "2") (pinfunction "2_2") (pintype "input"))
      (node (ref "C88") (pin "2") (pinfunction "2_2") (pintype "input"))
      (node (ref "C9") (pin "2") (pinfunction "2_2") (pintype "input"))
      (node (ref "C90") (pin "2") (pinfunction "2_2") (pintype "input"))
      (node (ref "C91") (pin "2") (pinfunction "2_2") (pintype "input"))
      (node (ref "C92") (pin "2") (pinfunction "2_2") (pintype "input"))
      (node (ref "C93") (pin "2") (pinfunction "2_2") (pintype "input"))
      (node (ref "C94") (pin "2") (pinfunction "2_2") (pintype "input"))
      (node (ref "C95") (pin "2") (pinfunction "2_2") (pintype "input"))
      (node (ref "C96") (pin "2") (pinfunction "2_2") (pintype "input"))
      (node (ref "C97") (pin "2") (pinfunction "2_2") (pintype "input"))
      (node (ref "C98") (pin "2") (pinfunction "2_2") (pintype "input"))
      (node (ref "CON1") (pin "2") (pinfunction "2_2") (pintype "bidirectional"))
      (node (ref "D11") (pin "2") (pinfunction "2_2") (pintype "unspecified"))
      (node (ref "D15") (pin "2") (pinfunction "2_2") (pintype "unspecified"))
      (node (ref "D8") (pin "2") (pinfunction "K_2") (pintype "unspecified"))
      (node (ref "J1") (pin "2") (pinfunction "2_2") (pintype "input"))
      (node (ref "J2") (pin "2") (pinfunction "2_2") (pintype "input"))
      (node (ref "J3") (pin "1") (pinfunction "1_1") (pintype "input"))
      (node (ref "J5") (pin "10") (pinfunction "10_10") (pintype "unspecified"))
      (node (ref "J5") (pin "2") (pinfunction "2_2") (pintype "unspecified"))
      (node (ref "J6") (pin "2") (pinfunction "2_2") (pintype "input"))
      (node (ref "K1") (pin "8") (pinfunction "8_8") (pintype "input"))
      (node (ref "K2") (pin "8") (pinfunction "8_8") (pintype "input"))
      (node (ref "K3") (pin "8") (pinfunction "8_8") (pintype "input"))
      (node (ref "K4") (pin "8") (pinfunction "8_8") (pintype "input"))
      (node (ref "K5") (pin "8") (pinfunction "8_8") (pintype "input"))
      (node (ref "K6") (pin "8") (pinfunction "8_8") (pintype "input"))
      (node (ref "L2") (pin "1") (pinfunction "1_1") (pintype "unspecified"))
      (node (ref "L3") (pin "1") (pinfunction "1_1") (pintype "unspecified"))
      (node (ref "P2") (pin "10") (pinfunction "BODY_10") (pintype "unspecified"))
      (node (ref "P2") (pin "6") (pinfunction "GND_6") (pintype "unspecified"))
      (node (ref "P2") (pin "9") (pinfunction "CARD_DETECT_9") (pintype "unspecified"))
      (node (ref "P3") (pin "17") (pinfunction "17_17") (pintype "unspecified"))
      (node (ref "P3") (pin "18") (pinfunction "18_18") (pintype "unspecified"))
      (node (ref "P3") (pin "19") (pinfunction "19_19") (pintype "unspecified"))
      (node (ref "P3") (pin "26") (pinfunction "26_26") (pintype "unspecified"))
      (node (ref "P3") (pin "27") (pinfunction "27_27") (pintype "unspecified"))
      (node (ref "P3") (pin "33") (pinfunction "33_33") (pintype "unspecified"))
      (node (ref "P3") (pin "34") (pinfunction "34_34") (pintype "unspecified"))
      (node (ref "P3") (pin "35") (pinfunction "35_35") (pintype "unspecified"))
      (node (ref "P3") (pin "36") (pinfunction "36_36") (pintype "unspecified"))
      (node (ref "P3") (pin "38") (pinfunction "38_38") (pintype "unspecified"))
      (node (ref "P3") (pin "40") (pinfunction "40_40") (pintype "unspecified"))
      (node (ref "P3") (pin "47") (pinfunction "47_47") (pintype "unspecified"))
      (node (ref "P3") (pin "48") (pinfunction "48_48") (pintype "unspecified"))
      (node (ref "P3") (pin "49") (pinfunction "49_49") (pintype "unspecified"))
      (node (ref "P3") (pin "5") (pinfunction "5_5") (pintype "unspecified"))
      (node (ref "P3") (pin "50") (pinfunction "50_50") (pintype "unspecified"))
      (node (ref "P3") (pin "8") (pinfunction "8_8") (pintype "unspecified"))
      (node (ref "Q7") (pin "2") (pinfunction "E_2") (pintype "input"))
      (node (ref "R104") (pin "1") (pinfunction "1_1") (pintype "unspecified"))
      (node (ref "R107") (pin "1") (pinfunction "1_1") (pintype "unspecified"))
      (node (ref "R108") (pin "1") (pinfunction "1_1") (pintype "unspecified"))
      (node (ref "R111") (pin "1") (pinfunction "1_1") (pintype "unspecified"))
      (node (ref "R116") (pin "1") (pinfunction "1_1") (pintype "unspecified"))
      (node (ref "R119") (pin "1") (pinfunction "1_1") (pintype "unspecified"))
      (node (ref "R120") (pin "1") (pinfunction "1_1") (pintype "unspecified"))
      (node (ref "R123") (pin "1") (pinfunction "1_1") (pintype "unspecified"))
      (node (ref "R126") (pin "1") (pinfunction "1_1") (pintype "unspecified"))
      (node (ref "R129") (pin "1") (pinfunction "1_1") (pintype "unspecified"))
      (node (ref "R134") (pin "1") (pinfunction "1_1") (pintype "unspecified"))
      (node (ref "R137") (pin "1") (pinfunction "1_1") (pintype "unspecified"))
      (node (ref "R140") (pin "1") (pinfunction "1_1") (pintype "unspecified"))
      (node (ref "R143") (pin "1") (pinfunction "1_1") (pintype "unspecified"))
      (node (ref "R144") (pin "1") (pinfunction "1_1") (pintype "unspecified"))
      (node (ref "R147") (pin "1") (pinfunction "1_1") (pintype "unspecified"))
      (node (ref "R29") (pin "1") (pinfunction "1_1") (pintype "unspecified"))
      (node (ref "R31") (pin "1") (pinfunction "1_1") (pintype "unspecified"))
      (node (ref "R32") (pin "1") (pinfunction "1_1") (pintype "unspecified"))
      (node (ref "R45") (pin "1") (pinfunction "1_1") (pintype "unspecified"))
      (node (ref "R48") (pin "1") (pinfunction "1_1") (pintype "unspecified"))
      (node (ref "R57") (pin "1") (pinfunction "1_1") (pintype "unspecified"))
      (node (ref "R58") (pin "1") (pinfunction "1_1") (pintype "unspecified"))
      (node (ref "R59") (pin "1") (pinfunction "1_1") (pintype "unspecified"))
      (node (ref "R6") (pin "2") (pinfunction "2_2") (pintype "unspecified"))
      (node (ref "R60") (pin "1") (pinfunction "1_1") (pintype "unspecified"))
      (node (ref "R61") (pin "1") (pinfunction "1_1") (pintype "unspecified"))
      (node (ref "R7") (pin "2") (pinfunction "2_2") (pintype "unspecified"))
      (node (ref "R93") (pin "2") (pinfunction "2_2") (pintype "unspecified"))
      (node (ref "R94") (pin "2") (pinfunction "2_2") (pintype "unspecified"))
      (node (ref "S1") (pin "1") (pinfunction "1_1") (pintype "unspecified"))
      (node (ref "SW1") (pin "2") (pinfunction "C_2") (pintype "input"))
      (node (ref "SW2") (pin "2") (pinfunction "C_2") (pintype "input"))
      (node (ref "SW3") (pin "2") (pinfunction "C_2") (pintype "input"))
      (node (ref "SW4") (pin "2") (pinfunction "C_2") (pintype "input"))
      (node (ref "SW5") (pin "2") (pinfunction "C_2") (pintype "input"))
      (node (ref "SW6") (pin "2") (pinfunction "C_2") (pintype "input"))
      (node (ref "SW7") (pin "2") (pinfunction "C_2") (pintype "input"))
      (node (ref "SW8") (pin "2") (pinfunction "C_2") (pintype "input"))
      (node (ref "U1") (pin "74") (pinfunction "TVGND_74") (pintype "unspecified"))
      (node (ref "U1") (pin "82") (pinfunction "AGND_82") (pintype "unspecified"))
      (node (ref "U1") (pin "89") (pinfunction "GND_89") (pintype "unspecified"))
      (node (ref "U10") (pin "1") (pinfunction "ADJ/GND_1") (pintype "unspecified"))
      (node (ref "U11") (pin "2") (pinfunction "GND_2") (pintype "unspecified"))
      (node (ref "U12") (pin "1") (pinfunction "GND_1") (pintype "passive"))
      (node (ref "U13") (pin "8") (pinfunction "GND_8") (pintype "unspecified"))
      (node (ref "U14") (pin "2") (pinfunction "V-_2") (pintype "passive"))
      (node (ref "U15") (pin "2") (pinfunction "GND_2") (pintype "unspecified"))
      (node (ref "U16") (pin "2") (pinfunction "GND_2") (pintype "unspecified"))
      (node (ref "U17") (pin "2") (pinfunction "V-_2") (pintype "passive"))
      (node (ref "U18") (pin "2") (pinfunction "K_2") (pintype "unspecified"))
      (node (ref "U19") (pin "2") (pinfunction "K_2") (pintype "unspecified"))
      (node (ref "U2") (pin "4") (pinfunction "GND_4") (pintype "unspecified"))
      (node (ref "U20") (pin "2") (pinfunction "V-_2") (pintype "passive"))
      (node (ref "U21") (pin "3") (pinfunction "ANODE_3") (pintype "unspecified"))
      (node (ref "U22") (pin "23") (pinfunction "VSS_23") (pintype "unspecified"))
      (node (ref "U22") (pin "44") (pinfunction "BOOT0_44") (pintype "unspecified"))
      (node (ref "U22") (pin "47") (pinfunction "VSS_47") (pintype "unspecified"))
      (node (ref "U22") (pin "8") (pinfunction "VSSA_8") (pintype "unspecified"))
      (node (ref "U3") (pin "118") (pinfunction "GND_118") (pintype "input"))
      (node (ref "U3") (pin "123") (pinfunction "GND_123") (pintype "input"))
      (node (ref "U3") (pin "131") (pinfunction "GND_131") (pintype "input"))
      (node (ref "U3") (pin "140") (pinfunction "GND_140") (pintype "input"))
      (node (ref "U3") (pin "145") (pinfunction "GND_(PAD)_145") (pintype "input"))
      (node (ref "U3") (pin "19") (pinfunction "GND_19") (pintype "input"))
      (node (ref "U3") (pin "22") (pinfunction "GND_22") (pintype "input"))
      (node (ref "U3") (pin "27") (pinfunction "GND_27") (pintype "input"))
      (node (ref "U3") (pin "4") (pinfunction "GND_4") (pintype "input"))
      (node (ref "U3") (pin "41") (pinfunction "GND_41") (pintype "input"))
      (node (ref "U3") (pin "48") (pinfunction "GND_48") (pintype "input"))
      (node (ref "U3") (pin "57") (pinfunction "GND_57") (pintype "input"))
      (node (ref "U3") (pin "63") (pinfunction "GND_63") (pintype "input"))
      (node (ref "U3") (pin "79") (pinfunction "GND_79") (pintype "input"))
      (node (ref "U3") (pin "82") (pinfunction "GND_82") (pintype "input"))
      (node (ref "U3") (pin "94") (pinfunction "MSEL0_94") (pintype "input"))
      (node (ref "U3") (pin "95") (pinfunction "GND_95") (pintype "input"))
      (node (ref "U3") (pin "97") (pinfunction "MSEL2_97") (pintype "input"))
      (node (ref "U4") (pin "4") (pinfunction "GND_4") (pintype "unspecified"))
      (node (ref "U5") (pin "4") (pinfunction "VSS_4") (pintype "unspecified"))
      (node (ref "U6") (pin "1") (pinfunction "ADJ/GND_1") (pintype "unspecified"))
      (node (ref "U7") (pin "1") (pinfunction "GND_1") (pintype "passive"))
      (node (ref "U7") (pin "12") (pinfunction "GND_12") (pintype "passive"))
      (node (ref "U7") (pin "16") (pinfunction "GND_16") (pintype "passive"))
      (node (ref "U7") (pin "27") (pinfunction "GND_27") (pintype "passive"))
      (node (ref "U7") (pin "29") (pinfunction "GND_29") (pintype "passive"))
      (node (ref "U7") (pin "32") (pinfunction "GND_32") (pintype "passive"))
      (node (ref "U7") (pin "34") (pinfunction "GND_34") (pintype "passive"))
      (node (ref "U7") (pin "4") (pinfunction "DFS_4") (pintype "unspecified"))
      (node (ref "U7") (pin "45") (pinfunction "GND_45") (pintype "passive"))
      (node (ref "U8") (pin "1") (pinfunction "GND_1") (pintype "passive"))
      (node (ref "U8") (pin "12") (pinfunction "GND_12") (pintype "passive"))
      (node (ref "U8") (pin "16") (pinfunction "GND_16") (pintype "passive"))
      (node (ref "U8") (pin "27") (pinfunction "GND_27") (pintype "passive"))
      (node (ref "U8") (pin "29") (pinfunction "GND_29") (pintype "passive"))
      (node (ref "U8") (pin "32") (pinfunction "GND_32") (pintype "passive"))
      (node (ref "U8") (pin "34") (pinfunction "GND_34") (pintype "passive"))
      (node (ref "U8") (pin "4") (pinfunction "DFS_4") (pintype "unspecified"))
      (node (ref "U8") (pin "45") (pinfunction "GND_45") (pintype "passive"))
      (node (ref "U9") (pin "1") (pinfunction "GND_1") (pintype "unspecified"))
      (node (ref "USB1") (pin "4") (pinfunction "GND_4") (pintype "input"))
    )
    (net (code "101") (name "LCD_CLK") (class "Default")
      (node (ref "P3") (pin "37") (pinfunction "37_37") (pintype "unspecified"))
      (node (ref "U1") (pin "26") (pinfunction "PD18/LCD_CLK/SPI0_CS_26") (pintype "unspecified"))
    )
    (net (code "102") (name "LCD_D3") (class "Default")
      (node (ref "P3") (pin "16") (pinfunction "16_16") (pintype "unspecified"))
      (node (ref "U1") (pin "7") (pinfunction "PD1/LCD_D3/UART1_RTS_7") (pintype "unspecified"))
    )
    (net (code "103") (name "LCD_D4") (class "Default")
      (node (ref "P3") (pin "15") (pinfunction "15_15") (pintype "unspecified"))
      (node (ref "U1") (pin "8") (pinfunction "PD2/LCD_D4/UART1_CTS_8") (pintype "unspecified"))
    )
    (net (code "104") (name "LCD_D5") (class "Default")
      (node (ref "P3") (pin "14") (pinfunction "14_14") (pintype "unspecified"))
      (node (ref "U1") (pin "9") (pinfunction "PD3/LCD_D5/UART1_RX_9") (pintype "unspecified"))
    )
    (net (code "105") (name "LCD_D6") (class "Default")
      (node (ref "P3") (pin "13") (pinfunction "13_13") (pintype "unspecified"))
      (node (ref "U1") (pin "10") (pinfunction "PD4/LCD_D6/UART1_TX_10") (pintype "unspecified"))
    )
    (net (code "106") (name "LCD_D7") (class "Default")
      (node (ref "P3") (pin "12") (pinfunction "12_12") (pintype "unspecified"))
      (node (ref "U1") (pin "11") (pinfunction "PD5/LCD_D7/TWI1_SCK_11") (pintype "unspecified"))
    )
    (net (code "107") (name "LCD_D10") (class "Default")
      (node (ref "P3") (pin "25") (pinfunction "25_25") (pintype "unspecified"))
      (node (ref "U1") (pin "12") (pinfunction "PD6/LCD_D10/TWI1_SDA_12") (pintype "unspecified"))
    )
    (net (code "108") (name "LCD_D11") (class "Default")
      (node (ref "P3") (pin "24") (pinfunction "24_24") (pintype "unspecified"))
      (node (ref "U1") (pin "13") (pinfunction "PD7/LCD_D11/DA_MCLK_13") (pintype "unspecified"))
    )
    (net (code "109") (name "LCD_D12") (class "Default")
      (node (ref "P3") (pin "23") (pinfunction "23_23") (pintype "unspecified"))
      (node (ref "U1") (pin "14") (pinfunction "PD8/LCD_D12/DA_BCLK_14") (pintype "unspecified"))
    )
    (net (code "110") (name "LCD_D13") (class "Default")
      (node (ref "P3") (pin "22") (pinfunction "22_22") (pintype "unspecified"))
      (node (ref "U1") (pin "15") (pinfunction "PD9/LCD_D13/DA_LRCK_15") (pintype "unspecified"))
    )
    (net (code "111") (name "LCD_D14") (class "Default")
      (node (ref "P3") (pin "21") (pinfunction "21_21") (pintype "unspecified"))
      (node (ref "U1") (pin "16") (pinfunction "PD10/LCD_D14/DA_IN_16") (pintype "unspecified"))
    )
    (net (code "112") (name "LCD_D15") (class "Default")
      (node (ref "P3") (pin "20") (pinfunction "20_20") (pintype "unspecified"))
      (node (ref "U1") (pin "17") (pinfunction "PD11/LCD_D15/DA_OUT_17") (pintype "unspecified"))
    )
    (net (code "113") (name "LCD_D19") (class "Default")
      (node (ref "P3") (pin "32") (pinfunction "32_32") (pintype "unspecified"))
      (node (ref "U1") (pin "19") (pinfunction "PD13/LCD_D19/UART2_TX_19") (pintype "unspecified"))
    )
    (net (code "114") (name "LCD_D20") (class "Default")
      (node (ref "P3") (pin "31") (pinfunction "31_31") (pintype "unspecified"))
      (node (ref "U1") (pin "21") (pinfunction "PD14/LCD_D20/UART2_RX_21") (pintype "unspecified"))
    )
    (net (code "115") (name "LCD_D21") (class "Default")
      (node (ref "P3") (pin "30") (pinfunction "30_30") (pintype "unspecified"))
      (node (ref "U1") (pin "23") (pinfunction "PD15/LCD_D21/UART2_RST/TWI2_SCK_23") (pintype "unspecified"))
    )
    (net (code "116") (name "LCD_D22") (class "Default")
      (node (ref "P3") (pin "29") (pinfunction "29_29") (pintype "unspecified"))
      (node (ref "U1") (pin "24") (pinfunction "PD16/LCD_D22/UART2_CTS/TWI2_SDA_24") (pintype "unspecified"))
    )
    (net (code "117") (name "LCD_D23") (class "Default")
      (node (ref "P3") (pin "28") (pinfunction "28_28") (pintype "unspecified"))
      (node (ref "U1") (pin "25") (pinfunction "PD17/LCD_D23/OWA_OUT_25") (pintype "unspecified"))
    )
    (net (code "118") (name "LCD_DE") (class "Default")
      (node (ref "P3") (pin "9") (pinfunction "9_9") (pintype "unspecified"))
      (node (ref "U1") (pin "27") (pinfunction "PD19/LCD_DE/SPI0_MOSI_27") (pintype "unspecified"))
    )
    (net (code "119") (name "LCD_HSYNC") (class "Default")
      (node (ref "P3") (pin "11") (pinfunction "11_11") (pintype "unspecified"))
      (node (ref "R43") (pin "1") (pinfunction "1_1") (pintype "unspecified"))
      (node (ref "U1") (pin "28") (pinfunction "PD20/LCD_HSYNC/SPI0_CLK_28") (pintype "unspecified"))
    )
    (net (code "120") (name "LCD_VSYNC") (class "Default")
      (node (ref "P3") (pin "10") (pinfunction "10_10") (pintype "unspecified"))
      (node (ref "R42") (pin "1") (pinfunction "1_1") (pintype "unspecified"))
      (node (ref "U1") (pin "29") (pinfunction "PD21/LCD_VSYNC/SPI0_MISO_29") (pintype "unspecified"))
    )
    (net (code "121") (name "MATRIX_1A") (class "Default")
      (node (ref "R150") (pin "2") (pinfunction "2_2") (pintype "unspecified"))
      (node (ref "S2") (pin "1") (pinfunction "1_1") (pintype "unspecified"))
      (node (ref "S3") (pin "1") (pinfunction "1_1") (pintype "unspecified"))
      (node (ref "S4") (pin "1") (pinfunction "1_1") (pintype "unspecified"))
      (node (ref "S5") (pin "1") (pinfunction "1_1") (pintype "unspecified"))
      (node (ref "S6") (pin "1") (pinfunction "1_1") (pintype "unspecified"))
      (node (ref "S7") (pin "1") (pinfunction "1_1") (pintype "unspecified"))
      (node (ref "U22") (pin "43") (pinfunction "PB7_43") (pintype "unspecified"))
    )
    (net (code "122") (name "MATRIX_1B") (class "Default")
      (node (ref "R156") (pin "1") (pinfunction "1_1") (pintype "unspecified"))
      (node (ref "S13") (pin "2") (pinfunction "2_2") (pintype "unspecified"))
      (node (ref "S19") (pin "2") (pinfunction "2_2") (pintype "unspecified"))
      (node (ref "S2") (pin "2") (pinfunction "2_2") (pintype "unspecified"))
      (node (ref "S25") (pin "2") (pinfunction "2_2") (pintype "unspecified"))
      (node (ref "S31") (pin "2") (pinfunction "2_2") (pintype "unspecified"))
      (node (ref "U22") (pin "17") (pinfunction "PA7_17") (pintype "unspecified"))
    )
    (net (code "123") (name "MATRIX_2A") (class "Default")
      (node (ref "R151") (pin "2") (pinfunction "2_2") (pintype "unspecified"))
      (node (ref "S10") (pin "1") (pinfunction "1_1") (pintype "unspecified"))
      (node (ref "S11") (pin "1") (pinfunction "1_1") (pintype "unspecified"))
      (node (ref "S12") (pin "1") (pinfunction "1_1") (pintype "unspecified"))
      (node (ref "S13") (pin "1") (pinfunction "1_1") (pintype "unspecified"))
      (node (ref "S8") (pin "1") (pinfunction "1_1") (pintype "unspecified"))
      (node (ref "S9") (pin "1") (pinfunction "1_1") (pintype "unspecified"))
      (node (ref "U22") (pin "42") (pinfunction "PB6_42") (pintype "unspecified"))
    )
    (net (code "124") (name "MATRIX_2B") (class "Default")
      (node (ref "R157") (pin "1") (pinfunction "1_1") (pintype "unspecified"))
      (node (ref "S12") (pin "2") (pinfunction "2_2") (pintype "unspecified"))
      (node (ref "S18") (pin "2") (pinfunction "2_2") (pintype "unspecified"))
      (node (ref "S24") (pin "2") (pinfunction "2_2") (pintype "unspecified"))
      (node (ref "S3") (pin "2") (pinfunction "2_2") (pintype "unspecified"))
      (node (ref "S30") (pin "2") (pinfunction "2_2") (pintype "unspecified"))
      (node (ref "U22") (pin "18") (pinfunction "PB0_18") (pintype "unspecified"))
    )
    (net (code "125") (name "MATRIX_3A") (class "Default")
      (node (ref "R152") (pin "2") (pinfunction "2_2") (pintype "unspecified"))
      (node (ref "S14") (pin "1") (pinfunction "1_1") (pintype "unspecified"))
      (node (ref "S15") (pin "1") (pinfunction "1_1") (pintype "unspecified"))
      (node (ref "S16") (pin "1") (pinfunction "1_1") (pintype "unspecified"))
      (node (ref "S17") (pin "1") (pinfunction "1_1") (pintype "unspecified"))
      (node (ref "S18") (pin "1") (pinfunction "1_1") (pintype "unspecified"))
      (node (ref "S19") (pin "1") (pinfunction "1_1") (pintype "unspecified"))
      (node (ref "U22") (pin "41") (pinfunction "PB5_41") (pintype "unspecified"))
    )
    (net (code "126") (name "MATRIX_3B") (class "Default")
      (node (ref "R158") (pin "1") (pinfunction "1_1") (pintype "unspecified"))
      (node (ref "S11") (pin "2") (pinfunction "2_2") (pintype "unspecified"))
      (node (ref "S17") (pin "2") (pinfunction "2_2") (pintype "unspecified"))
      (node (ref "S23") (pin "2") (pinfunction "2_2") (pintype "unspecified"))
      (node (ref "S29") (pin "2") (pinfunction "2_2") (pintype "unspecified"))
      (node (ref "S35") (pin "2") (pinfunction "2_2") (pintype "unspecified"))
      (node (ref "S4") (pin "2") (pinfunction "2_2") (pintype "unspecified"))
      (node (ref "U22") (pin "19") (pinfunction "PB1_19") (pintype "unspecified"))
    )
    (net (code "127") (name "MATRIX_4A") (class "Default")
      (node (ref "R153") (pin "2") (pinfunction "2_2") (pintype "unspecified"))
      (node (ref "S20") (pin "1") (pinfunction "1_1") (pintype "unspecified"))
      (node (ref "S21") (pin "1") (pinfunction "1_1") (pintype "unspecified"))
      (node (ref "S22") (pin "1") (pinfunction "1_1") (pintype "unspecified"))
      (node (ref "S23") (pin "1") (pinfunction "1_1") (pintype "unspecified"))
      (node (ref "S24") (pin "1") (pinfunction "1_1") (pintype "unspecified"))
      (node (ref "S25") (pin "1") (pinfunction "1_1") (pintype "unspecified"))
      (node (ref "U22") (pin "40") (pinfunction "PB4_40") (pintype "unspecified"))
    )
    (net (code "128") (name "MATRIX_4B") (class "Default")
      (node (ref "R159") (pin "1") (pinfunction "1_1") (pintype "unspecified"))
      (node (ref "S10") (pin "2") (pinfunction "2_2") (pintype "unspecified"))
      (node (ref "S16") (pin "2") (pinfunction "2_2") (pintype "unspecified"))
      (node (ref "S22") (pin "2") (pinfunction "2_2") (pintype "unspecified"))
      (node (ref "S28") (pin "2") (pinfunction "2_2") (pintype "unspecified"))
      (node (ref "S34") (pin "2") (pinfunction "2_2") (pintype "unspecified"))
      (node (ref "S5") (pin "2") (pinfunction "2_2") (pintype "unspecified"))
      (node (ref "U22") (pin "20") (pinfunction "PB2_20") (pintype "unspecified"))
    )
    (net (code "129") (name "MATRIX_5A") (class "Default")
      (node (ref "R154") (pin "2") (pinfunction "2_2") (pintype "unspecified"))
      (node (ref "S26") (pin "1") (pinfunction "1_1") (pintype "unspecified"))
      (node (ref "S27") (pin "1") (pinfunction "1_1") (pintype "unspecified"))
      (node (ref "S28") (pin "1") (pinfunction "1_1") (pintype "unspecified"))
      (node (ref "S29") (pin "1") (pinfunction "1_1") (pintype "unspecified"))
      (node (ref "S30") (pin "1") (pinfunction "1_1") (pintype "unspecified"))
      (node (ref "S31") (pin "1") (pinfunction "1_1") (pintype "unspecified"))
      (node (ref "U22") (pin "39") (pinfunction "PB3_39") (pintype "unspecified"))
    )
    (net (code "130") (name "MATRIX_5B") (class "Default")
      (node (ref "R160") (pin "1") (pinfunction "1_1") (pintype "unspecified"))
      (node (ref "S15") (pin "2") (pinfunction "2_2") (pintype "unspecified"))
      (node (ref "S21") (pin "2") (pinfunction "2_2") (pintype "unspecified"))
      (node (ref "S27") (pin "2") (pinfunction "2_2") (pintype "unspecified"))
      (node (ref "S33") (pin "2") (pinfunction "2_2") (pintype "unspecified"))
      (node (ref "S6") (pin "2") (pinfunction "2_2") (pintype "unspecified"))
      (node (ref "S9") (pin "2") (pinfunction "2_2") (pintype "unspecified"))
      (node (ref "U22") (pin "21") (pinfunction "PB10_21") (pintype "unspecified"))
    )
    (net (code "131") (name "MATRIX_6A") (class "Default")
      (node (ref "R155") (pin "2") (pinfunction "2_2") (pintype "unspecified"))
      (node (ref "S32") (pin "1") (pinfunction "1_1") (pintype "unspecified"))
      (node (ref "S33") (pin "1") (pinfunction "1_1") (pintype "unspecified"))
      (node (ref "S34") (pin "1") (pinfunction "1_1") (pintype "unspecified"))
      (node (ref "S35") (pin "1") (pinfunction "1_1") (pintype "unspecified"))
      (node (ref "U22") (pin "38") (pinfunction "PA15_38") (pintype "unspecified"))
    )
    (net (code "132") (name "MATRIX_6B") (class "Default")
      (node (ref "R161") (pin "1") (pinfunction "1_1") (pintype "unspecified"))
      (node (ref "S14") (pin "2") (pinfunction "2_2") (pintype "unspecified"))
      (node (ref "S20") (pin "2") (pinfunction "2_2") (pintype "unspecified"))
      (node (ref "S26") (pin "2") (pinfunction "2_2") (pintype "unspecified"))
      (node (ref "S32") (pin "2") (pinfunction "2_2") (pintype "unspecified"))
      (node (ref "S7") (pin "2") (pinfunction "2_2") (pintype "unspecified"))
      (node (ref "S8") (pin "2") (pinfunction "2_2") (pintype "unspecified"))
      (node (ref "U22") (pin "22") (pinfunction "PB11_22") (pintype "unspecified"))
    )
    (net (code "133") (name "MCU_FLASH_CE") (class "Default")
      (node (ref "J1") (pin "1") (pinfunction "1_1") (pintype "input"))
      (node (ref "R33") (pin "1") (pinfunction "1_1") (pintype "unspecified"))
      (node (ref "U1") (pin "60") (pinfunction "PC1/SPI0_CS/SDC1_CMD_60") (pintype "unspecified"))
      (node (ref "U2") (pin "1") (pinfunction "/CS_1") (pintype "unspecified"))
    )
    (net (code "134") (name "MCU_FLASH_CLK") (class "Default")
      (node (ref "J1") (pin "5") (pinfunction "5_5") (pintype "input"))
      (node (ref "U1") (pin "59") (pinfunction "PC0/SPI0_CLK/SDC1_CLK_59") (pintype "unspecified"))
      (node (ref "U2") (pin "6") (pinfunction "CLK_6") (pintype "unspecified"))
    )
    (net (code "135") (name "MCU_FLASH_MISO") (class "Default")
      (node (ref "J1") (pin "3") (pinfunction "3_3") (pintype "input"))
      (node (ref "U1") (pin "61") (pinfunction "PC2/SPI0_MISO/SDC1_D0_61") (pintype "unspecified"))
      (node (ref "U2") (pin "2") (pinfunction "DO_2") (pintype "unspecified"))
    )
    (net (code "136") (name "MCU_FLASH_MOSI") (class "Default")
      (node (ref "J1") (pin "6") (pinfunction "6_6") (pintype "input"))
      (node (ref "U1") (pin "62") (pinfunction "PC3/SPI0_MOSI/UART0_TX_62") (pintype "unspecified"))
      (node (ref "U2") (pin "5") (pinfunction "DI_5") (pintype "unspecified"))
    )
    (net (code "137") (name "Net-(C25-Pad1)") (class "Default")
      (node (ref "C25") (pin "1") (pinfunction "1_1") (pintype "input"))
      (node (ref "R24") (pin "2") (pinfunction "2_2") (pintype "unspecified"))
      (node (ref "R25") (pin "1") (pinfunction "1_1") (pintype "unspecified"))
    )
    (net (code "138") (name "Net-(C26-Pad1)") (class "Default")
      (node (ref "C26") (pin "1") (pinfunction "1_1") (pintype "input"))
      (node (ref "C27") (pin "1") (pinfunction "1_1") (pintype "input"))
      (node (ref "R25") (pin "2") (pinfunction "2_2") (pintype "unspecified"))
      (node (ref "U7") (pin "10") (pinfunction "AINB_10") (pintype "unspecified"))
      (node (ref "U7") (pin "3") (pinfunction "AINA_3") (pintype "unspecified"))
    )
    (net (code "139") (name "Net-(C28-Pad1)") (class "Default")
      (node (ref "C28") (pin "1") (pinfunction "1_1") (pintype "input"))
      (node (ref "C29") (pin "1") (pinfunction "1_1") (pintype "input"))
      (node (ref "R27") (pin "2") (pinfunction "2_2") (pintype "unspecified"))
      (node (ref "U8") (pin "10") (pinfunction "AINB_10") (pintype "unspecified"))
      (node (ref "U8") (pin "3") (pinfunction "AINA_3") (pintype "unspecified"))
    )
    (net (code "140") (name "Net-(C30-Pad1)") (class "Default")
      (node (ref "C30") (pin "1") (pinfunction "1_1") (pintype "input"))
      (node (ref "R26") (pin "2") (pinfunction "2_2") (pintype "unspecified"))
      (node (ref "R27") (pin "1") (pinfunction "1_1") (pintype "unspecified"))
    )
    (net (code "141") (name "Net-(C59-Pad1)") (class "Default")
      (node (ref "C59") (pin "1") (pinfunction "1_1") (pintype "input"))
      (node (ref "P3") (pin "46") (pinfunction "46_46") (pintype "unspecified"))
      (node (ref "P3") (pin "6") (pinfunction "6_6") (pintype "unspecified"))
      (node (ref "R44") (pin "1") (pinfunction "1_1") (pintype "unspecified"))
      (node (ref "R45") (pin "2") (pinfunction "2_2") (pintype "unspecified"))
    )
    (net (code "142") (name "Net-(C84-Pad1)") (class "Default")
      (node (ref "C84") (pin "1") (pinfunction "1_1") (pintype "input"))
      (node (ref "C85") (pin "1") (pinfunction "1_1") (pintype "input"))
      (node (ref "R82") (pin "2") (pinfunction "2_2") (pintype "unspecified"))
      (node (ref "R97") (pin "1") (pinfunction "1_1") (pintype "unspecified"))
    )
    (net (code "143") (name "Net-(C102-Pad1)") (class "Default")
      (node (ref "C102") (pin "1") (pinfunction "1_1") (pintype "input"))
      (node (ref "C103") (pin "1") (pinfunction "1_1") (pintype "input"))
      (node (ref "C104") (pin "1") (pinfunction "1_1") (pintype "input"))
      (node (ref "C105") (pin "1") (pinfunction "1_1") (pintype "input"))
      (node (ref "R62") (pin "1") (pinfunction "1_1") (pintype "unspecified"))
      (node (ref "R63") (pin "2") (pinfunction "2_2") (pintype "unspecified"))
      (node (ref "R64") (pin "2") (pinfunction "2_2") (pintype "unspecified"))
      (node (ref "R65") (pin "2") (pinfunction "2_2") (pintype "unspecified"))
    )
    (net (code "144") (name "Net-(C102-Pad2)") (class "Default")
      (node (ref "C102") (pin "2") (pinfunction "2_2") (pintype "input"))
      (node (ref "C107") (pin "2") (pinfunction "2_2") (pintype "input"))
      (node (ref "C108") (pin "2") (pinfunction "2_2") (pintype "input"))
      (node (ref "K2") (pin "2") (pinfunction "2_2") (pintype "input"))
      (node (ref "K2") (pin "7") (pinfunction "7_7") (pintype "input"))
      (node (ref "R63") (pin "1") (pinfunction "1_1") (pintype "unspecified"))
      (node (ref "R66") (pin "1") (pinfunction "1_1") (pintype "unspecified"))
    )
    (net (code "145") (name "Net-(C103-Pad2)") (class "Default")
      (node (ref "C103") (pin "2") (pinfunction "2_2") (pintype "input"))
      (node (ref "C109") (pin "2") (pinfunction "2_2") (pintype "input"))
      (node (ref "C110") (pin "2") (pinfunction "2_2") (pintype "input"))
      (node (ref "K2") (pin "4") (pinfunction "4_4") (pintype "input"))
      (node (ref "K2") (pin "5") (pinfunction "5_5") (pintype "input"))
      (node (ref "R64") (pin "1") (pinfunction "1_1") (pintype "unspecified"))
      (node (ref "R67") (pin "1") (pinfunction "1_1") (pintype "unspecified"))
    )
    (net (code "146") (name "Net-(C104-Pad2)") (class "Default")
      (node (ref "C104") (pin "2") (pinfunction "2_2") (pintype "input"))
      (node (ref "C105") (pin "2") (pinfunction "2_2") (pintype "input"))
      (node (ref "K3") (pin "4") (pinfunction "4_4") (pintype "input"))
      (node (ref "K3") (pin "5") (pinfunction "5_5") (pintype "input"))
      (node (ref "R65") (pin "1") (pinfunction "1_1") (pintype "unspecified"))
      (node (ref "R68") (pin "2") (pinfunction "2_2") (pintype "unspecified"))
    )
    (net (code "147") (name "Net-(C116-Pad1)") (class "Default")
      (node (ref "C116") (pin "1") (pinfunction "1_1") (pintype "input"))
      (node (ref "C134") (pin "1") (pinfunction "1_1") (pintype "input"))
      (node (ref "R100") (pin "2") (pinfunction "2_2") (pintype "unspecified"))
      (node (ref "R71") (pin "1") (pinfunction "1_1") (pintype "unspecified"))
    )
    (net (code "148") (name "Net-(C122-Pad2)") (class "Default")
      (node (ref "C122") (pin "2") (pinfunction "2_2") (pintype "input"))
      (node (ref "C123") (pin "2") (pinfunction "2_2") (pintype "input"))
      (node (ref "C129") (pin "2") (pinfunction "2_2") (pintype "input"))
      (node (ref "K5") (pin "4") (pinfunction "4_4") (pintype "input"))
      (node (ref "K5") (pin "5") (pinfunction "5_5") (pintype "input"))
      (node (ref "R75") (pin "1") (pinfunction "1_1") (pintype "unspecified"))
      (node (ref "R78") (pin "1") (pinfunction "1_1") (pintype "unspecified"))
    )
    (net (code "149") (name "Net-(C124-Pad2)") (class "Default")
      (node (ref "C124") (pin "2") (pinfunction "2_2") (pintype "input"))
      (node (ref "C125") (pin "2") (pinfunction "2_2") (pintype "input"))
      (node (ref "C130") (pin "2") (pinfunction "2_2") (pintype "input"))
      (node (ref "K5") (pin "2") (pinfunction "2_2") (pintype "input"))
      (node (ref "K5") (pin "7") (pinfunction "7_7") (pintype "input"))
      (node (ref "R76") (pin "1") (pinfunction "1_1") (pintype "unspecified"))
      (node (ref "R79") (pin "1") (pinfunction "1_1") (pintype "unspecified"))
    )
    (net (code "150") (name "Net-(C127-Pad1)") (class "Default")
      (node (ref "C127") (pin "1") (pinfunction "1_1") (pintype "input"))
      (node (ref "C128") (pin "1") (pinfunction "1_1") (pintype "input"))
      (node (ref "C129") (pin "1") (pinfunction "1_1") (pintype "input"))
      (node (ref "C130") (pin "1") (pinfunction "1_1") (pintype "input"))
      (node (ref "R77") (pin "2") (pinfunction "2_2") (pintype "unspecified"))
      (node (ref "R78") (pin "2") (pinfunction "2_2") (pintype "unspecified"))
      (node (ref "R79") (pin "2") (pinfunction "2_2") (pintype "unspecified"))
      (node (ref "R80") (pin "1") (pinfunction "1_1") (pintype "unspecified"))
    )
    (net (code "151") (name "Net-(C127-Pad2)") (class "Default")
      (node (ref "C127") (pin "2") (pinfunction "2_2") (pintype "input"))
      (node (ref "C128") (pin "2") (pinfunction "2_2") (pintype "input"))
      (node (ref "K4") (pin "4") (pinfunction "4_4") (pintype "input"))
      (node (ref "K4") (pin "5") (pinfunction "5_5") (pintype "input"))
      (node (ref "R74") (pin "2") (pinfunction "2_2") (pintype "unspecified"))
      (node (ref "R77") (pin "1") (pinfunction "1_1") (pintype "unspecified"))
    )
    (net (code "152") (name "Net-(C149-Pad1)") (class "Default")
      (node (ref "C149") (pin "1") (pinfunction "1_1") (pintype "input"))
      (node (ref "C86") (pin "1") (pinfunction "1_1") (pintype "input"))
      (node (ref "R98") (pin "1") (pinfunction "1_1") (pintype "unspecified"))
      (node (ref "R99") (pin "2") (pinfunction "2_2") (pintype "unspecified"))
    )
    (net (code "153") (name "Net-(D4-Pad1)") (class "Default")
      (node (ref "D4") (pin "1") (pinfunction "1_1") (pintype "unspecified"))
      (node (ref "D5") (pin "1") (pinfunction "1_1") (pintype "unspecified"))
      (node (ref "S1") (pin "2") (pinfunction "2_2") (pintype "unspecified"))
    )
    (net (code "154") (name "Net-(D6-A)") (class "Default")
      (node (ref "C89") (pin "2") (pinfunction "2_2") (pintype "input"))
      (node (ref "D6") (pin "1") (pinfunction "A_1") (pintype "unspecified"))
      (node (ref "L5") (pin "2") (pinfunction "2_2") (pintype "unspecified"))
      (node (ref "U15") (pin "1") (pinfunction "SW_1") (pintype "unspecified"))
    )
    (net (code "155") (name "Net-(D7-A)") (class "Default")
      (node (ref "C92") (pin "1") (pinfunction "1_1") (pintype "input"))
      (node (ref "D7") (pin "1") (pinfunction "A_1") (pintype "unspecified"))
      (node (ref "D9") (pin "2") (pinfunction "A_2") (pintype "unspecified"))
    )
    (net (code "156") (name "Net-(D7-K)") (class "Default")
      (node (ref "C89") (pin "1") (pinfunction "1_1") (pintype "input"))
      (node (ref "D7") (pin "2") (pinfunction "K_2") (pintype "unspecified"))
      (node (ref "D8") (pin "1") (pinfunction "A_1") (pintype "unspecified"))
    )
    (net (code "157") (name "Net-(D10-A)") (class "Default")
      (node (ref "D10") (pin "1") (pinfunction "A_1") (pintype "unspecified"))
      (node (ref "L6") (pin "2") (pinfunction "2_2") (pintype "unspecified"))
      (node (ref "U16") (pin "1") (pinfunction "SW_1") (pintype "unspecified"))
    )
    (net (code "158") (name "Net-(D13-Pad2)") (class "Default")
      (node (ref "D13") (pin "2") (pinfunction "2_2") (pintype "unspecified"))
      (node (ref "D4") (pin "2") (pinfunction "2_2") (pintype "unspecified"))
      (node (ref "R46") (pin "2") (pinfunction "2_2") (pintype "unspecified"))
    )
    (net (code "159") (name "Net-(K1-Pad2)") (class "Default")
      (node (ref "K1") (pin "2") (pinfunction "2_2") (pintype "input"))
      (node (ref "K1") (pin "7") (pinfunction "7_7") (pintype "input"))
      (node (ref "R70") (pin "2") (pinfunction "2_2") (pintype "unspecified"))
    )
    (net (code "160") (name "Net-(K2-Pad3)") (class "Default")
      (node (ref "K2") (pin "3") (pinfunction "3_3") (pintype "input"))
      (node (ref "K2") (pin "6") (pinfunction "6_6") (pintype "input"))
      (node (ref "K3") (pin "2") (pinfunction "2_2") (pintype "input"))
      (node (ref "K3") (pin "7") (pinfunction "7_7") (pintype "input"))
    )
    (net (code "161") (name "Net-(K4-Pad2)") (class "Default")
      (node (ref "K4") (pin "2") (pinfunction "2_2") (pintype "input"))
      (node (ref "K4") (pin "7") (pinfunction "7_7") (pintype "input"))
      (node (ref "K5") (pin "3") (pinfunction "3_3") (pintype "input"))
      (node (ref "K5") (pin "6") (pinfunction "6_6") (pintype "input"))
    )
    (net (code "162") (name "Net-(K6-Pad2)") (class "Default")
      (node (ref "K6") (pin "2") (pinfunction "2_2") (pintype "input"))
      (node (ref "K6") (pin "7") (pinfunction "7_7") (pintype "input"))
      (node (ref "R72") (pin "2") (pinfunction "2_2") (pintype "unspecified"))
    )
    (net (code "163") (name "Net-(P2-CD{slash}DAT3)") (class "Default")
      (node (ref "P2") (pin "2") (pinfunction "CD/DAT3_2") (pintype "unspecified"))
      (node (ref "R37") (pin "1") (pinfunction "1_1") (pintype "unspecified"))
      (node (ref "U1") (pin "54") (pinfunction "PF4/SDC0_D3/UART0_TX_54") (pintype "unspecified"))
    )
    (net (code "164") (name "Net-(P2-CLK)") (class "Default")
      (node (ref "P2") (pin "5") (pinfunction "CLK_5") (pintype "unspecified"))
      (node (ref "R39") (pin "1") (pinfunction "1_1") (pintype "unspecified"))
      (node (ref "U1") (pin "56") (pinfunction "PF2/SDC0_CLK/UART0_RX_56") (pintype "unspecified"))
    )
    (net (code "165") (name "Net-(P2-CMD)") (class "Default")
      (node (ref "P2") (pin "3") (pinfunction "CMD_3") (pintype "unspecified"))
      (node (ref "R38") (pin "1") (pinfunction "1_1") (pintype "unspecified"))
      (node (ref "U1") (pin "55") (pinfunction "PF3/SDC0_CMD/DBG_DO_55") (pintype "unspecified"))
    )
    (net (code "166") (name "Net-(P2-DAT0)") (class "Default")
      (node (ref "P2") (pin "7") (pinfunction "DAT0_7") (pintype "unspecified"))
      (node (ref "R40") (pin "1") (pinfunction "1_1") (pintype "unspecified"))
      (node (ref "U1") (pin "57") (pinfunction "PF1/SDC0_D0/DBG_DI_57") (pintype "unspecified"))
    )
    (net (code "167") (name "Net-(P2-DAT1)") (class "Default")
      (node (ref "P2") (pin "8") (pinfunction "DAT1_8") (pintype "unspecified"))
      (node (ref "R41") (pin "1") (pinfunction "1_1") (pintype "unspecified"))
      (node (ref "U1") (pin "58") (pinfunction "PF0/SDC0_D1/DBG_MS/IR_RX_58") (pintype "unspecified"))
    )
    (net (code "168") (name "Net-(P2-DAT2)") (class "Default")
      (node (ref "P2") (pin "1") (pinfunction "DAT2_1") (pintype "unspecified"))
      (node (ref "R36") (pin "1") (pinfunction "1_1") (pintype "unspecified"))
      (node (ref "U1") (pin "53") (pinfunction "PF5/SDC0_D2/DBG_CK/PWM1_53") (pintype "unspecified"))
    )
    (net (code "169") (name "Net-(Q1-C)") (class "Default")
      (node (ref "K1") (pin "1") (pinfunction "1_1") (pintype "input"))
      (node (ref "Q1") (pin "3") (pinfunction "C_3") (pintype "input"))
    )
    (net (code "170") (name "Net-(Q2-C)") (class "Default")
      (node (ref "K2") (pin "1") (pinfunction "1_1") (pintype "input"))
      (node (ref "Q2") (pin "3") (pinfunction "C_3") (pintype "input"))
    )
    (net (code "171") (name "Net-(Q3-C)") (class "Default")
      (node (ref "K3") (pin "1") (pinfunction "1_1") (pintype "input"))
      (node (ref "Q3") (pin "3") (pinfunction "C_3") (pintype "input"))
    )
    (net (code "172") (name "Net-(Q4-C)") (class "Default")
      (node (ref "K4") (pin "1") (pinfunction "1_1") (pintype "input"))
      (node (ref "Q4") (pin "3") (pinfunction "C_3") (pintype "input"))
    )
    (net (code "173") (name "Net-(Q5-C)") (class "Default")
      (node (ref "K5") (pin "1") (pinfunction "1_1") (pintype "input"))
      (node (ref "Q5") (pin "3") (pinfunction "C_3") (pintype "input"))
    )
    (net (code "174") (name "Net-(Q6-C)") (class "Default")
      (node (ref "K6") (pin "1") (pinfunction "1_1") (pintype "input"))
      (node (ref "Q6") (pin "3") (pinfunction "C_3") (pintype "input"))
    )
    (net (code "175") (name "Net-(Q7-B)") (class "Default")
      (node (ref "Q7") (pin "1") (pinfunction "B_1") (pintype "input"))
      (node (ref "R47") (pin "1") (pinfunction "1_1") (pintype "unspecified"))
    )
    (net (code "176") (name "Net-(Q7-C)") (class "Default")
      (node (ref "D13") (pin "1") (pinfunction "1_1") (pintype "unspecified"))
      (node (ref "Q7") (pin "3") (pinfunction "C_3") (pintype "input"))
    )
    (net (code "177") (name "Net-(Q8-G)") (class "Default")
      (node (ref "Q8") (pin "1") (pinfunction "G_1") (pintype "unspecified"))
      (node (ref "R46") (pin "1") (pinfunction "1_1") (pintype "unspecified"))
      (node (ref "R53") (pin "1") (pinfunction "1_1") (pintype "unspecified"))
    )
    (net (code "178") (name "Net-(R14-Pad2)") (class "Default")
      (node (ref "R14") (pin "2") (pinfunction "2_2") (pintype "unspecified"))
      (node (ref "U3") (pin "125") (pinfunction "IO_125") (pintype "input"))
    )
    (net (code "179") (name "Net-(R22-Pad2)") (class "Default")
      (node (ref "R22") (pin "2") (pinfunction "2_2") (pintype "unspecified"))
      (node (ref "U7") (pin "11") (pinfunction "AINB_11") (pintype "unspecified"))
      (node (ref "U7") (pin "2") (pinfunction "AINA_2") (pintype "unspecified"))
    )
    (net (code "180") (name "Net-(R23-Pad2)") (class "Default")
      (node (ref "R23") (pin "2") (pinfunction "2_2") (pintype "unspecified"))
      (node (ref "U8") (pin "11") (pinfunction "AINB_11") (pintype "unspecified"))
      (node (ref "U8") (pin "2") (pinfunction "AINA_2") (pintype "unspecified"))
    )
    (net (code "181") (name "Net-(R35-Pad2)") (class "Default")
      (node (ref "R35") (pin "2") (pinfunction "2_2") (pintype "unspecified"))
      (node (ref "R52") (pin "1") (pinfunction "1_1") (pintype "unspecified"))
      (node (ref "R54") (pin "1") (pinfunction "1_1") (pintype "unspecified"))
    )
    (net (code "182") (name "Net-(R54-Pad2)") (class "Default")
      (node (ref "R54") (pin "2") (pinfunction "2_2") (pintype "unspecified"))
      (node (ref "R55") (pin "1") (pinfunction "1_1") (pintype "unspecified"))
      (node (ref "R83") (pin "1") (pinfunction "1_1") (pintype "unspecified"))
    )
    (net (code "183") (name "Net-(R82-Pad1)") (class "Default")
      (node (ref "R82") (pin "1") (pinfunction "1_1") (pintype "unspecified"))
      (node (ref "RF3") (pin "1") (pinfunction "1_1") (pintype "unspecified"))
      (node (ref "RF3") (pin "2") (pinfunction "2_2") (pintype "unspecified"))
      (node (ref "RF3") (pin "3") (pinfunction "3_3") (pintype "unspecified"))
      (node (ref "RF3") (pin "4") (pinfunction "4_4") (pintype "unspecified"))
    )
    (net (code "184") (name "Net-(R83-Pad2)") (class "Default")
      (node (ref "R83") (pin "2") (pinfunction "2_2") (pintype "unspecified"))
      (node (ref "R84") (pin "1") (pinfunction "1_1") (pintype "unspecified"))
      (node (ref "R85") (pin "1") (pinfunction "1_1") (pintype "unspecified"))
    )
    (net (code "185") (name "Net-(R85-Pad2)") (class "Default")
      (node (ref "R85") (pin "2") (pinfunction "2_2") (pintype "unspecified"))
      (node (ref "R86") (pin "1") (pinfunction "1_1") (pintype "unspecified"))
      (node (ref "R87") (pin "1") (pinfunction "1_1") (pintype "unspecified"))
    )
    (net (code "186") (name "Net-(R87-Pad2)") (class "Default")
      (node (ref "R87") (pin "2") (pinfunction "2_2") (pintype "unspecified"))
      (node (ref "R88") (pin "1") (pinfunction "1_1") (pintype "unspecified"))
      (node (ref "R89") (pin "1") (pinfunction "1_1") (pintype "unspecified"))
    )
    (net (code "187") (name "Net-(R89-Pad2)") (class "Default")
      (node (ref "R89") (pin "2") (pinfunction "2_2") (pintype "unspecified"))
      (node (ref "R90") (pin "1") (pinfunction "1_1") (pintype "unspecified"))
      (node (ref "R91") (pin "1") (pinfunction "1_1") (pintype "unspecified"))
    )
    (net (code "188") (name "Net-(R91-Pad2)") (class "Default")
      (node (ref "R91") (pin "2") (pinfunction "2_2") (pintype "unspecified"))
      (node (ref "R92") (pin "1") (pinfunction "1_1") (pintype "unspecified"))
      (node (ref "R93") (pin "1") (pinfunction "1_1") (pintype "unspecified"))
    )
    (net (code "189") (name "Net-(R96-Pad1)") (class "Default")
      (node (ref "R96") (pin "1") (pinfunction "1_1") (pintype "unspecified"))
      (node (ref "RF3") (pin "5") (pinfunction "5_5") (pintype "unspecified"))
    )
    (net (code "190") (name "Net-(R99-Pad1)") (class "Default")
      (node (ref "R99") (pin "1") (pinfunction "1_1") (pintype "unspecified"))
      (node (ref "RF2") (pin "1") (pinfunction "1_1") (pintype "unspecified"))
      (node (ref "RF2") (pin "2") (pinfunction "2_2") (pintype "unspecified"))
      (node (ref "RF2") (pin "3") (pinfunction "3_3") (pintype "unspecified"))
      (node (ref "RF2") (pin "4") (pinfunction "4_4") (pintype "unspecified"))
    )
    (net (code "191") (name "Net-(R100-Pad1)") (class "Default")
      (node (ref "R100") (pin "1") (pinfunction "1_1") (pintype "unspecified"))
      (node (ref "RF1") (pin "1") (pinfunction "1_1") (pintype "unspecified"))
      (node (ref "RF1") (pin "2") (pinfunction "2_2") (pintype "unspecified"))
      (node (ref "RF1") (pin "3") (pinfunction "3_3") (pintype "unspecified"))
      (node (ref "RF1") (pin "4") (pinfunction "4_4") (pintype "unspecified"))
    )
    (net (code "192") (name "Net-(SW1-A)") (class "Default")
      (node (ref "R102") (pin "1") (pinfunction "1_1") (pintype "unspecified"))
      (node (ref "R103") (pin "2") (pinfunction "2_2") (pintype "unspecified"))
      (node (ref "SW1") (pin "1") (pinfunction "A_1") (pintype "input"))
    )
    (net (code "193") (name "Net-(SW1-B)") (class "Default")
      (node (ref "R105") (pin "1") (pinfunction "1_1") (pintype "unspecified"))
      (node (ref "R106") (pin "2") (pinfunction "2_2") (pintype "unspecified"))
      (node (ref "SW1") (pin "3") (pinfunction "B_3") (pintype "input"))
    )
    (net (code "194") (name "Net-(SW2-A)") (class "Default")
      (node (ref "R112") (pin "2") (pinfunction "2_2") (pintype "unspecified"))
      (node (ref "R113") (pin "1") (pinfunction "1_1") (pintype "unspecified"))
      (node (ref "SW2") (pin "1") (pinfunction "A_1") (pintype "input"))
    )
    (net (code "195") (name "Net-(SW2-B)") (class "Default")
      (node (ref "R109") (pin "2") (pinfunction "2_2") (pintype "unspecified"))
      (node (ref "R110") (pin "1") (pinfunction "1_1") (pintype "unspecified"))
      (node (ref "SW2") (pin "3") (pinfunction "B_3") (pintype "input"))
    )
    (net (code "196") (name "Net-(SW3-A)") (class "Default")
      (node (ref "R114") (pin "1") (pinfunction "1_1") (pintype "unspecified"))
      (node (ref "R115") (pin "2") (pinfunction "2_2") (pintype "unspecified"))
      (node (ref "SW3") (pin "1") (pinfunction "A_1") (pintype "input"))
    )
    (net (code "197") (name "Net-(SW3-B)") (class "Default")
      (node (ref "R117") (pin "1") (pinfunction "1_1") (pintype "unspecified"))
      (node (ref "R118") (pin "2") (pinfunction "2_2") (pintype "unspecified"))
      (node (ref "SW3") (pin "3") (pinfunction "B_3") (pintype "input"))
    )
    (net (code "198") (name "Net-(SW4-A)") (class "Default")
      (node (ref "R124") (pin "2") (pinfunction "2_2") (pintype "unspecified"))
      (node (ref "R125") (pin "1") (pinfunction "1_1") (pintype "unspecified"))
      (node (ref "SW4") (pin "1") (pinfunction "A_1") (pintype "input"))
    )
    (net (code "199") (name "Net-(SW4-B)") (class "Default")
      (node (ref "R121") (pin "2") (pinfunction "2_2") (pintype "unspecified"))
      (node (ref "R122") (pin "1") (pinfunction "1_1") (pintype "unspecified"))
      (node (ref "SW4") (pin "3") (pinfunction "B_3") (pintype "input"))
    )
    (net (code "200") (name "Net-(SW5-A)") (class "Default")
      (node (ref "R130") (pin "2") (pinfunction "2_2") (pintype "unspecified"))
      (node (ref "R131") (pin "1") (pinfunction "1_1") (pintype "unspecified"))
      (node (ref "SW5") (pin "1") (pinfunction "A_1") (pintype "input"))
    )
    (net (code "201") (name "Net-(SW5-B)") (class "Default")
      (node (ref "R127") (pin "2") (pinfunction "2_2") (pintype "unspecified"))
      (node (ref "R128") (pin "1") (pinfunction "1_1") (pintype "unspecified"))
      (node (ref "SW5") (pin "3") (pinfunction "B_3") (pintype "input"))
    )
    (net (code "202") (name "Net-(SW6-A)") (class "Default")
      (node (ref "R132") (pin "1") (pinfunction "1_1") (pintype "unspecified"))
      (node (ref "R133") (pin "2") (pinfunction "2_2") (pintype "unspecified"))
      (node (ref "SW6") (pin "1") (pinfunction "A_1") (pintype "input"))
    )
    (net (code "203") (name "Net-(SW6-B)") (class "Default")
      (node (ref "R135") (pin "1") (pinfunction "1_1") (pintype "unspecified"))
      (node (ref "R136") (pin "2") (pinfunction "2_2") (pintype "unspecified"))
      (node (ref "SW6") (pin "3") (pinfunction "B_3") (pintype "input"))
    )
    (net (code "204") (name "Net-(SW7-A)") (class "Default")
      (node (ref "R138") (pin "1") (pinfunction "1_1") (pintype "unspecified"))
      (node (ref "R139") (pin "2") (pinfunction "2_2") (pintype "unspecified"))
      (node (ref "SW7") (pin "1") (pinfunction "A_1") (pintype "input"))
    )
    (net (code "205") (name "Net-(SW7-B)") (class "Default")
      (node (ref "R141") (pin "1") (pinfunction "1_1") (pintype "unspecified"))
      (node (ref "R142") (pin "2") (pinfunction "2_2") (pintype "unspecified"))
      (node (ref "SW7") (pin "3") (pinfunction "B_3") (pintype "input"))
    )
    (net (code "206") (name "Net-(SW8-A)") (class "Default")
      (node (ref "R148") (pin "2") (pinfunction "2_2") (pintype "unspecified"))
      (node (ref "R149") (pin "1") (pinfunction "1_1") (pintype "unspecified"))
      (node (ref "SW8") (pin "1") (pinfunction "A_1") (pintype "input"))
    )
    (net (code "207") (name "Net-(SW8-B)") (class "Default")
      (node (ref "R145") (pin "2") (pinfunction "2_2") (pintype "unspecified"))
      (node (ref "R146") (pin "1") (pinfunction "1_1") (pintype "unspecified"))
      (node (ref "SW8") (pin "3") (pinfunction "B_3") (pintype "input"))
    )
    (net (code "208") (name "Net-(U1-HOSCI)") (class "Default")
      (node (ref "C32") (pin "1") (pinfunction "1_1") (pintype "input"))
      (node (ref "U1") (pin "51") (pinfunction "HOSCI_51") (pintype "unspecified"))
      (node (ref "X1") (pin "2") (pinfunction "OSC2_2") (pintype "input"))
    )
    (net (code "209") (name "Net-(U1-HOSCO)") (class "Default")
      (node (ref "C31") (pin "1") (pinfunction "1_1") (pintype "input"))
      (node (ref "U1") (pin "52") (pinfunction "HOSCO_52") (pintype "unspecified"))
      (node (ref "X1") (pin "1") (pinfunction "OSC1_1") (pintype "input"))
    )
    (net (code "210") (name "Net-(U1-RESET)") (class "Default")
      (node (ref "J4") (pin "1") (pinfunction "1_1") (pintype "input"))
      (node (ref "R30") (pin "1") (pinfunction "1_1") (pintype "unspecified"))
      (node (ref "U1") (pin "70") (pinfunction "RESET_70") (pintype "unspecified"))
    )
    (net (code "211") (name "Net-(U1-SVREF)") (class "Default")
      (node (ref "C46") (pin "1") (pinfunction "1_1") (pintype "input"))
      (node (ref "R28") (pin "1") (pinfunction "1_1") (pintype "unspecified"))
      (node (ref "R29") (pin "2") (pinfunction "2_2") (pintype "unspecified"))
      (node (ref "U1") (pin "33") (pinfunction "SVREF_33") (pintype "unspecified"))
    )
    (net (code "212") (name "Net-(U1-VRA1)") (class "Default")
      (node (ref "C55") (pin "1") (pinfunction "1_1") (pintype "input"))
      (node (ref "R31") (pin "2") (pinfunction "2_2") (pintype "unspecified"))
      (node (ref "U1") (pin "81") (pinfunction "VRA1_81") (pintype "unspecified"))
    )
    (net (code "213") (name "Net-(U1-VRA2)") (class "Default")
      (node (ref "C56") (pin "1") (pinfunction "1_1") (pintype "input"))
      (node (ref "R32") (pin "2") (pinfunction "2_2") (pintype "unspecified"))
      (node (ref "U1") (pin "83") (pinfunction "VRA2_83") (pintype "unspecified"))
    )
    (net (code "214") (name "Net-(U2-VCC)") (class "Default")
      (node (ref "C136") (pin "1") (pinfunction "1_1") (pintype "input"))
      (node (ref "C57") (pin "1") (pinfunction "1_1") (pintype "input"))
      (node (ref "D3") (pin "1") (pinfunction "1_1") (pintype "unspecified"))
      (node (ref "J1") (pin "4") (pinfunction "4_4") (pintype "input"))
      (node (ref "R33") (pin "2") (pinfunction "2_2") (pintype "unspecified"))
      (node (ref "U2") (pin "3") (pinfunction "/WP_3") (pintype "unspecified"))
      (node (ref "U2") (pin "7") (pinfunction "/HOLD_7") (pintype "unspecified"))
      (node (ref "U2") (pin "8") (pinfunction "VCC_8") (pintype "unspecified"))
    )
    (net (code "215") (name "Net-(U3-(DQ1T),(DATA2),DIFFIO_T10n,IO)") (class "Default")
      (node (ref "R19") (pin "2") (pinfunction "2_2") (pintype "unspecified"))
      (node (ref "U3") (pin "132") (pinfunction "(DQ1T),(DATA2),DIFFIO_T10n,IO_132") (pintype "input"))
    )
    (net (code "216") (name "Net-(U3-(DQ1T),(DATA3),DIFFIO_T10p,IO)") (class "Default")
      (node (ref "R20") (pin "2") (pinfunction "2_2") (pintype "unspecified"))
      (node (ref "U3") (pin "133") (pinfunction "(DQ1T),(DATA3),DIFFIO_T10p,IO_133") (pintype "input"))
    )
    (net (code "217") (name "Net-(U3-CLK1,DIFFCLK_0n)") (class "Default")
      (node (ref "R21") (pin "1") (pinfunction "1_1") (pintype "unspecified"))
      (node (ref "U3") (pin "23") (pinfunction "CLK1,DIFFCLK_0n_23") (pintype "input"))
    )
    (net (code "218") (name "Net-(U3-CLK2,DIFFCLK_1p)") (class "Default")
      (node (ref "R4") (pin "1") (pinfunction "1_1") (pintype "unspecified"))
      (node (ref "U3") (pin "24") (pinfunction "CLK2,DIFFCLK_1p_24") (pintype "input"))
    )
    (net (code "219") (name "Net-(U3-CLK3,DIFFCLK_1n)") (class "Default")
      (node (ref "C13") (pin "1") (pinfunction "1_1") (pintype "input"))
      (node (ref "R5") (pin "1") (pinfunction "1_1") (pintype "unspecified"))
      (node (ref "U3") (pin "25") (pinfunction "CLK3,DIFFCLK_1n_25") (pintype "input"))
    )
    (net (code "220") (name "Net-(U3-CONF_DONE)") (class "Default")
      (node (ref "R12") (pin "2") (pinfunction "2_2") (pintype "unspecified"))
      (node (ref "U3") (pin "92") (pinfunction "CONF_DONE_92") (pintype "input"))
    )
    (net (code "221") (name "Net-(U3-DIFFIO_T11n,IO)") (class "Default")
      (node (ref "R17") (pin "2") (pinfunction "2_2") (pintype "unspecified"))
      (node (ref "U3") (pin "128") (pinfunction "DIFFIO_T11n,IO_128") (pintype "input"))
    )
    (net (code "222") (name "Net-(U3-DIFFIO_T11p,IO)") (class "Default")
      (node (ref "R18") (pin "2") (pinfunction "2_2") (pintype "unspecified"))
      (node (ref "U3") (pin "129") (pinfunction "DIFFIO_T11p,IO_129") (pintype "input"))
    )
    (net (code "223") (name "Net-(U3-DIFFIO_T12n,IO)") (class "Default")
      (node (ref "R15") (pin "2") (pinfunction "2_2") (pintype "unspecified"))
      (node (ref "U3") (pin "126") (pinfunction "DIFFIO_T12n,IO_126") (pintype "input"))
    )
    (net (code "224") (name "Net-(U3-DIFFIO_T12p,IO)") (class "Default")
      (node (ref "R16") (pin "2") (pinfunction "2_2") (pintype "unspecified"))
      (node (ref "U3") (pin "127") (pinfunction "DIFFIO_T12p,IO_127") (pintype "input"))
    )
    (net (code "225") (name "Net-(U3-DIFFIO_T13p,IO)") (class "Default")
      (node (ref "R13") (pin "2") (pinfunction "2_2") (pintype "unspecified"))
      (node (ref "U3") (pin "124") (pinfunction "DIFFIO_T13p,IO_124") (pintype "input"))
    )
    (net (code "226") (name "Net-(U3-GNDA1)") (class "Default")
      (node (ref "C2") (pin "2") (pinfunction "2_2") (pintype "input"))
      (node (ref "C5") (pin "2") (pinfunction "2_2") (pintype "input"))
      (node (ref "L2") (pin "2") (pinfunction "2_2") (pintype "unspecified"))
      (node (ref "U3") (pin "36") (pinfunction "GNDA1_36") (pintype "input"))
    )
    (net (code "227") (name "Net-(U3-GNDA2)") (class "Default")
      (node (ref "C3") (pin "2") (pinfunction "2_2") (pintype "input"))
      (node (ref "C6") (pin "1") (pinfunction "1_1") (pintype "input"))
      (node (ref "L3") (pin "2") (pinfunction "2_2") (pintype "unspecified"))
      (node (ref "U3") (pin "108") (pinfunction "GNDA2_108") (pintype "input"))
    )
    (net (code "228") (name "Net-(U3-TCK)") (class "Default")
      (node (ref "J5") (pin "1") (pinfunction "1_1") (pintype "unspecified"))
      (node (ref "R7") (pin "1") (pinfunction "1_1") (pintype "unspecified"))
      (node (ref "U3") (pin "16") (pinfunction "TCK_16") (pintype "input"))
    )
    (net (code "229") (name "Net-(U3-TDI)") (class "Default")
      (node (ref "J5") (pin "9") (pinfunction "9_9") (pintype "unspecified"))
      (node (ref "R9") (pin "2") (pinfunction "2_2") (pintype "unspecified"))
      (node (ref "U3") (pin "15") (pinfunction "TDI_15") (pintype "input"))
    )
    (net (code "230") (name "Net-(U3-TDO)") (class "Default")
      (node (ref "J5") (pin "3") (pinfunction "3_3") (pintype "unspecified"))
      (node (ref "U3") (pin "20") (pinfunction "TDO_20") (pintype "input"))
    )
    (net (code "231") (name "Net-(U3-TMS)") (class "Default")
      (node (ref "J5") (pin "5") (pinfunction "5_5") (pintype "unspecified"))
      (node (ref "R10") (pin "2") (pinfunction "2_2") (pintype "unspecified"))
      (node (ref "U3") (pin "18") (pinfunction "TMS_18") (pintype "input"))
    )
    (net (code "232") (name "Net-(U3-VCCD_PLL1)") (class "Default")
      (node (ref "C2") (pin "1") (pinfunction "1_1") (pintype "input"))
      (node (ref "L1") (pin "2") (pinfunction "2_2") (pintype "unspecified"))
      (node (ref "U3") (pin "37") (pinfunction "VCCD_PLL1_37") (pintype "input"))
    )
    (net (code "233") (name "Net-(U3-VCCD_PLL2)") (class "Default")
      (node (ref "C3") (pin "1") (pinfunction "1_1") (pintype "input"))
      (node (ref "L4") (pin "2") (pinfunction "2_2") (pintype "unspecified"))
      (node (ref "U3") (pin "109") (pinfunction "VCCD_PLL2_109") (pintype "input"))
    )
    (net (code "234") (name "Net-(U3-nCE)") (class "Default")
      (node (ref "R6") (pin "1") (pinfunction "1_1") (pintype "unspecified"))
      (node (ref "U3") (pin "21") (pinfunction "nCE_21") (pintype "input"))
    )
    (net (code "235") (name "Net-(U3-nCONFIG)") (class "Default")
      (node (ref "R11") (pin "2") (pinfunction "2_2") (pintype "unspecified"))
      (node (ref "U3") (pin "14") (pinfunction "nCONFIG_14") (pintype "input"))
    )
    (net (code "236") (name "Net-(U3-nSTATUS)") (class "Default")
      (node (ref "R8") (pin "2") (pinfunction "2_2") (pintype "unspecified"))
      (node (ref "U3") (pin "9") (pinfunction "nSTATUS_9") (pintype "input"))
    )
    (net (code "237") (name "Net-(U4-DO)") (class "Default")
      (node (ref "R1") (pin "2") (pinfunction "2_2") (pintype "unspecified"))
      (node (ref "U4") (pin "2") (pinfunction "DO_2") (pintype "unspecified"))
    )
    (net (code "238") (name "Net-(U4-VCC)") (class "Default")
      (node (ref "C51") (pin "1") (pinfunction "1_1") (pintype "input"))
      (node (ref "C52") (pin "1") (pinfunction "1_1") (pintype "input"))
      (node (ref "D1") (pin "1") (pinfunction "1_1") (pintype "unspecified"))
      (node (ref "J2") (pin "4") (pinfunction "4_4") (pintype "input"))
      (node (ref "U4") (pin "3") (pinfunction "/WP_3") (pintype "unspecified"))
      (node (ref "U4") (pin "7") (pinfunction "/HOLD_7") (pintype "unspecified"))
      (node (ref "U4") (pin "8") (pinfunction "VCC_8") (pintype "unspecified"))
    )
    (net (code "239") (name "Net-(U5-VCC)") (class "Default")
      (node (ref "C41") (pin "1") (pinfunction "1_1") (pintype "input"))
      (node (ref "C45") (pin "1") (pinfunction "1_1") (pintype "input"))
      (node (ref "D2") (pin "1") (pinfunction "1_1") (pintype "unspecified"))
      (node (ref "J3") (pin "2") (pinfunction "2_2") (pintype "input"))
      (node (ref "R2") (pin "2") (pinfunction "2_2") (pintype "unspecified"))
      (node (ref "R3") (pin "2") (pinfunction "2_2") (pintype "unspecified"))
      (node (ref "U5") (pin "8") (pinfunction "VCC_8") (pintype "unspecified"))
    )
    (net (code "240") (name "Net-(U7-REFINA)") (class "Default")
      (node (ref "C23") (pin "1") (pinfunction "1_1") (pintype "input"))
      (node (ref "U7") (pin "5") (pinfunction "REFINA_5") (pintype "unspecified"))
      (node (ref "U7") (pin "6") (pinfunction "REFOUT_6") (pintype "output"))
      (node (ref "U7") (pin "7") (pinfunction "REFINB_7") (pintype "unspecified"))
    )
    (net (code "241") (name "Net-(U8-REFINA)") (class "Default")
      (node (ref "C24") (pin "1") (pinfunction "1_1") (pintype "input"))
      (node (ref "U8") (pin "5") (pinfunction "REFINA_5") (pintype "unspecified"))
      (node (ref "U8") (pin "6") (pinfunction "REFOUT_6") (pintype "output"))
      (node (ref "U8") (pin "7") (pinfunction "REFINB_7") (pintype "unspecified"))
    )
    (net (code "242") (name "Net-(U13-CLK0)") (class "Default")
      (node (ref "R4") (pin "2") (pinfunction "2_2") (pintype "unspecified"))
      (node (ref "U13") (pin "10") (pinfunction "CLK0_10") (pintype "unspecified"))
    )
    (net (code "243") (name "Net-(U13-CLK1)") (class "Default")
      (node (ref "R21") (pin "2") (pinfunction "2_2") (pintype "unspecified"))
      (node (ref "U13") (pin "9") (pinfunction "CLK1_9") (pintype "unspecified"))
    )
    (net (code "244") (name "Net-(U13-XA)") (class "Default")
      (node (ref "U13") (pin "2") (pinfunction "XA_2") (pintype "unspecified"))
      (node (ref "X2") (pin "2") (pinfunction "OSC2_2") (pintype "input"))
    )
    (net (code "245") (name "Net-(U13-XB)") (class "Default")
      (node (ref "U13") (pin "3") (pinfunction "XB_3") (pintype "unspecified"))
      (node (ref "X2") (pin "1") (pinfunction "OSC1_1") (pintype "input"))
    )
    (net (code "246") (name "Net-(U14-+IN)") (class "Default")
      (node (ref "C81") (pin "1") (pinfunction "1_1") (pintype "input"))
      (node (ref "R34") (pin "1") (pinfunction "1_1") (pintype "unspecified"))
      (node (ref "R35") (pin "1") (pinfunction "1_1") (pintype "unspecified"))
      (node (ref "R94") (pin "1") (pinfunction "1_1") (pintype "unspecified"))
      (node (ref "U14") (pin "3") (pinfunction "+IN_3") (pintype "unspecified"))
    )
    (net (code "247") (name "Net-(U14--IN)") (class "Default")
      (node (ref "D14") (pin "2") (pinfunction "2_2") (pintype "unspecified"))
      (node (ref "D15") (pin "1") (pinfunction "1_1") (pintype "unspecified"))
      (node (ref "R95") (pin "2") (pinfunction "2_2") (pintype "unspecified"))
      (node (ref "R96") (pin "2") (pinfunction "2_2") (pintype "unspecified"))
      (node (ref "U14") (pin "4") (pinfunction "-IN_4") (pintype "unspecified"))
    )
    (net (code "248") (name "Net-(U14-OUT)") (class "Default")
      (node (ref "R95") (pin "1") (pinfunction "1_1") (pintype "unspecified"))
      (node (ref "U14") (pin "1") (pinfunction "OUT_1") (pintype "output"))
    )
    (net (code "249") (name "Net-(U15-FB)") (class "Default")
      (node (ref "R56") (pin "1") (pinfunction "1_1") (pintype "unspecified"))
      (node (ref "R57") (pin "2") (pinfunction "2_2") (pintype "unspecified"))
      (node (ref "U15") (pin "3") (pinfunction "FB_3") (pintype "unspecified"))
    )
    (net (code "250") (name "Net-(U17-+IN)") (class "Default")
      (node (ref "K3") (pin "3") (pinfunction "3_3") (pintype "input"))
      (node (ref "K3") (pin "6") (pinfunction "6_6") (pintype "input"))
      (node (ref "U17") (pin "3") (pinfunction "+IN_3") (pintype "unspecified"))
    )
    (net (code "251") (name "Net-(U17--IN)") (class "Default")
      (node (ref "C114") (pin "2") (pinfunction "2_2") (pintype "input"))
      (node (ref "K1") (pin "3") (pinfunction "3_3") (pintype "input"))
      (node (ref "K1") (pin "6") (pinfunction "6_6") (pintype "input"))
      (node (ref "R69") (pin "1") (pinfunction "1_1") (pintype "unspecified"))
      (node (ref "U17") (pin "4") (pinfunction "-IN_4") (pintype "unspecified"))
    )
    (net (code "252") (name "Net-(U18-S)") (class "Default")
      (node (ref "C99") (pin "2") (pinfunction "2_2") (pintype "input"))
      (node (ref "R62") (pin "2") (pinfunction "2_2") (pintype "unspecified"))
      (node (ref "U18") (pin "4") (pinfunction "S_4") (pintype "unspecified"))
    )
    (net (code "253") (name "Net-(U18-S1)") (class "Default")
      (node (ref "C99") (pin "1") (pinfunction "1_1") (pintype "input"))
      (node (ref "RF1") (pin "5") (pinfunction "5_5") (pintype "unspecified"))
      (node (ref "U18") (pin "3") (pinfunction "S1_3") (pintype "unspecified"))
    )
    (net (code "254") (name "Net-(U19-S)") (class "Default")
      (node (ref "C133") (pin "2") (pinfunction "2_2") (pintype "input"))
      (node (ref "R80") (pin "2") (pinfunction "2_2") (pintype "unspecified"))
      (node (ref "U19") (pin "4") (pinfunction "S_4") (pintype "unspecified"))
    )
    (net (code "255") (name "Net-(U19-S1)") (class "Default")
      (node (ref "C133") (pin "1") (pinfunction "1_1") (pintype "input"))
      (node (ref "RF2") (pin "5") (pinfunction "5_5") (pintype "unspecified"))
      (node (ref "U19") (pin "3") (pinfunction "S1_3") (pintype "unspecified"))
    )
    (net (code "256") (name "Net-(U20-+IN)") (class "Default")
      (node (ref "K4") (pin "3") (pinfunction "3_3") (pintype "input"))
      (node (ref "K4") (pin "6") (pinfunction "6_6") (pintype "input"))
      (node (ref "U20") (pin "3") (pinfunction "+IN_3") (pintype "unspecified"))
    )
    (net (code "257") (name "Net-(U20--IN)") (class "Default")
      (node (ref "C118") (pin "2") (pinfunction "2_2") (pintype "input"))
      (node (ref "K6") (pin "3") (pinfunction "3_3") (pintype "input"))
      (node (ref "K6") (pin "6") (pinfunction "6_6") (pintype "input"))
      (node (ref "R73") (pin "1") (pinfunction "1_1") (pintype "unspecified"))
      (node (ref "U20") (pin "4") (pinfunction "-IN_4") (pintype "unspecified"))
    )
    (net (code "258") (name "Net-(U22-NRST)") (class "Default")
      (node (ref "R101") (pin "1") (pinfunction "1_1") (pintype "unspecified"))
      (node (ref "U22") (pin "7") (pinfunction "NRST_7") (pintype "unspecified"))
    )
    (net (code "259") (name "POWER_HOLD") (class "Default")
      (node (ref "R47") (pin "2") (pinfunction "2_2") (pintype "unspecified"))
      (node (ref "R48") (pin "2") (pinfunction "2_2") (pintype "unspecified"))
      (node (ref "U22") (pin "33") (pinfunction "PA12_33") (pintype "unspecified"))
    )
    (net (code "260") (name "POWER_ON{slash}OFF") (class "Default")
      (node (ref "D5") (pin "2") (pinfunction "2_2") (pintype "unspecified"))
      (node (ref "R51") (pin "2") (pinfunction "2_2") (pintype "unspecified"))
      (node (ref "U22") (pin "32") (pinfunction "PA11_32") (pintype "unspecified"))
    )
    (net (code "261") (name "SELECT_A") (class "Default")
      (node (ref "C152") (pin "1") (pinfunction "1_1") (pintype "input"))
      (node (ref "R103") (pin "1") (pinfunction "1_1") (pintype "unspecified"))
      (node (ref "R104") (pin "2") (pinfunction "2_2") (pintype "unspecified"))
      (node (ref "U22") (pin "26") (pinfunction "PB13_26") (pintype "unspecified"))
    )
    (net (code "262") (name "SELECT_B") (class "Default")
      (node (ref "C153") (pin "1") (pinfunction "1_1") (pintype "input"))
      (node (ref "R106") (pin "1") (pinfunction "1_1") (pintype "unspecified"))
      (node (ref "R107") (pin "2") (pinfunction "2_2") (pintype "unspecified"))
      (node (ref "U22") (pin "25") (pinfunction "PB12_25") (pintype "unspecified"))
    )
    (net (code "263") (name "SWCLK") (class "Default")
      (node (ref "J6") (pin "4") (pinfunction "4_4") (pintype "input"))
      (node (ref "U22") (pin "37") (pinfunction "PA14_37") (pintype "unspecified"))
    )
    (net (code "264") (name "SWDIO") (class "Default")
      (node (ref "J6") (pin "3") (pinfunction "3_3") (pintype "input"))
      (node (ref "U22") (pin "34") (pinfunction "PA13_34") (pintype "unspecified"))
    )
    (net (code "265") (name "TRG_LVL_A") (class "Default")
      (node (ref "C161") (pin "1") (pinfunction "1_1") (pintype "input"))
      (node (ref "R129") (pin "2") (pinfunction "2_2") (pintype "unspecified"))
      (node (ref "R130") (pin "1") (pinfunction "1_1") (pintype "unspecified"))
      (node (ref "U22") (pin "3") (pinfunction "PC14-OSC32IN_3") (pintype "unspecified"))
    )
    (net (code "266") (name "TRG_LVL_B") (class "Default")
      (node (ref "C160") (pin "1") (pinfunction "1_1") (pintype "input"))
      (node (ref "R126") (pin "2") (pinfunction "2_2") (pintype "unspecified"))
      (node (ref "R127") (pin "1") (pinfunction "1_1") (pintype "unspecified"))
      (node (ref "U22") (pin "2") (pinfunction "PC13_2") (pintype "unspecified"))
    )
    (net (code "267") (name "TRG_POS_A") (class "Default")
      (node (ref "C159") (pin "1") (pinfunction "1_1") (pintype "input"))
      (node (ref "R123") (pin "2") (pinfunction "2_2") (pintype "unspecified"))
      (node (ref "R124") (pin "1") (pinfunction "1_1") (pintype "unspecified"))
      (node (ref "U22") (pin "46") (pinfunction "PB9_46") (pintype "unspecified"))
    )
    (net (code "268") (name "TRG_POS_B") (class "Default")
      (node (ref "C158") (pin "1") (pinfunction "1_1") (pintype "input"))
      (node (ref "R120") (pin "2") (pinfunction "2_2") (pintype "unspecified"))
      (node (ref "R121") (pin "1") (pinfunction "1_1") (pintype "unspecified"))
      (node (ref "U22") (pin "45") (pinfunction "PB8_45") (pintype "unspecified"))
    )
    (net (code "269") (name "TRG_RNG\\_A") (class "Default")
      (node (ref "C162") (pin "1") (pinfunction "1_1") (pintype "input"))
      (node (ref "R133") (pin "1") (pinfunction "1_1") (pintype "unspecified"))
      (node (ref "R134") (pin "2") (pinfunction "2_2") (pintype "unspecified"))
      (node (ref "U22") (pin "4") (pinfunction "PC15-OSC32OUT_4") (pintype "unspecified"))
    )
    (net (code "270") (name "TRG_RNG_B") (class "Default")
      (node (ref "C163") (pin "1") (pinfunction "1_1") (pintype "input"))
      (node (ref "R136") (pin "1") (pinfunction "1_1") (pintype "unspecified"))
      (node (ref "R137") (pin "2") (pinfunction "2_2") (pintype "unspecified"))
      (node (ref "U22") (pin "5") (pinfunction "PF0-OSCIN_5") (pintype "unspecified"))
    )
    (net (code "271") (name "USB-DM") (class "Default")
      (node (ref "U1") (pin "68") (pinfunction "USB-DM_68") (pintype "unspecified"))
      (node (ref "USB1") (pin "2") (pinfunction "D-_2") (pintype "input"))
    )
    (net (code "272") (name "USB-DP") (class "Default")
      (node (ref "U1") (pin "69") (pinfunction "USB-DP_69") (pintype "unspecified"))
      (node (ref "USB1") (pin "3") (pinfunction "D+_3") (pintype "input"))
    )
    (net (code "273") (name "VRF1") (class "Default")
      (node (ref "C100") (pin "2") (pinfunction "2_2") (pintype "input"))
      (node (ref "C101") (pin "2") (pinfunction "2_2") (pintype "input"))
      (node (ref "C106") (pin "2") (pinfunction "2_2") (pintype "input"))
      (node (ref "C107") (pin "1") (pinfunction "1_1") (pintype "input"))
      (node (ref "C108") (pin "1") (pinfunction "1_1") (pintype "input"))
      (node (ref "C109") (pin "1") (pinfunction "1_1") (pintype "input"))
      (node (ref "C110") (pin "1") (pinfunction "1_1") (pintype "input"))
      (node (ref "C111") (pin "2") (pinfunction "2_2") (pintype "input"))
      (node (ref "C112") (pin "2") (pinfunction "2_2") (pintype "input"))
      (node (ref "C115") (pin "2") (pinfunction "2_2") (pintype "input"))
      (node (ref "C117") (pin "2") (pinfunction "2_2") (pintype "input"))
      (node (ref "C121") (pin "2") (pinfunction "2_2") (pintype "input"))
      (node (ref "C122") (pin "1") (pinfunction "1_1") (pintype "input"))
      (node (ref "C123") (pin "1") (pinfunction "1_1") (pintype "input"))
      (node (ref "C124") (pin "1") (pinfunction "1_1") (pintype "input"))
      (node (ref "C125") (pin "1") (pinfunction "1_1") (pintype "input"))
      (node (ref "C126") (pin "2") (pinfunction "2_2") (pintype "input"))
      (node (ref "C134") (pin "2") (pinfunction "2_2") (pintype "input"))
      (node (ref "C135") (pin "1") (pinfunction "1_1") (pintype "input"))
      (node (ref "C149") (pin "2") (pinfunction "2_2") (pintype "input"))
      (node (ref "C150") (pin "1") (pinfunction "1_1") (pintype "input"))
      (node (ref "C83") (pin "1") (pinfunction "1_1") (pintype "input"))
      (node (ref "C84") (pin "2") (pinfunction "2_2") (pintype "input"))
      (node (ref "D11") (pin "1") (pinfunction "1_1") (pintype "unspecified"))
      (node (ref "D12") (pin "2") (pinfunction "2_2") (pintype "unspecified"))
      (node (ref "R66") (pin "2") (pinfunction "2_2") (pintype "unspecified"))
      (node (ref "R67") (pin "2") (pinfunction "2_2") (pintype "unspecified"))
      (node (ref "R68") (pin "1") (pinfunction "1_1") (pintype "unspecified"))
      (node (ref "R70") (pin "1") (pinfunction "1_1") (pintype "unspecified"))
      (node (ref "R71") (pin "2") (pinfunction "2_2") (pintype "unspecified"))
      (node (ref "R72") (pin "1") (pinfunction "1_1") (pintype "unspecified"))
      (node (ref "R74") (pin "1") (pinfunction "1_1") (pintype "unspecified"))
      (node (ref "R75") (pin "2") (pinfunction "2_2") (pintype "unspecified"))
      (node (ref "R76") (pin "2") (pinfunction "2_2") (pintype "unspecified"))
      (node (ref "R81") (pin "2") (pinfunction "2_2") (pintype "unspecified"))
      (node (ref "R97") (pin "2") (pinfunction "2_2") (pintype "unspecified"))
      (node (ref "R98") (pin "2") (pinfunction "2_2") (pintype "unspecified"))
      (node (ref "U21") (pin "1") (pinfunction "CATHODE_1") (pintype "unspecified"))
      (node (ref "U21") (pin "2") (pinfunction "REF_2") (pintype "unspecified"))
    )
    (net (code "274") (name "unconnected-(J5-Pad6)") (class "Default")
      (node (ref "J5") (pin "6") (pinfunction "6_6") (pintype "unspecified"))
    )
    (net (code "275") (name "unconnected-(J5-Pad7)") (class "Default")
      (node (ref "J5") (pin "7") (pinfunction "7_7") (pintype "unspecified"))
    )
    (net (code "276") (name "unconnected-(J5-Pad8)") (class "Default")
      (node (ref "J5") (pin "8") (pinfunction "8_8") (pintype "unspecified"))
    )
    (net (code "277") (name "unconnected-(J6-Pad1)") (class "Default")
      (node (ref "J6") (pin "1") (pinfunction "1_1") (pintype "input"))
    )
    (net (code "278") (name "unconnected-(P3-Pad45)") (class "Default")
      (node (ref "P3") (pin "45") (pinfunction "45_45") (pintype "unspecified"))
    )
    (net (code "279") (name "unconnected-(U1-FMINL-Pad84)") (class "Default")
      (node (ref "U1") (pin "84") (pinfunction "FMINL_84") (pintype "unspecified"))
    )
    (net (code "280") (name "unconnected-(U1-FMINR-Pad85)") (class "Default")
      (node (ref "U1") (pin "85") (pinfunction "FMINR_85") (pintype "unspecified"))
    )
    (net (code "281") (name "unconnected-(U1-HPCOM-Pad3)") (class "Default")
      (node (ref "U1") (pin "3") (pinfunction "HPCOM_3") (pintype "unspecified"))
    )
    (net (code "282") (name "unconnected-(U1-HPCOMFB-Pad2)") (class "Default")
      (node (ref "U1") (pin "2") (pinfunction "HPCOMFB_2") (pintype "unspecified"))
    )
    (net (code "283") (name "unconnected-(U1-HPL-Pad1)") (class "Default")
      (node (ref "U1") (pin "1") (pinfunction "HPL_1") (pintype "unspecified"))
    )
    (net (code "284") (name "unconnected-(U1-HPR-Pad88)") (class "Default")
      (node (ref "U1") (pin "88") (pinfunction "HPR_88") (pintype "unspecified"))
    )
    (net (code "285") (name "unconnected-(U1-HPVCC-Pad4)") (class "Default")
      (node (ref "U1") (pin "4") (pinfunction "HPVCC_4") (pintype "unspecified"))
    )
    (net (code "286") (name "unconnected-(U1-LINEIN-Pad86)") (class "Default")
      (node (ref "U1") (pin "86") (pinfunction "LINEIN_86") (pintype "unspecified"))
    )
    (net (code "287") (name "unconnected-(U1-LRADC0-Pad79)") (class "Default")
      (node (ref "U1") (pin "79") (pinfunction "LRADC0_79") (pintype "unspecified"))
    )
    (net (code "288") (name "unconnected-(U1-MICIN-Pad87)") (class "Default")
      (node (ref "U1") (pin "87") (pinfunction "MICIN_87") (pintype "unspecified"))
    )
    (net (code "289") (name "unconnected-(U1-PD0{slash}LCD_D2{slash}TWI0_SDA-Pad6)") (class "Default")
      (node (ref "U1") (pin "6") (pinfunction "PD0/LCD_D2/TWI0_SDA_6") (pintype "unspecified"))
    )
    (net (code "290") (name "unconnected-(U1-PD12{slash}LCD_D18{slash}TWI0_SCK-Pad18)") (class "Default")
      (node (ref "U1") (pin "18") (pinfunction "PD12/LCD_D18/TWI0_SCK_18") (pintype "unspecified"))
    )
    (net (code "291") (name "unconnected-(U1-PE11{slash}CLK_OUT{slash}TWI0_SCK{slash}IR_RX-Pad38)") (class "Default")
      (node (ref "U1") (pin "38") (pinfunction "PE11/CLK_OUT/TWI0_SCK/IR_RX_38") (pintype "unspecified"))
    )
    (net (code "292") (name "unconnected-(U1-PE12{slash}DA_MCLK{slash}TWI0_SDA{slash}PWM0-Pad37)") (class "Default")
      (node (ref "U1") (pin "37") (pinfunction "PE12/DA_MCLK/TWI0_SDA/PWM0_37") (pintype "unspecified"))
    )
    (net (code "293") (name "unconnected-(U1-TVIN0-Pad78)") (class "Default")
      (node (ref "U1") (pin "78") (pinfunction "TVIN0_78") (pintype "unspecified"))
    )
    (net (code "294") (name "unconnected-(U1-TVIN1-Pad77)") (class "Default")
      (node (ref "U1") (pin "77") (pinfunction "TVIN1_77") (pintype "unspecified"))
    )
    (net (code "295") (name "unconnected-(U1-TVOUT-Pad72)") (class "Default")
      (node (ref "U1") (pin "72") (pinfunction "TVOUT_72") (pintype "unspecified"))
    )
    (net (code "296") (name "unconnected-(U1-TV_VCC-Pad73)") (class "Default")
      (node (ref "U1") (pin "73") (pinfunction "TV_VCC_73") (pintype "unspecified"))
    )
    (net (code "297") (name "unconnected-(U1-TV_VRN-Pad75)") (class "Default")
      (node (ref "U1") (pin "75") (pinfunction "TV_VRN_75") (pintype "unspecified"))
    )
    (net (code "298") (name "unconnected-(U1-TV_VRP-Pad76)") (class "Default")
      (node (ref "U1") (pin "76") (pinfunction "TV_VRP_76") (pintype "unspecified"))
    )
    (net (code "299") (name "unconnected-(U3-(DQ1B),DIFFIO_B10p,IO-Pad51)") (class "Default")
      (node (ref "U3") (pin "51") (pinfunction "(DQ1B),DIFFIO_B10p,IO_51") (pintype "input"))
    )
    (net (code "300") (name "unconnected-(U3-(DQ1B),DIFFIO_B15p,IO-Pad58)") (class "Default")
      (node (ref "U3") (pin "58") (pinfunction "(DQ1B),DIFFIO_B15p,IO_58") (pintype "input"))
    )
    (net (code "301") (name "unconnected-(U3-(DQ1B),DIFFIO_B16n,IO-Pad60)") (class "Default")
      (node (ref "U3") (pin "60") (pinfunction "(DQ1B),DIFFIO_B16n,IO_60") (pintype "input"))
    )
    (net (code "302") (name "unconnected-(U3-(DQ1B),DIFFIO_B16p,IO-Pad59)") (class "Default")
      (node (ref "U3") (pin "59") (pinfunction "(DQ1B),DIFFIO_B16p,IO_59") (pintype "input"))
    )
    (net (code "303") (name "unconnected-(U3-(DQS0L{slash}CQ1L,DPCLK0),DIFFIO_L4p,IO-Pad10)") (class "Default")
      (node (ref "U3") (pin "10") (pinfunction "(DQS0L/CQ1L,DPCLK0),DIFFIO_L4p,IO_10") (pintype "input"))
    )
    (net (code "304") (name "unconnected-(U3-(DQS0R{slash}CQ1R,DPCLK5),IO-Pad104)") (class "Default")
      (node (ref "U3") (pin "104") (pinfunction "(DQS0R/CQ1R,DPCLK5),IO_104") (pintype "input"))
    )
    (net (code "305") (name "unconnected-(U3-(DQS1L{slash}CQ1L#,DPCLK1),DIFFIO_L8p,IO-Pad30)") (class "Default")
      (node (ref "U3") (pin "30") (pinfunction "(DQS1L/CQ1L#,DPCLK1),DIFFIO_L8p,IO_30") (pintype "input"))
    )
    (net (code "306") (name "unconnected-(U3-DIFFIO_B11n,IO-Pad53)") (class "Default")
      (node (ref "U3") (pin "53") (pinfunction "DIFFIO_B11n,IO_53") (pintype "input"))
    )
    (net (code "307") (name "unconnected-(U3-DIFFIO_B11p,IO-Pad52)") (class "Default")
      (node (ref "U3") (pin "52") (pinfunction "DIFFIO_B11p,IO_52") (pintype "input"))
    )
    (net (code "308") (name "unconnected-(U3-DIFFIO_B12n,IO-Pad55)") (class "Default")
      (node (ref "U3") (pin "55") (pinfunction "DIFFIO_B12n,IO_55") (pintype "input"))
    )
    (net (code "309") (name "unconnected-(U3-DIFFIO_B12p,IO-Pad54)") (class "Default")
      (node (ref "U3") (pin "54") (pinfunction "DIFFIO_B12p,IO_54") (pintype "input"))
    )
    (net (code "310") (name "unconnected-(U3-DIFFIO_L4n,IO-Pad11)") (class "Default")
      (node (ref "U3") (pin "11") (pinfunction "DIFFIO_L4n,IO_11") (pintype "input"))
    )
    (net (code "311") (name "unconnected-(U3-DIFFIO_L6n,IO-Pad28)") (class "Default")
      (node (ref "U3") (pin "28") (pinfunction "DIFFIO_L6n,IO_28") (pintype "input"))
    )
    (net (code "312") (name "unconnected-(U3-DIFFIO_R1n,IO-Pad106)") (class "Default")
      (node (ref "U3") (pin "106") (pinfunction "DIFFIO_R1n,IO_106") (pintype "input"))
    )
    (net (code "313") (name "unconnected-(U3-RUP1,IO-Pad32)") (class "Default")
      (node (ref "U3") (pin "32") (pinfunction "RUP1,IO_32") (pintype "input"))
    )
    (net (code "314") (name "unconnected-(U3-VERFB6N0,IO-Pad105)") (class "Default")
      (node (ref "U3") (pin "105") (pinfunction "VERFB6N0,IO_105") (pintype "input"))
    )
    (net (code "315") (name "unconnected-(U3-VREFB2N0,IO-Pad31)") (class "Default")
      (node (ref "U3") (pin "31") (pinfunction "VREFB2N0,IO_31") (pintype "input"))
    )
    (net (code "316") (name "unconnected-(U5-A0-Pad1)") (class "Default")
      (node (ref "U5") (pin "1") (pinfunction "A0_1") (pintype "unspecified"))
    )
    (net (code "317") (name "unconnected-(U5-A1-Pad2)") (class "Default")
      (node (ref "U5") (pin "2") (pinfunction "A1_2") (pintype "unspecified"))
    )
    (net (code "318") (name "unconnected-(U5-A2-Pad3)") (class "Default")
      (node (ref "U5") (pin "3") (pinfunction "A2_3") (pintype "unspecified"))
    )
    (net (code "319") (name "unconnected-(U5-WP-Pad7)") (class "Default")
      (node (ref "U5") (pin "7") (pinfunction "WP_7") (pintype "unspecified"))
    )
    (net (code "320") (name "unconnected-(U7-NC-Pad25)") (class "Default")
      (node (ref "U7") (pin "25") (pinfunction "NC_25") (pintype "unspecified"))
    )
    (net (code "321") (name "unconnected-(U7-NC-Pad26)") (class "Default")
      (node (ref "U7") (pin "26") (pinfunction "NC_26") (pintype "unspecified"))
    )
    (net (code "322") (name "unconnected-(U7-NC-Pad35)") (class "Default")
      (node (ref "U7") (pin "35") (pinfunction "NC_35") (pintype "unspecified"))
    )
    (net (code "323") (name "unconnected-(U7-NC-Pad36)") (class "Default")
      (node (ref "U7") (pin "36") (pinfunction "NC_36") (pintype "unspecified"))
    )
    (net (code "324") (name "unconnected-(U8-NC-Pad25)") (class "Default")
      (node (ref "U8") (pin "25") (pinfunction "NC_25") (pintype "unspecified"))
    )
    (net (code "325") (name "unconnected-(U8-NC-Pad26)") (class "Default")
      (node (ref "U8") (pin "26") (pinfunction "NC_26") (pintype "unspecified"))
    )
    (net (code "326") (name "unconnected-(U8-NC-Pad35)") (class "Default")
      (node (ref "U8") (pin "35") (pinfunction "NC_35") (pintype "unspecified"))
    )
    (net (code "327") (name "unconnected-(U8-NC-Pad36)") (class "Default")
      (node (ref "U8") (pin "36") (pinfunction "NC_36") (pintype "unspecified"))
    )
    (net (code "328") (name "unconnected-(U11-N{slash}C-Pad4)") (class "Default")
      (node (ref "U11") (pin "4") (pinfunction "N/C_4") (pintype "unspecified"))
    )
    (net (code "329") (name "unconnected-(U13-CLK2-Pad6)") (class "Default")
      (node (ref "U13") (pin "6") (pinfunction "CLK2_6") (pintype "unspecified"))
    )
    (net (code "330") (name "unconnected-(U13-VDDO-Pad7)") (class "Default")
      (node (ref "U13") (pin "7") (pinfunction "VDDO_7") (pintype "unspecified"))
    )
    (net (code "331") (name "unconnected-(U22-PA8-Pad29)") (class "Default")
      (node (ref "U22") (pin "29") (pinfunction "PA8_29") (pintype "unspecified"))
    )
    (net (code "332") (name "unconnected-(U22-PB14-Pad27)") (class "Default")
      (node (ref "U22") (pin "27") (pinfunction "PB14_27") (pintype "unspecified"))
    )
    (net (code "333") (name "unconnected-(U22-PB15-Pad28)") (class "Default")
      (node (ref "U22") (pin "28") (pinfunction "PB15_28") (pintype "unspecified"))
    )
    (net (code "334") (name "unconnected-(U22-PF6-Pad35)") (class "Default")
      (node (ref "U22") (pin "35") (pinfunction "PF6_35") (pintype "unspecified"))
    )
    (net (code "335") (name "unconnected-(U22-PF7-Pad36)") (class "Default")
      (node (ref "U22") (pin "36") (pinfunction "PF7_36") (pintype "unspecified"))
    )
    (net (code "336") (name "unconnected-(USB1-Pad5)") (class "Default")
      (node (ref "USB1") (pin "5") (pinfunction "5_5") (pintype "unspecified"))
    )
    (net (code "337") (name "unconnected-(USB1-Pad6)") (class "Default")
      (node (ref "USB1") (pin "6") (pinfunction "6_6") (pintype "unspecified"))
    )
    (net (code "338") (name "unconnected-(USB1-VCC-Pad1)") (class "Default")
      (node (ref "USB1") (pin "1") (pinfunction "VCC_1") (pintype "input"))
    )
  )
)
